# PX4FMUv2_4_6.net
KiCad netlist of a schematic drawn in EAGLE
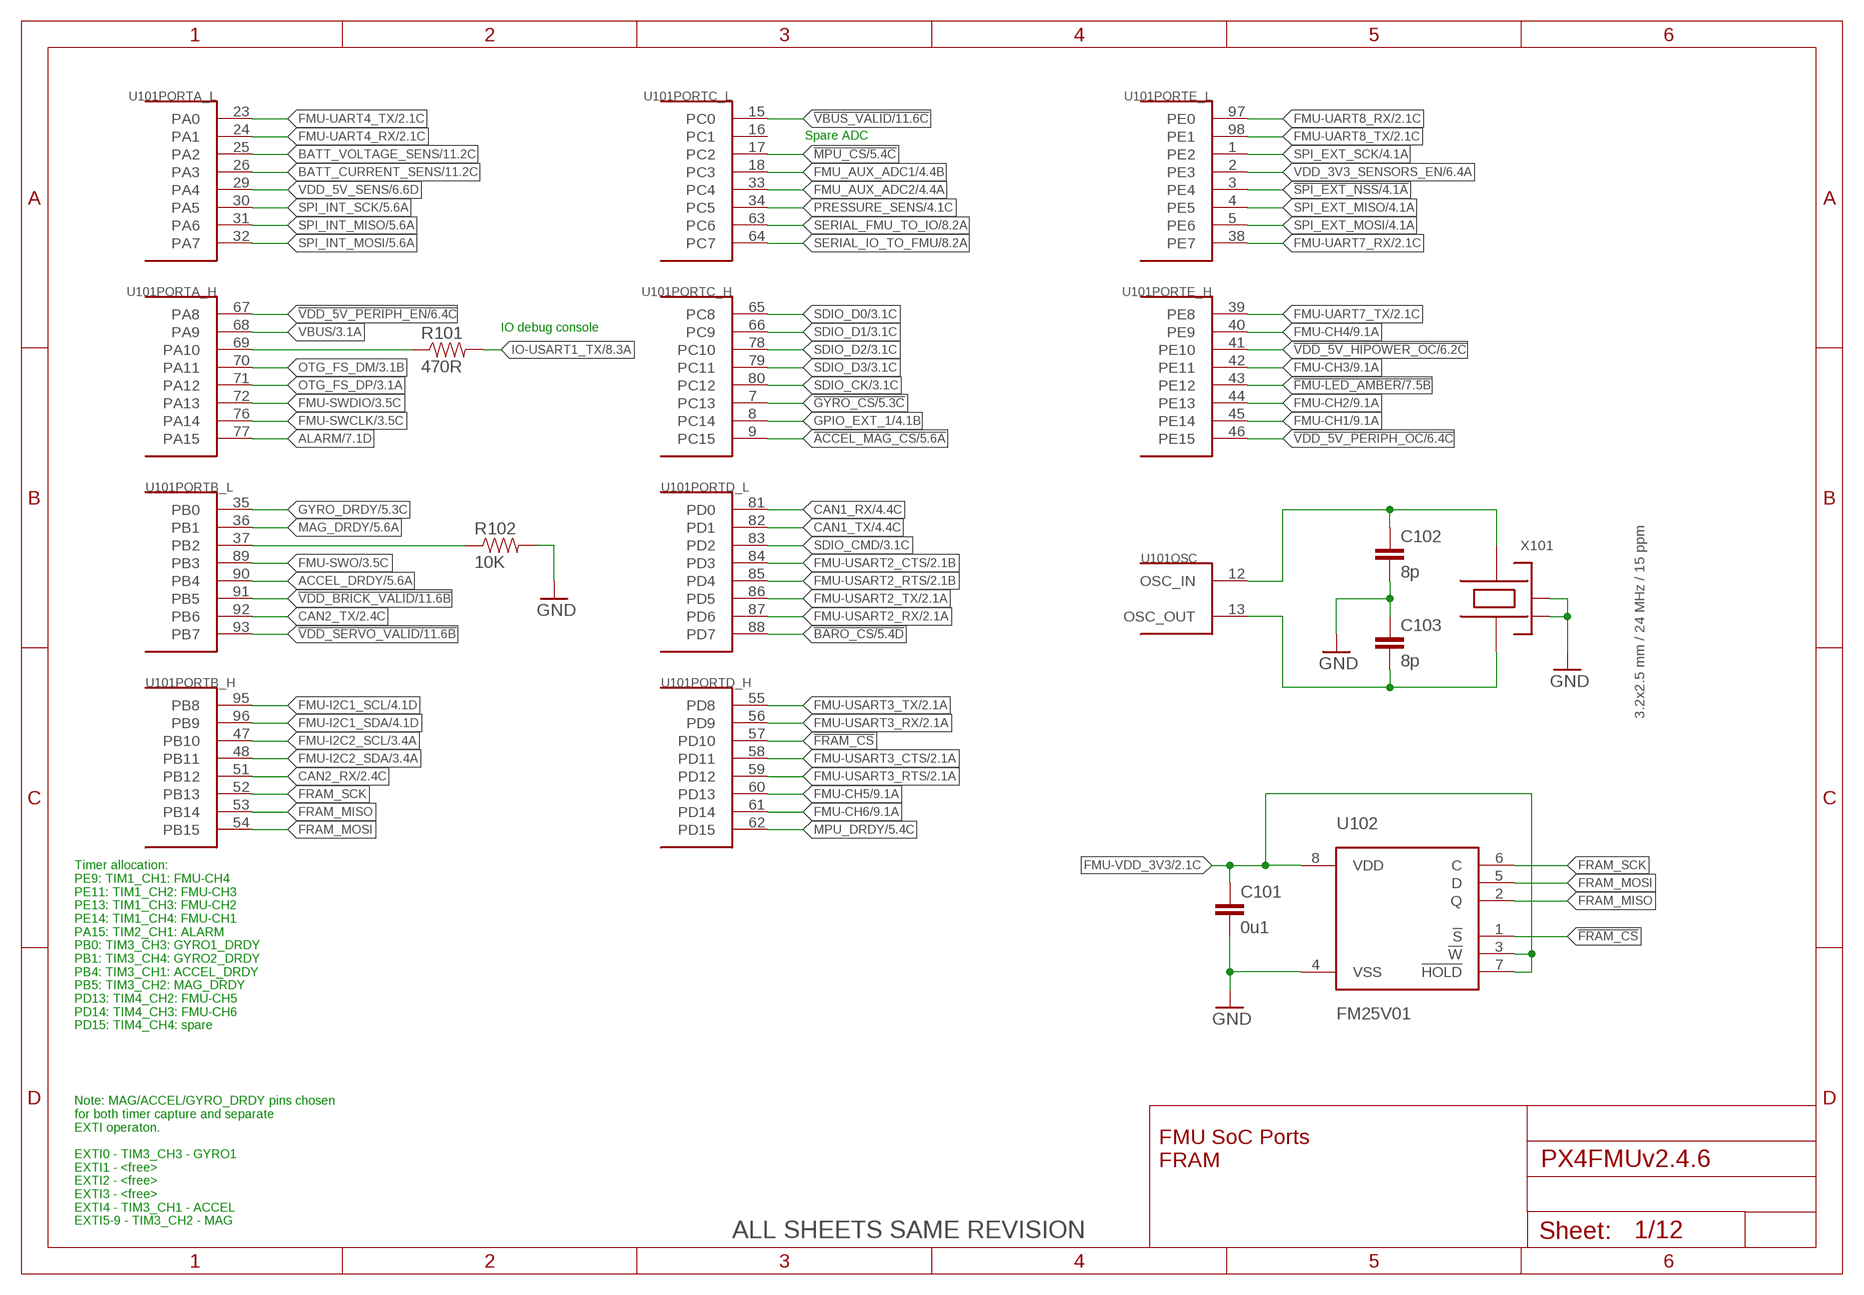
[diagram p0: schematic, sheet 1]
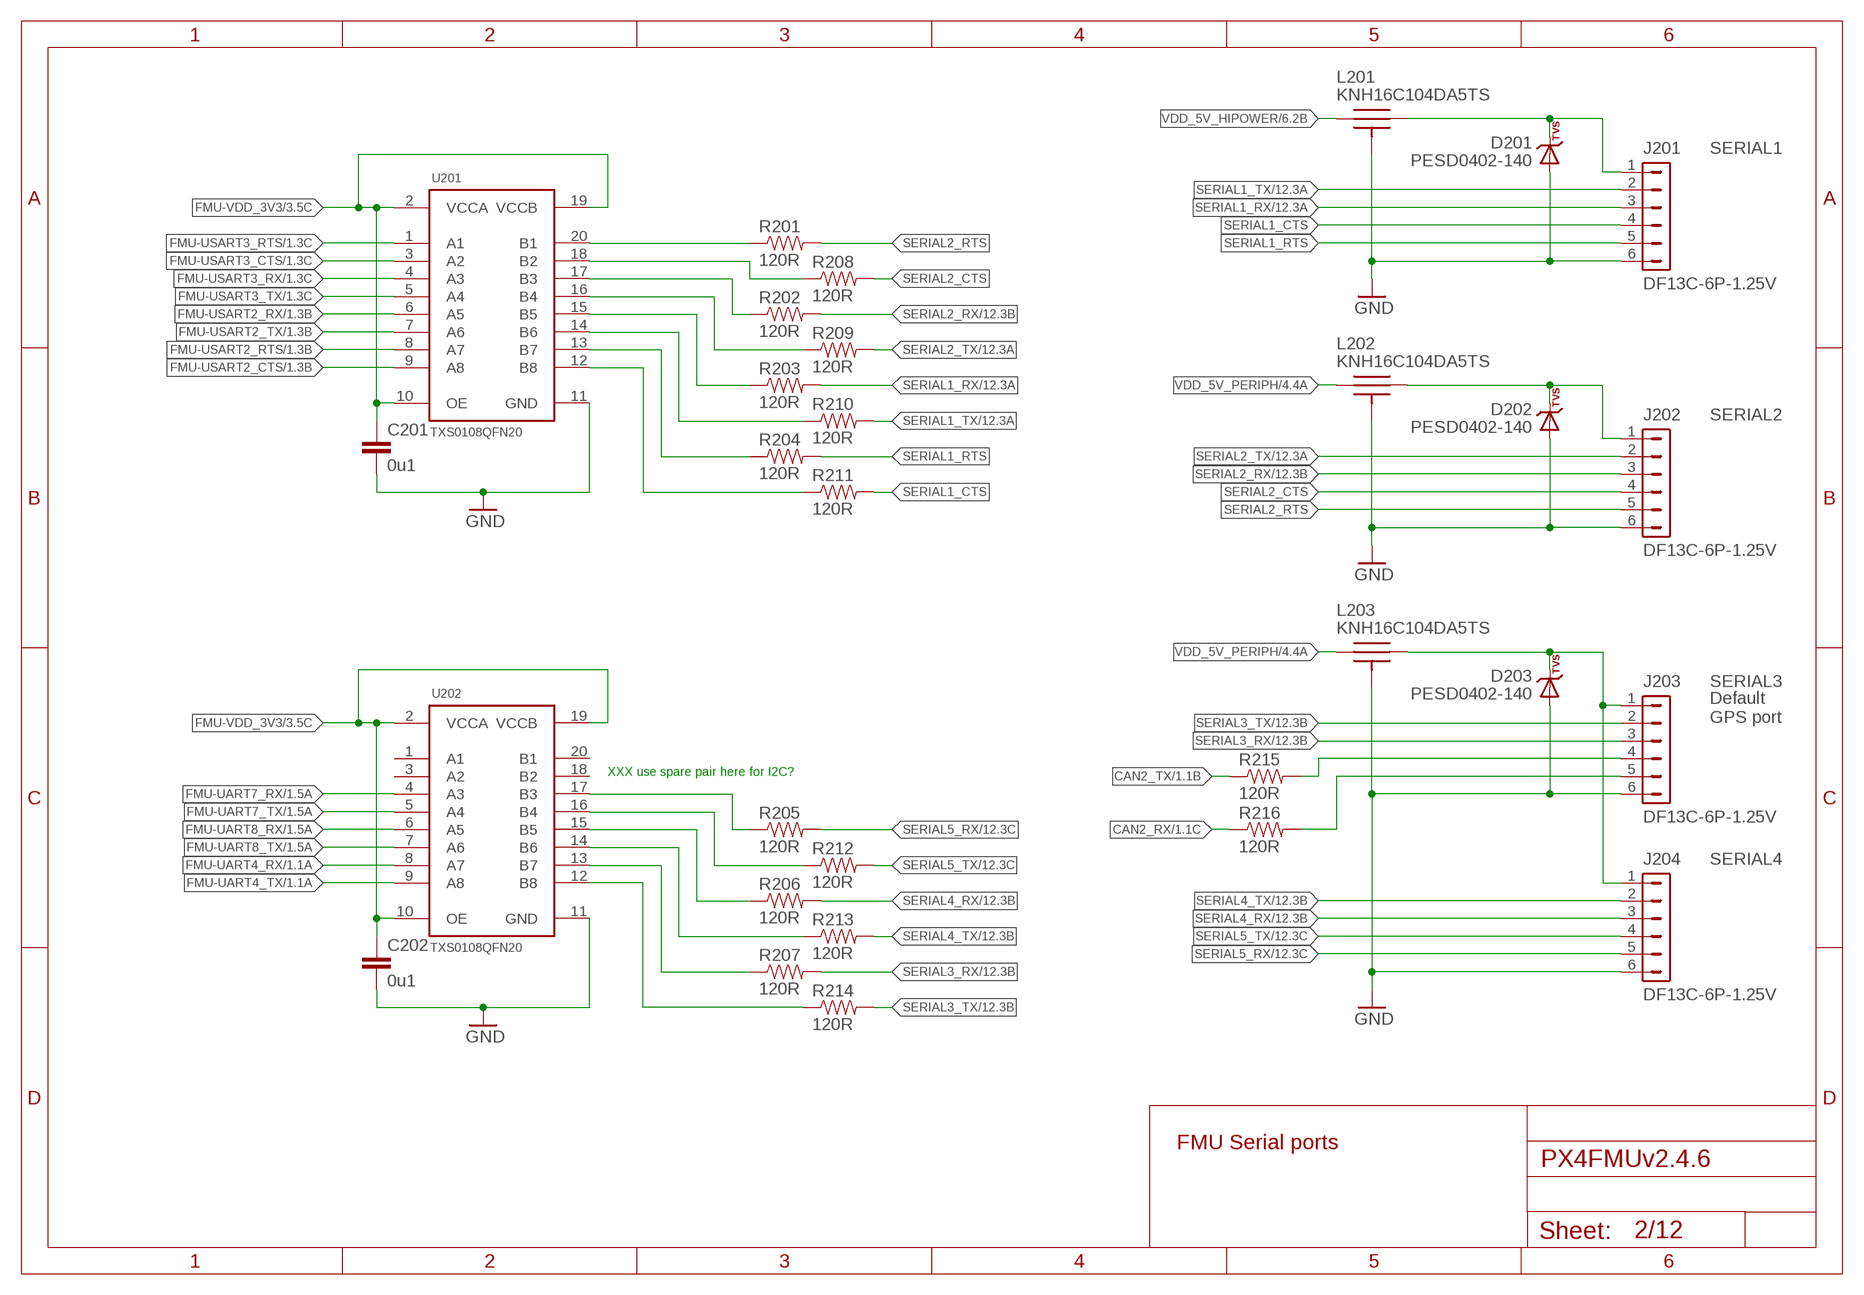
[diagram p1: schematic, sheet 2]
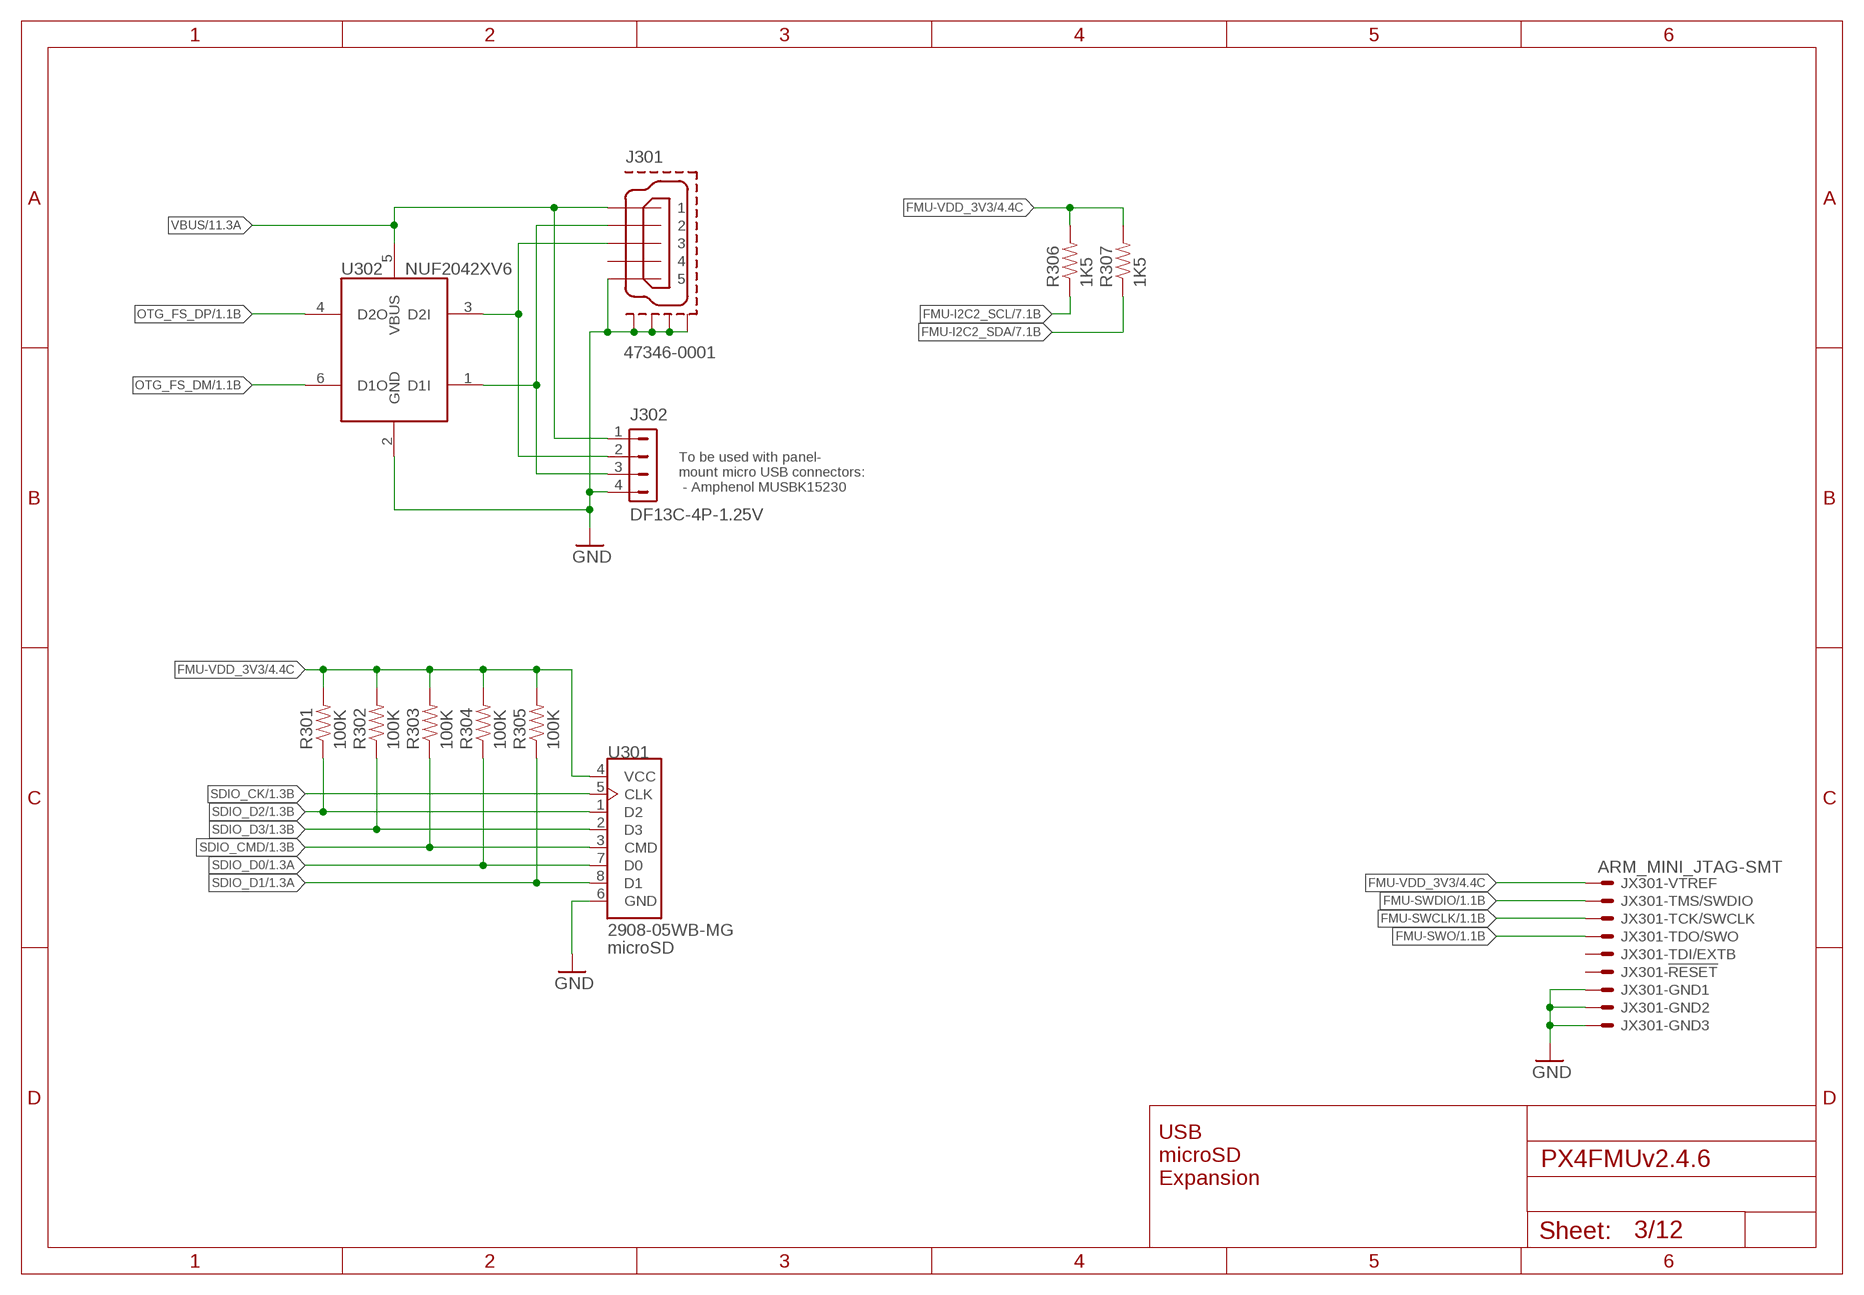
[diagram p2: schematic, sheet 3]
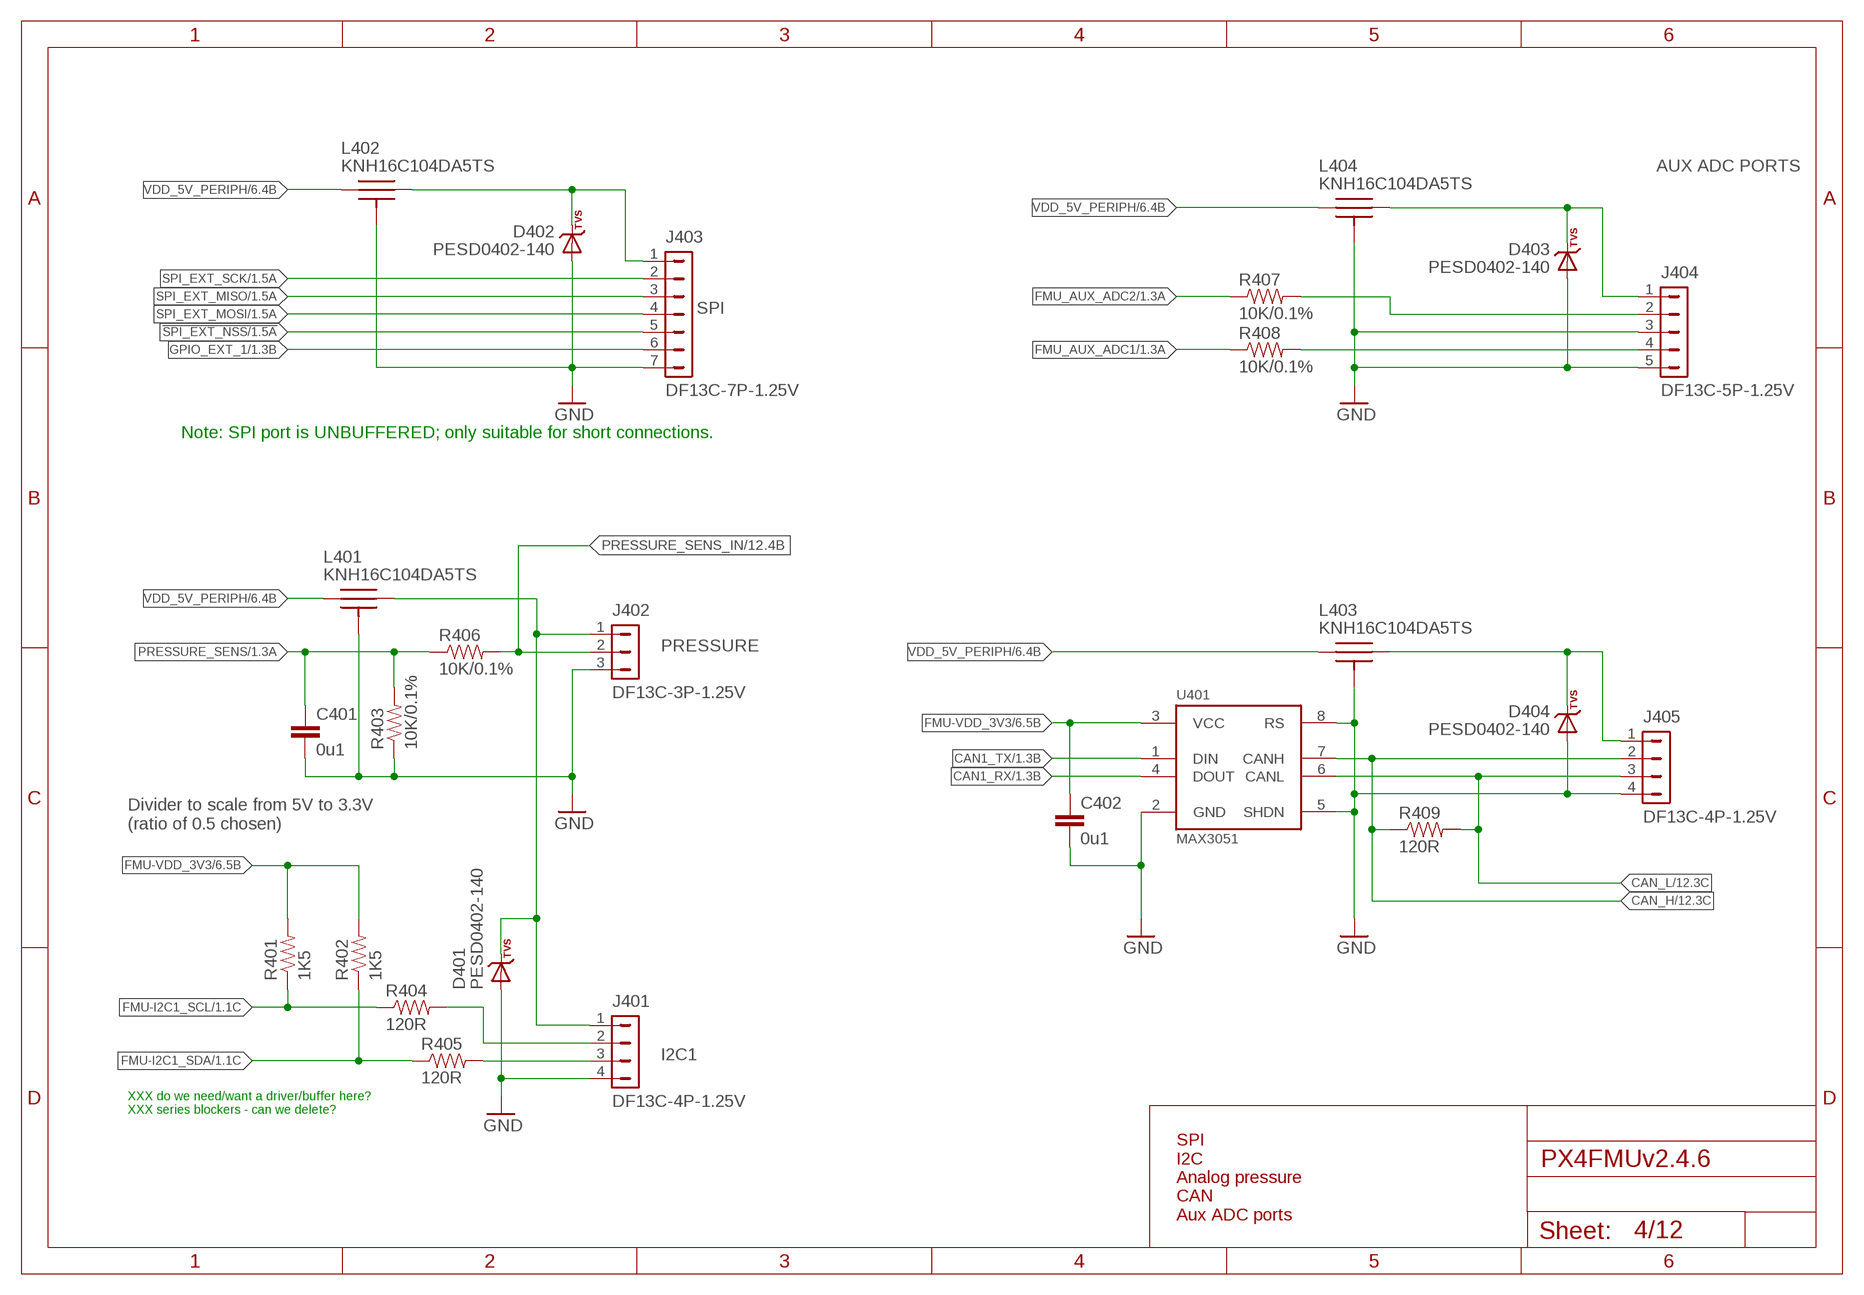
[diagram p3: schematic, sheet 4]
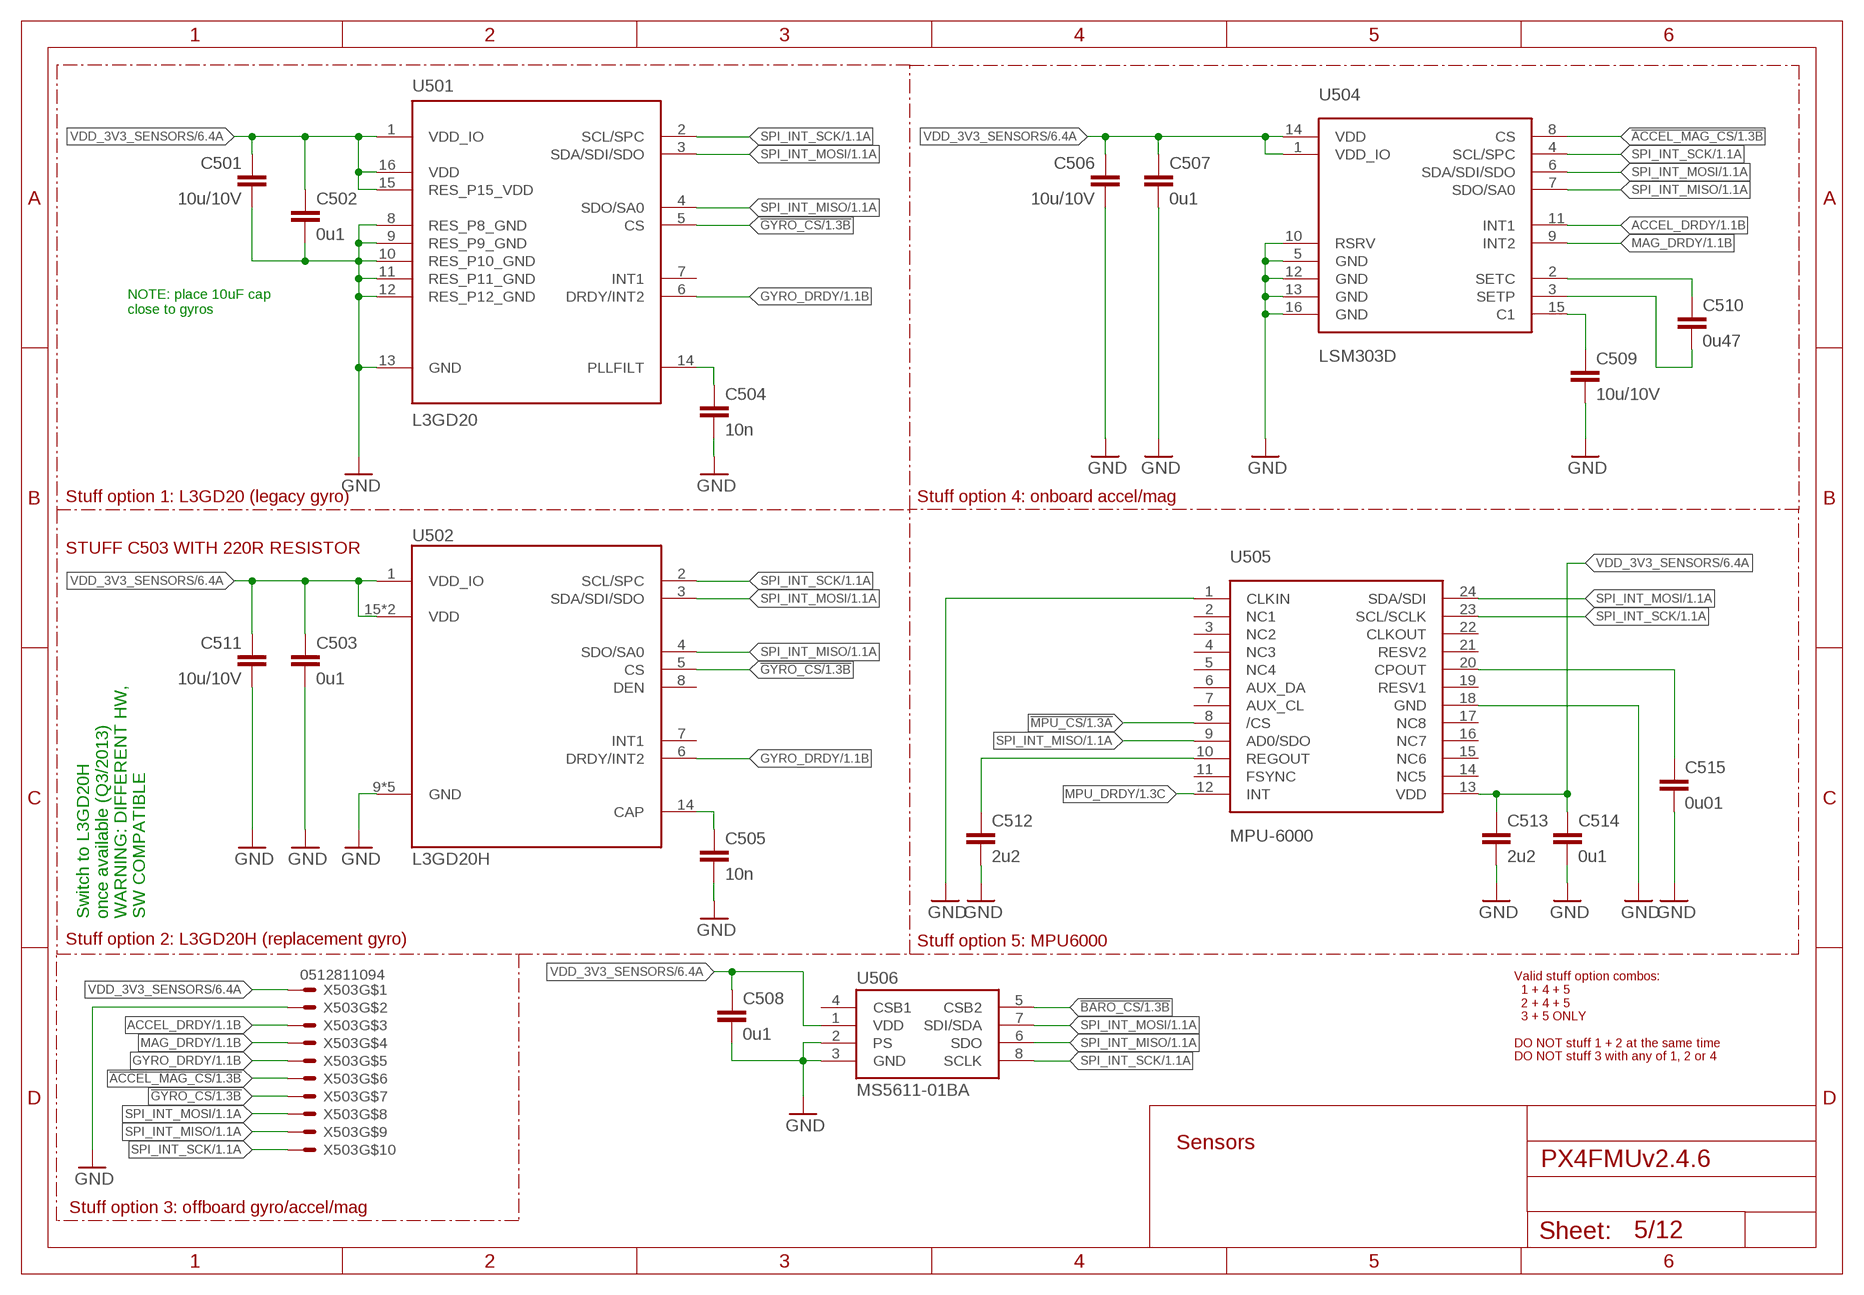
[diagram p4: schematic, sheet 5]
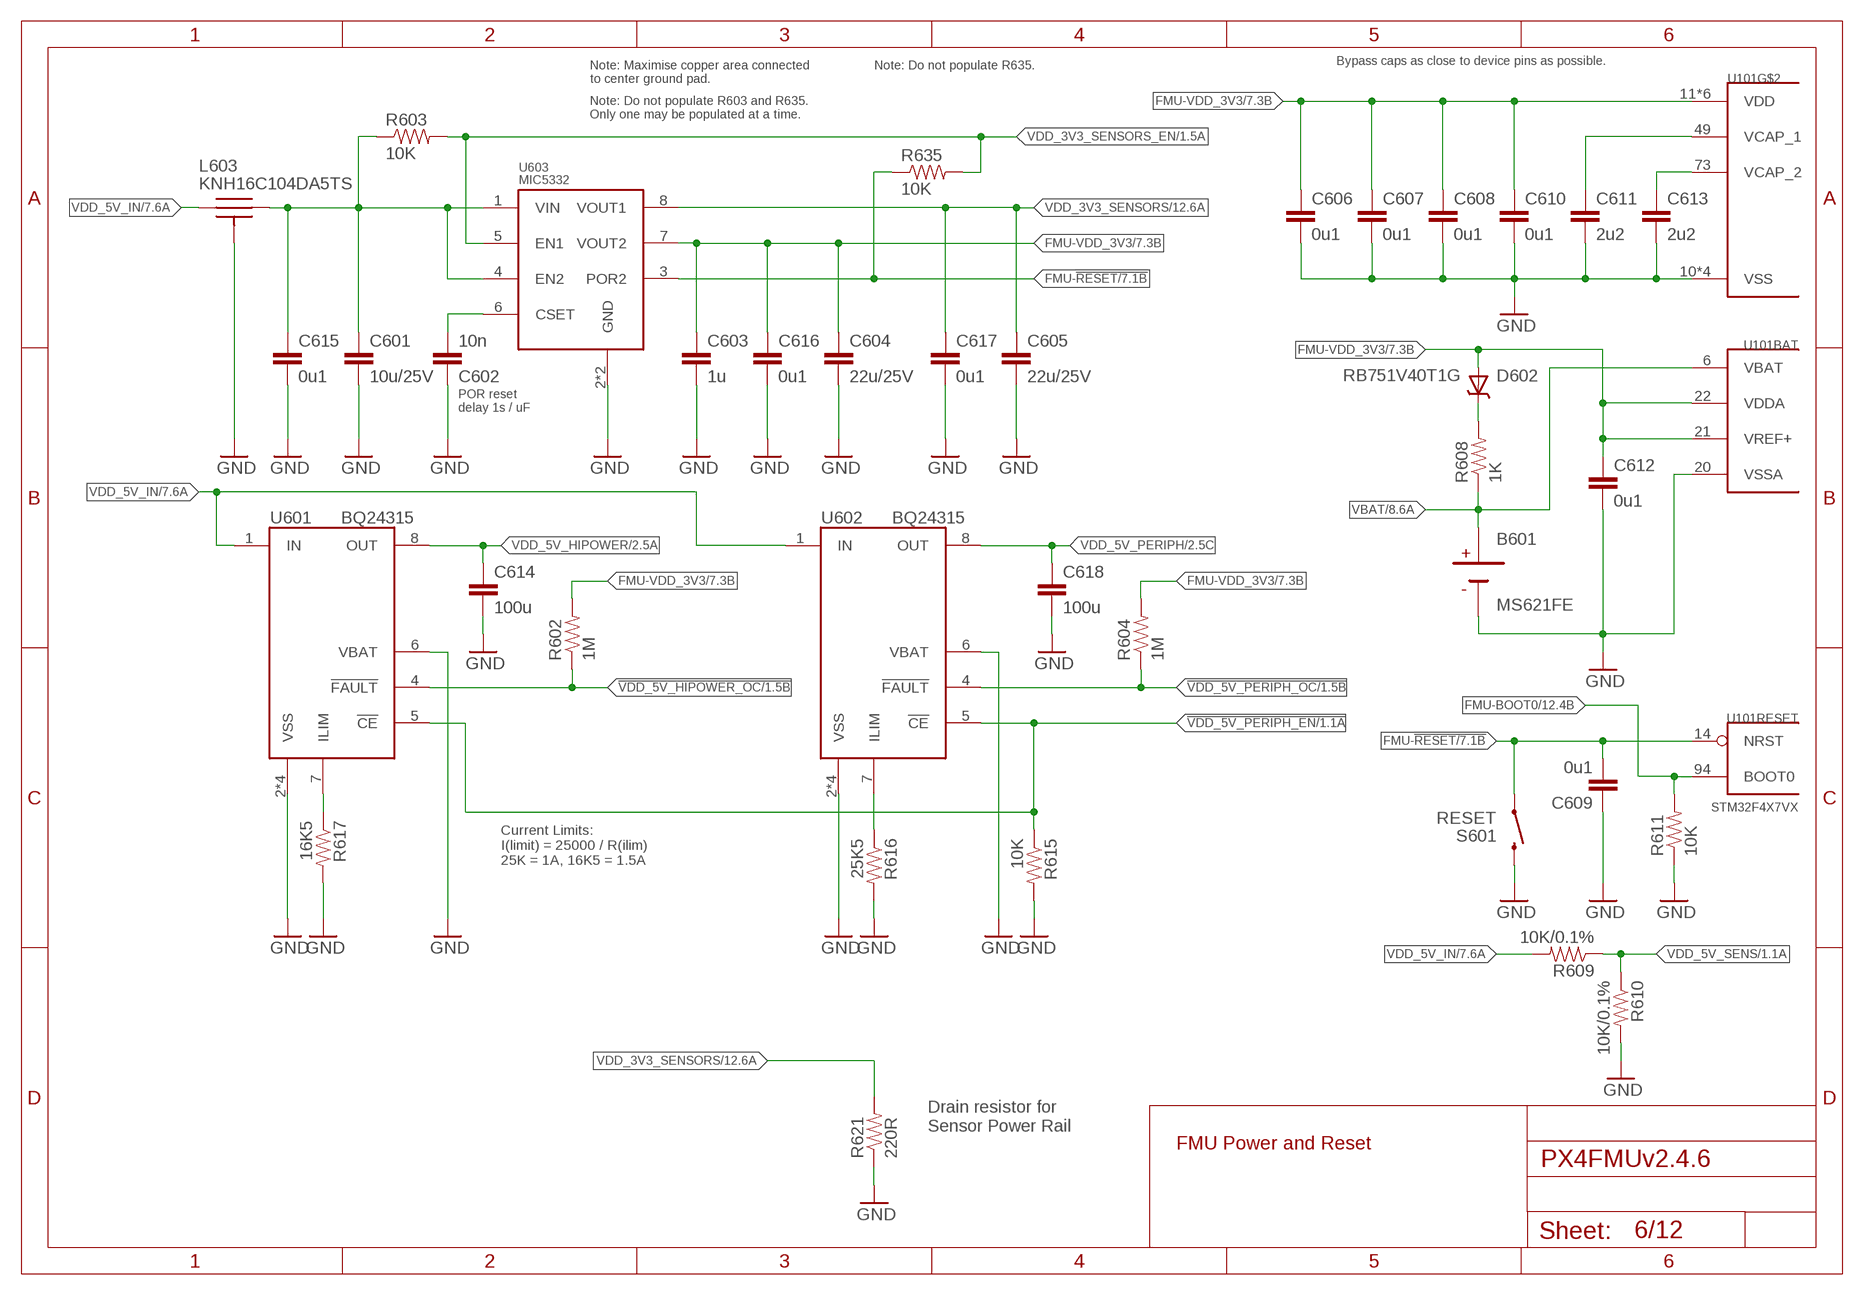
[diagram p5: schematic, sheet 6]
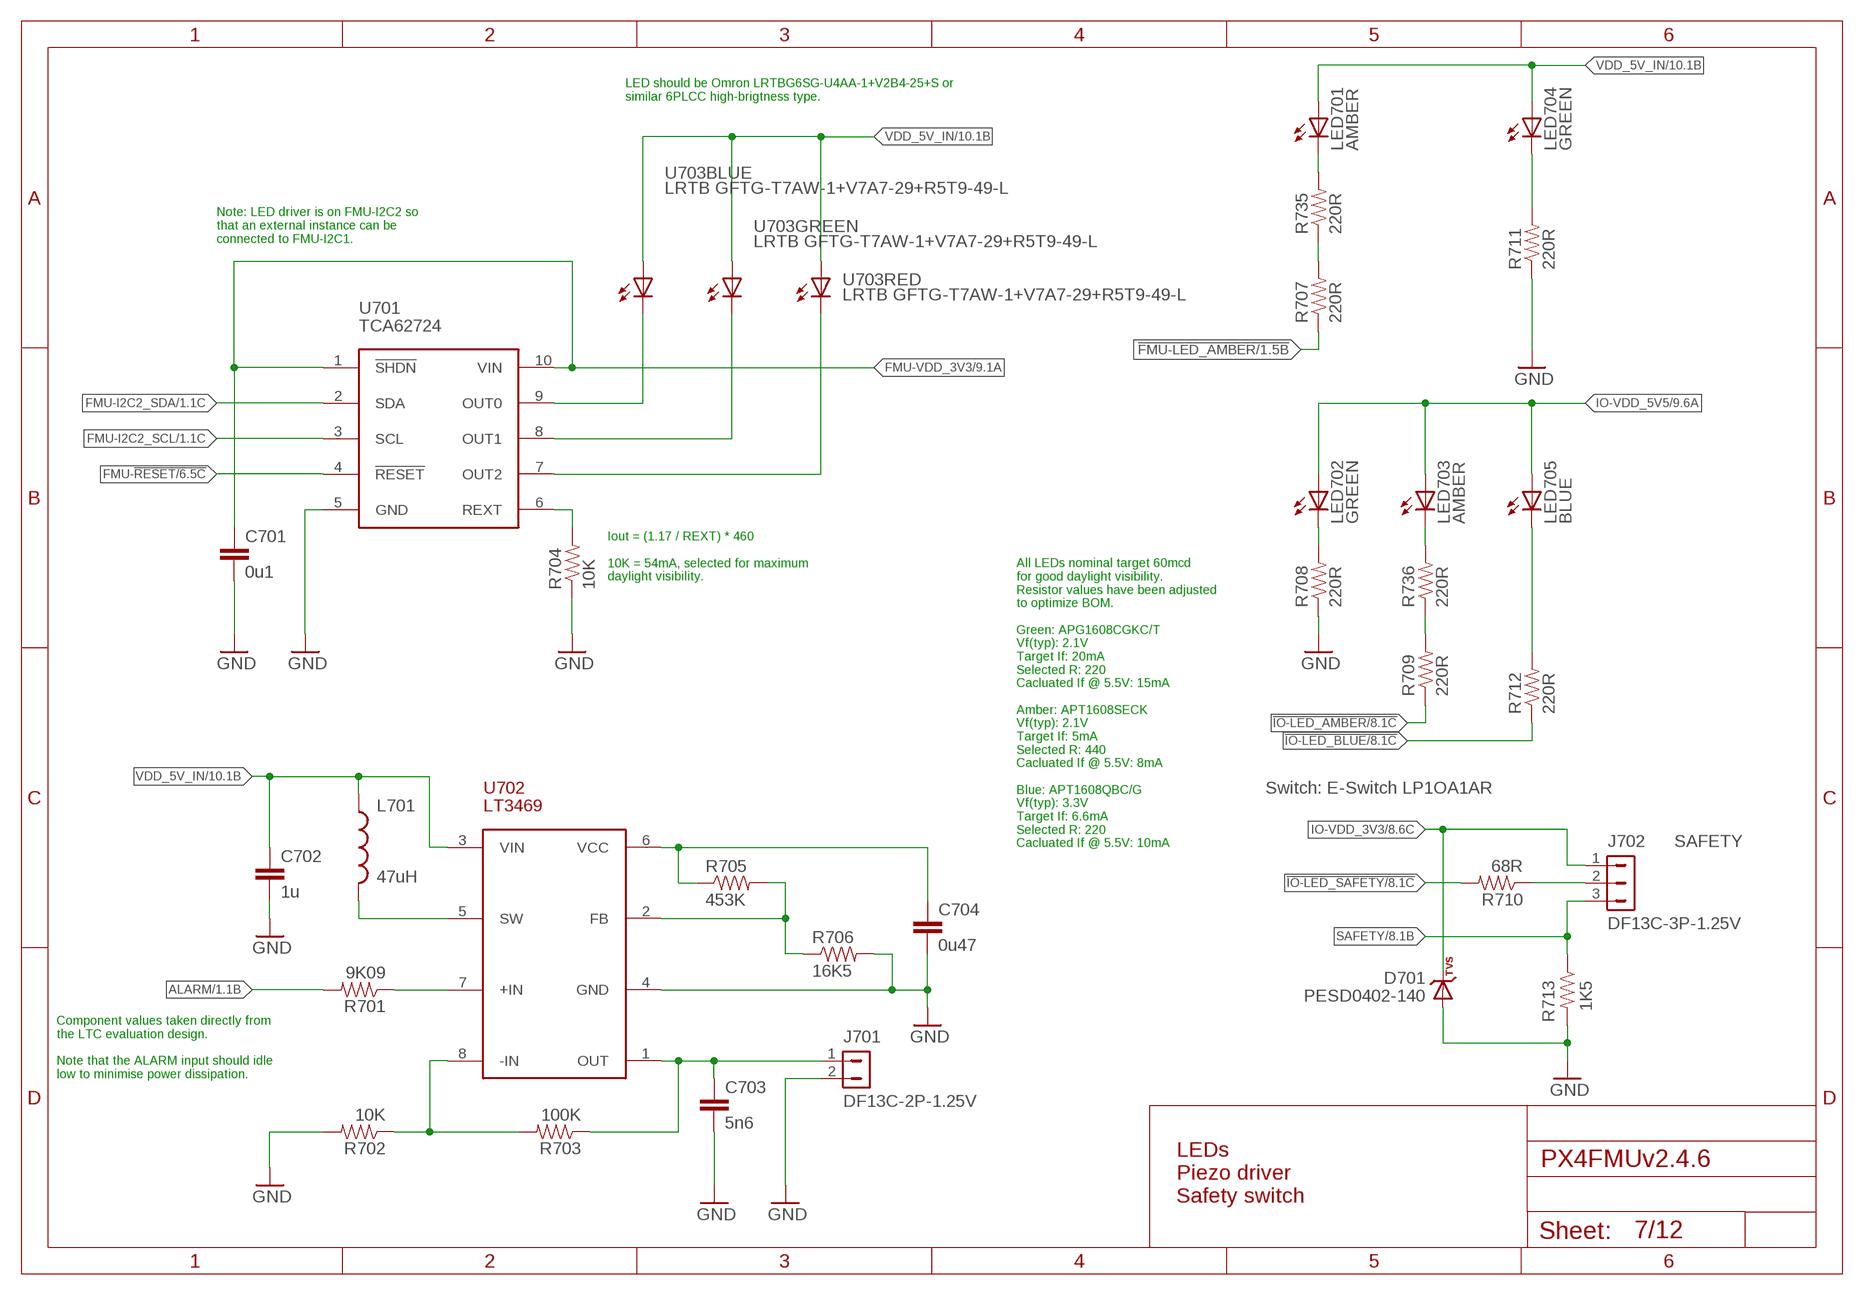
[diagram p6: schematic, sheet 7]
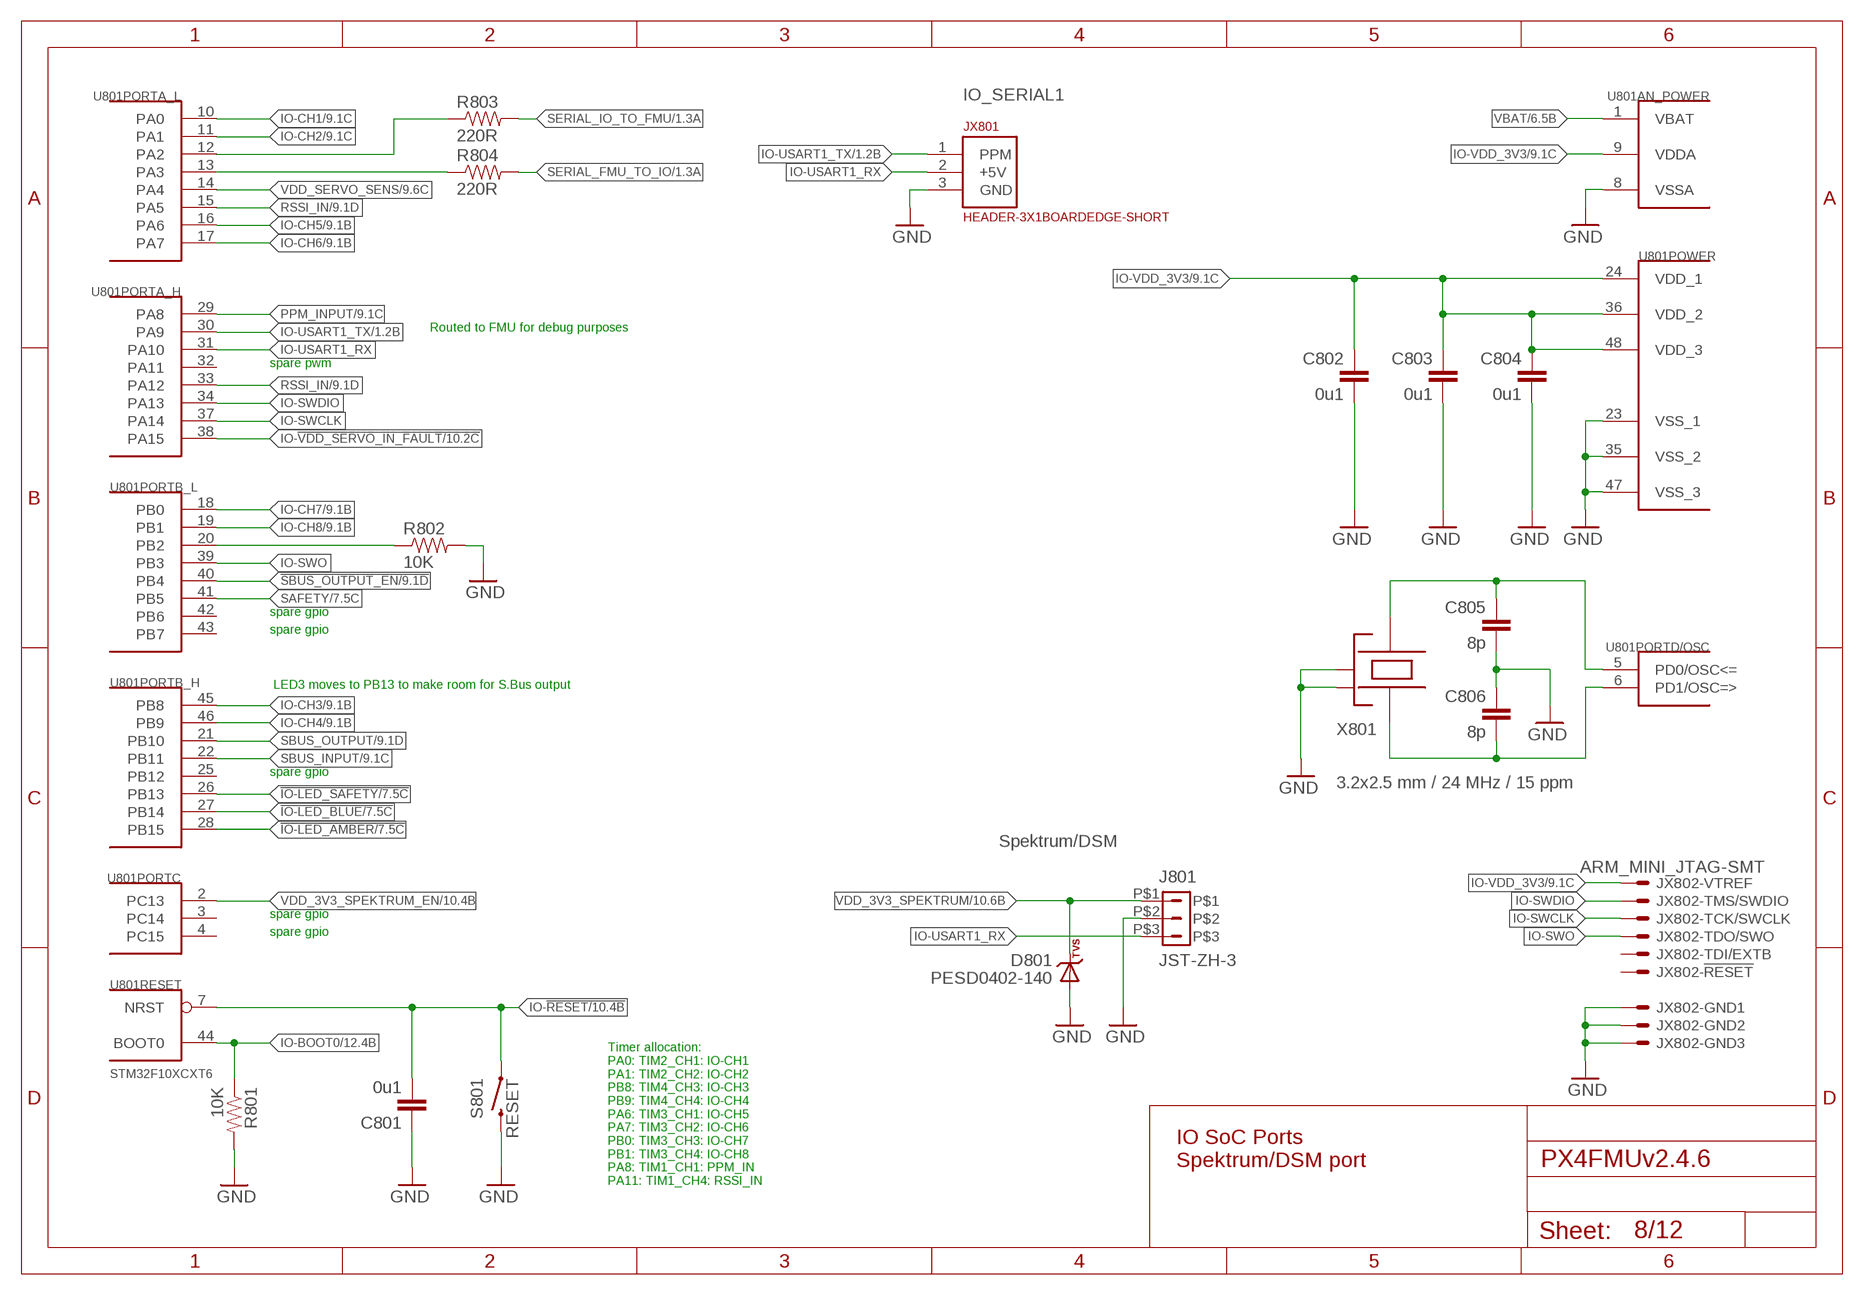
[diagram p7: schematic, sheet 8]
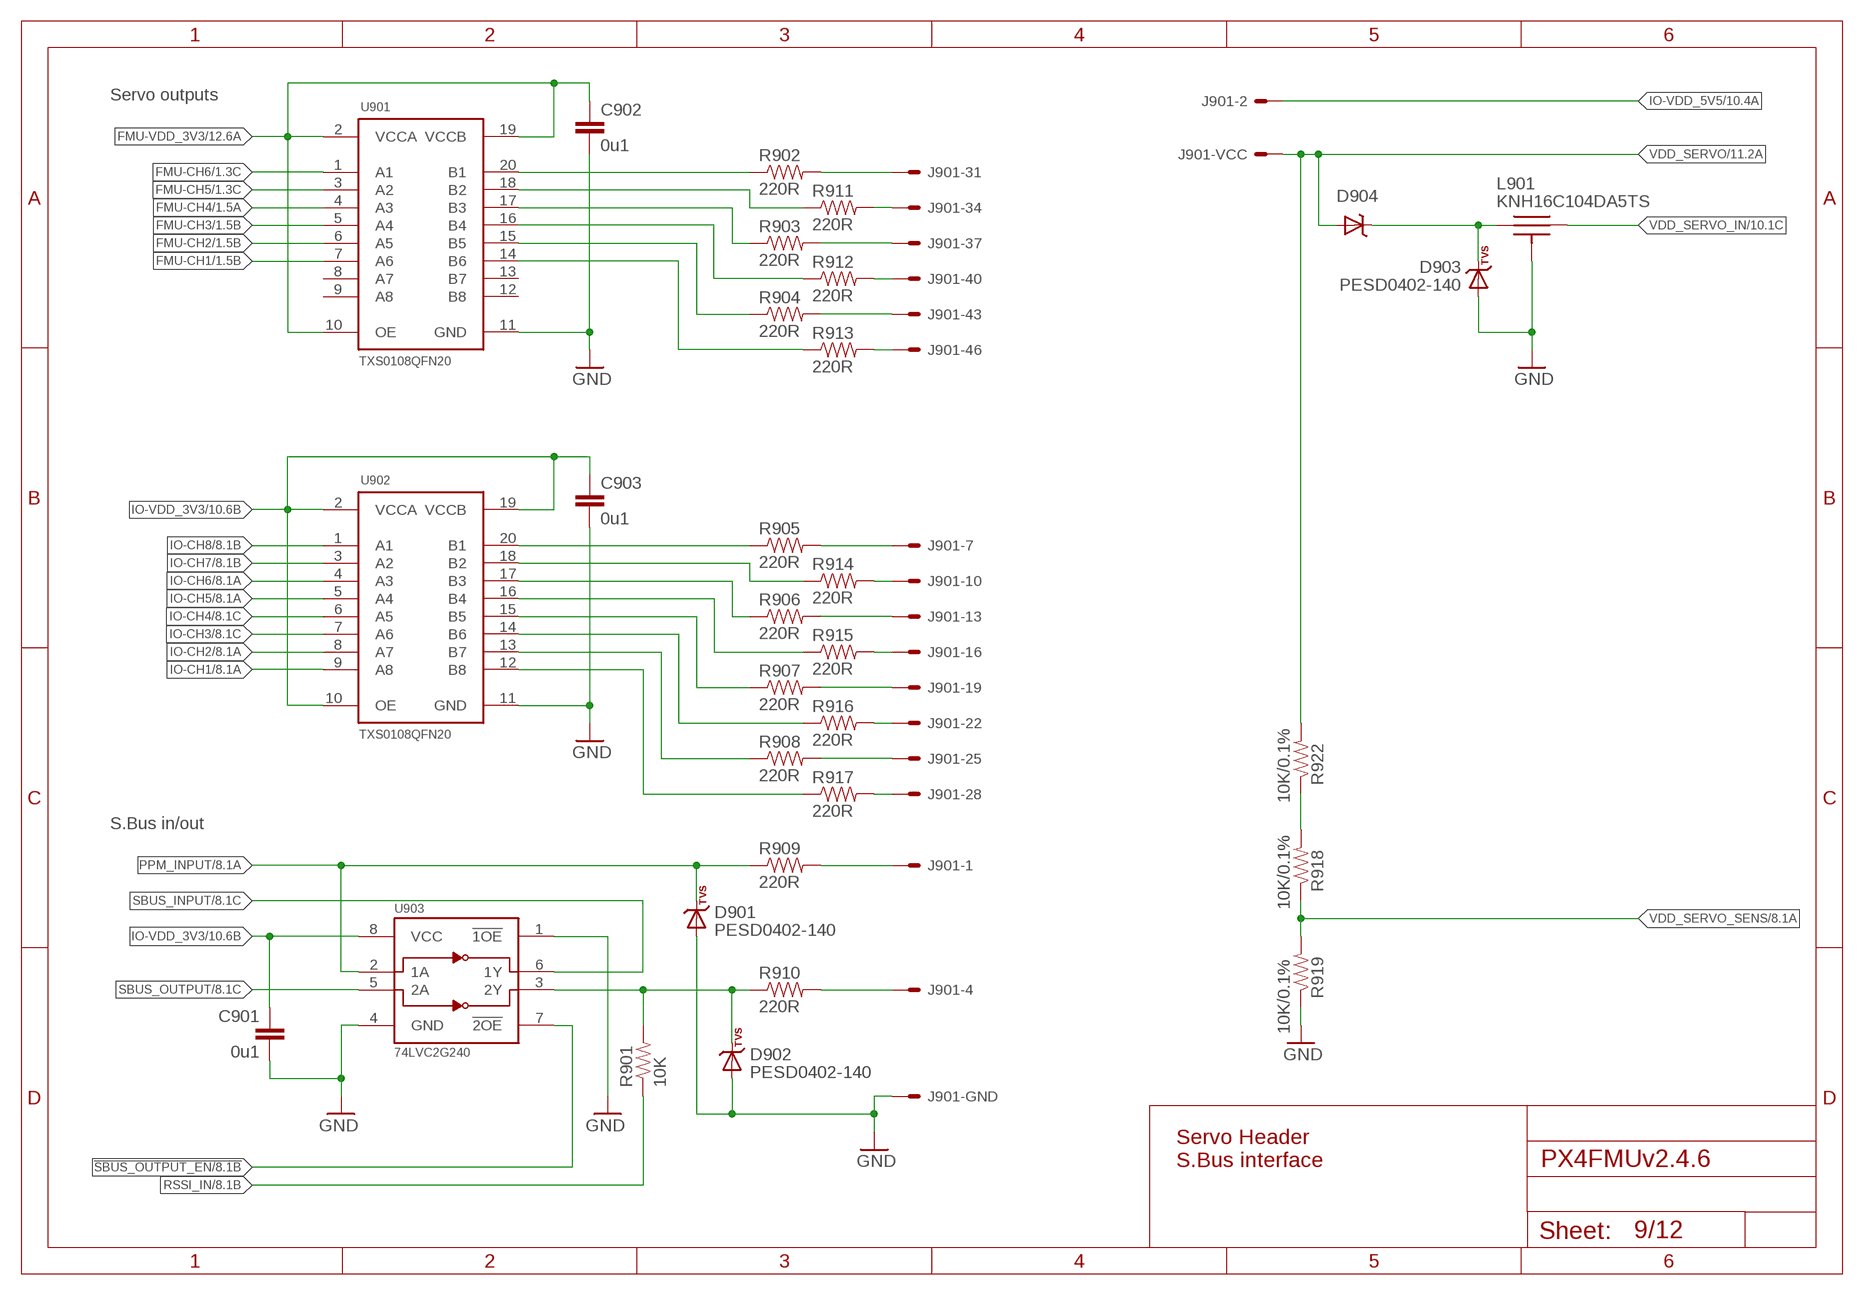
[diagram p8: schematic, sheet 9]
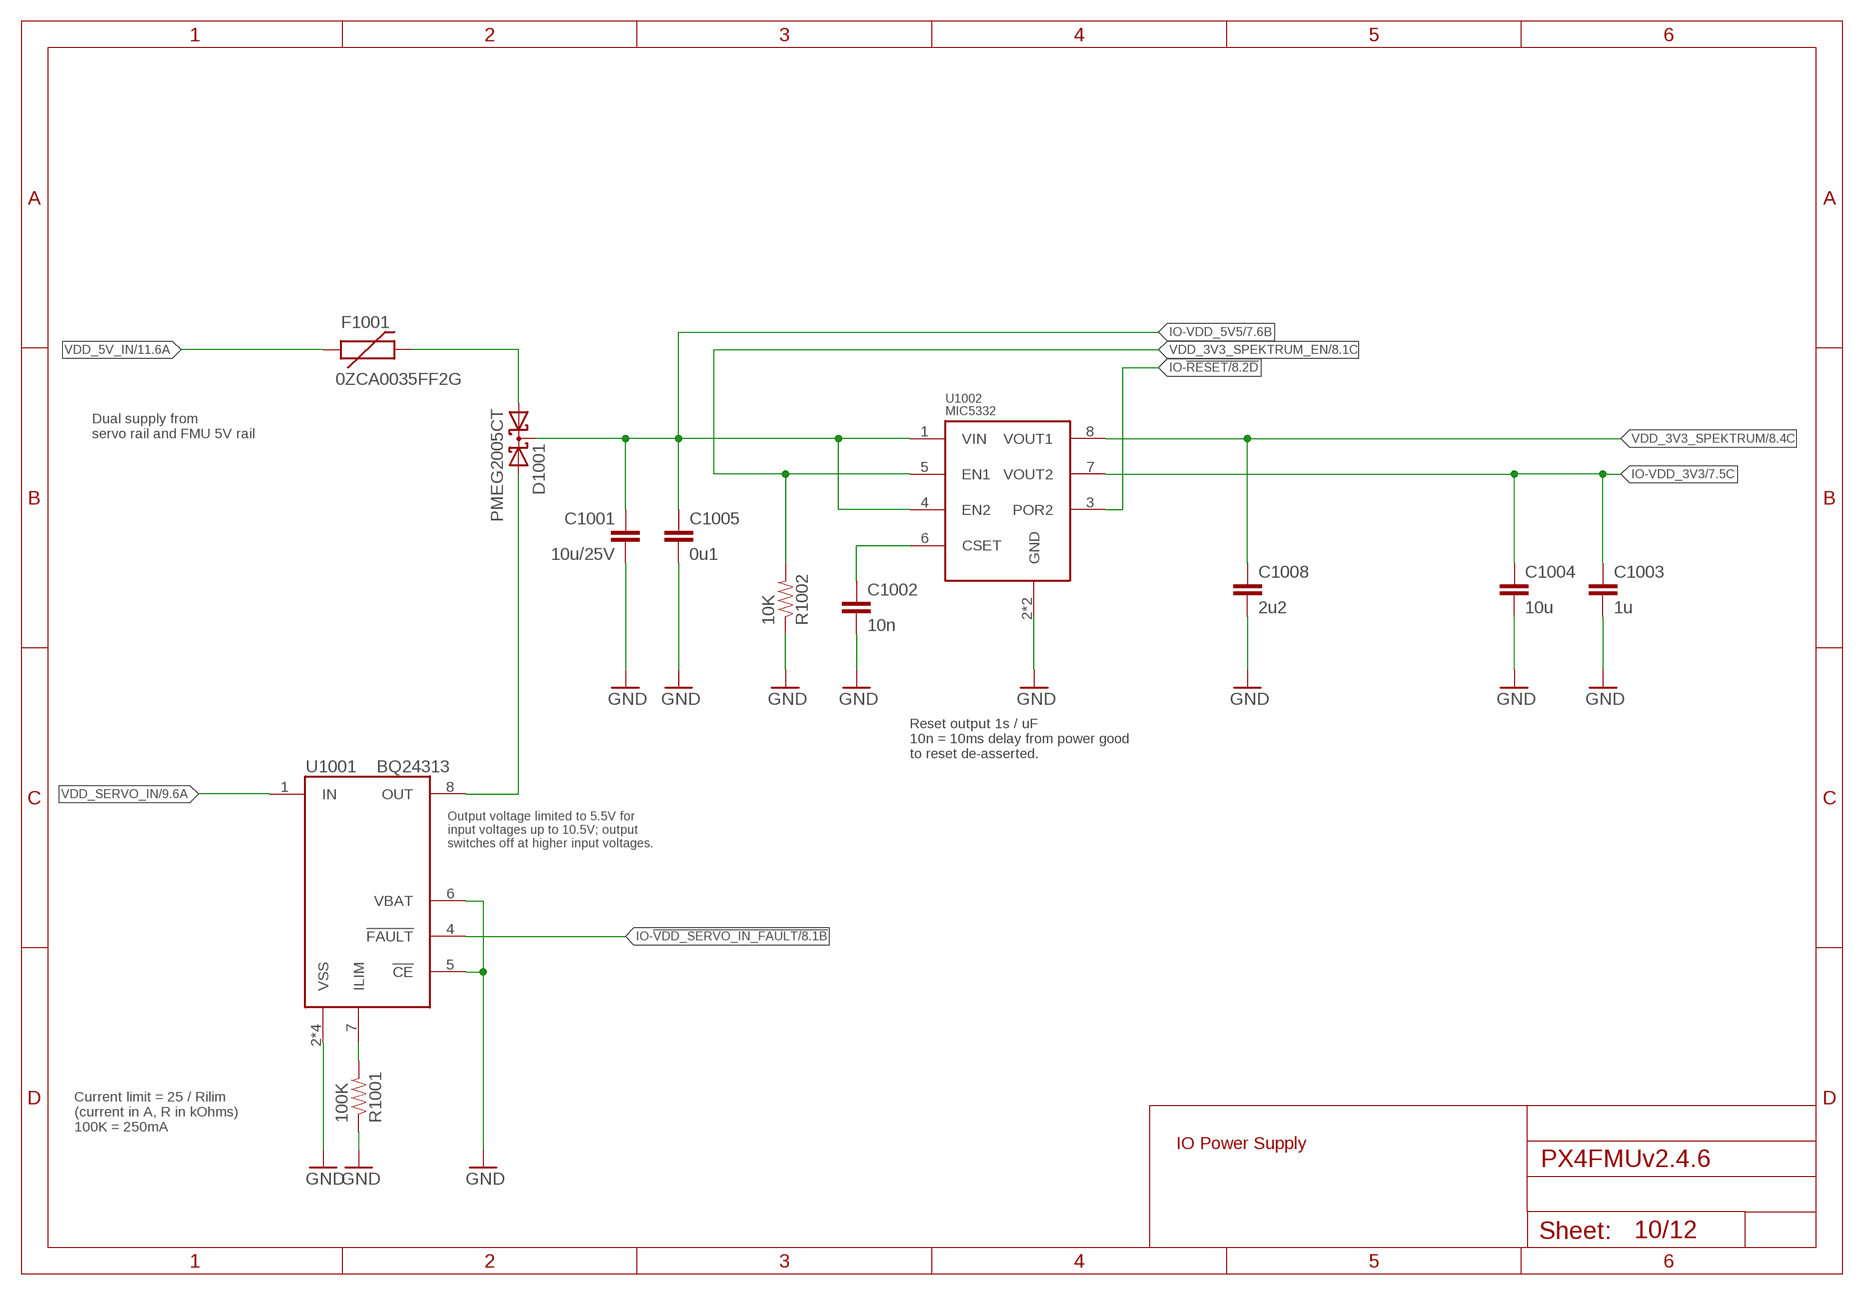
[diagram p9: schematic, sheet 10]
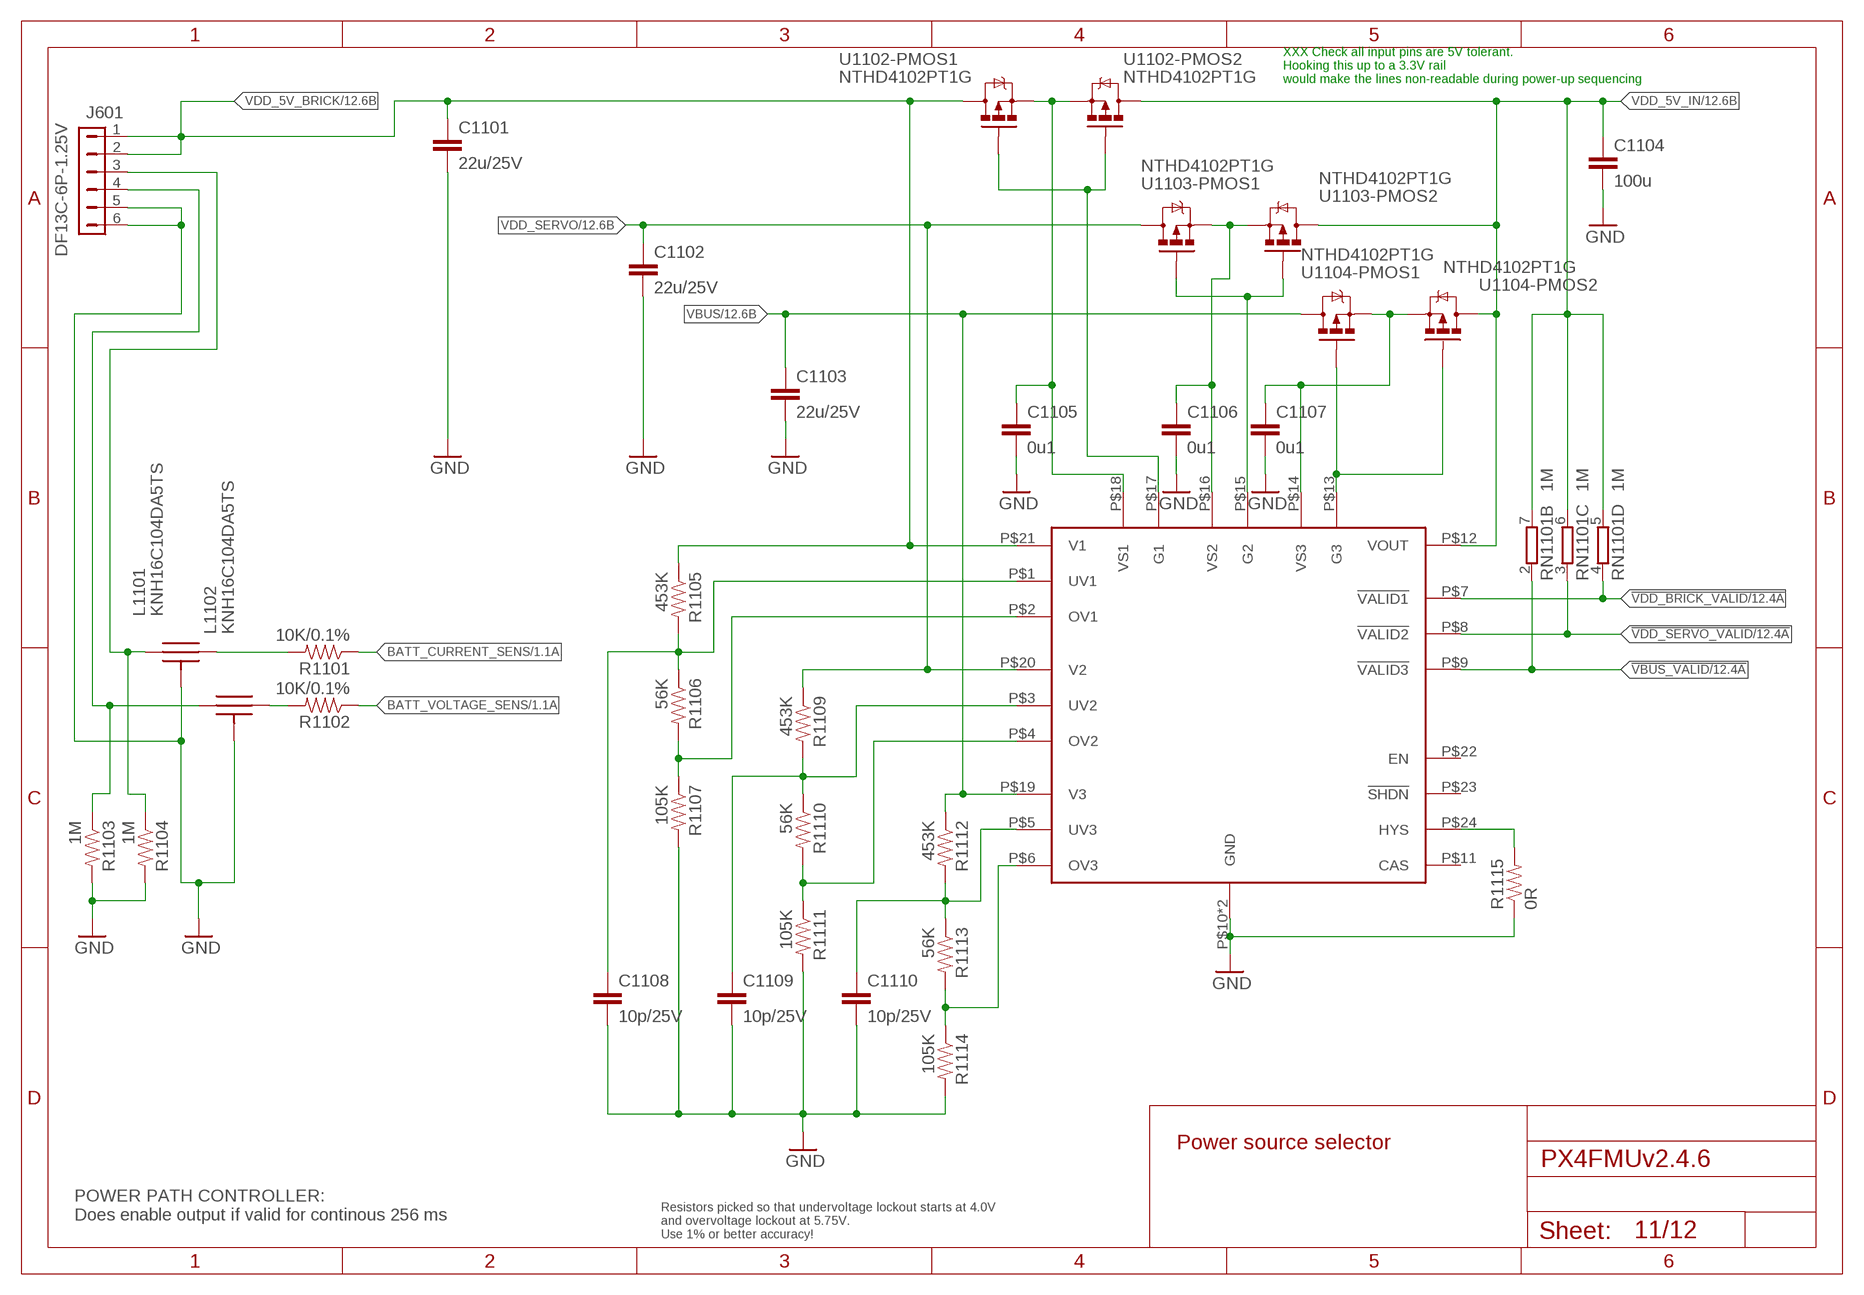
[diagram p10: schematic, sheet 11]
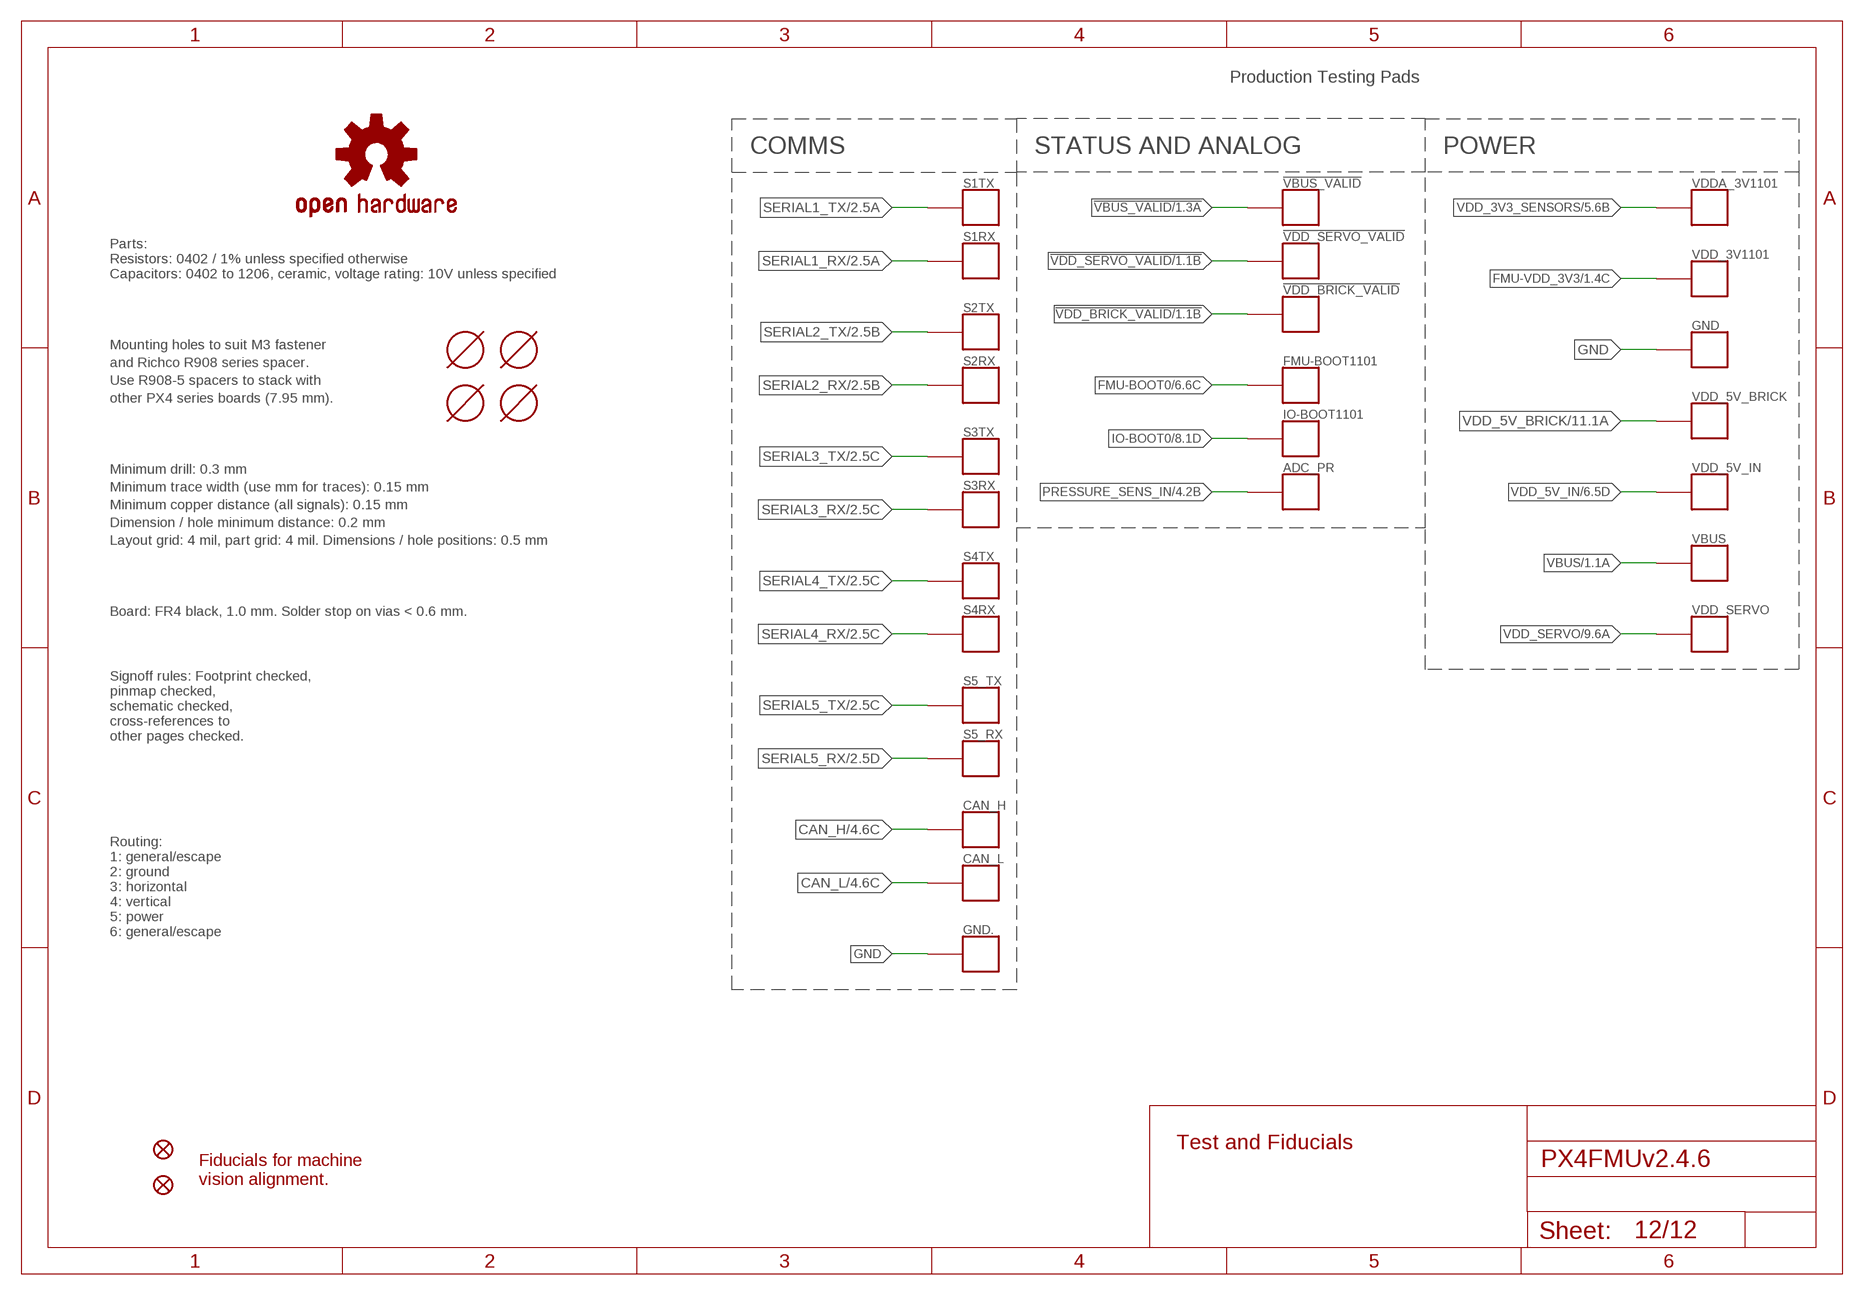
[diagram p11: schematic, sheet 12]

(export (version "E")
  (design (tool "Eeschema 10.0.6"))
  (components
    (comp (ref "C101")
      (value "0u1")
      (footprint "eagle-import:0402-CAP")
      (fields (field (name "PARTNO") "CC0402ZRY5V7BB104"))
      (libsource (lib "eagle-import") (part "CAP0402"))
    )
    (comp (ref "C102")
      (value "8p")
      (footprint "eagle-import:0402-CAP")
      (fields (field (name "PARTNO") "C1005C0G1H080C"))
      (libsource (lib "eagle-import") (part "CAP0402"))
    )
    (comp (ref "C103")
      (value "8p")
      (footprint "eagle-import:0402-CAP")
      (fields (field (name "PARTNO") "C1005C0G1H080C"))
      (libsource (lib "eagle-import") (part "CAP0402"))
    )
    (comp (ref "R101")
      (value "470R")
      (footprint "eagle-import:0402-RES")
      (fields (field (name "PARTNO") "RC0402FR-07470RL"))
      (libsource (lib "eagle-import") (part "RESISTOR0402-RES"))
    )
    (comp (ref "R102")
      (value "10K")
      (footprint "eagle-import:0402-RES")
      (fields (field (name "PARTNO") "RC0402FR-0710KL"))
      (libsource (lib "eagle-import") (part "RESISTOR0402-RES"))
    )
    (comp (ref "U101")
      (value "STM32F4X7VX")
      (footprint "eagle-import:TQFP100")
      (fields (field (name "PARTNO") "STM32F427VI"))
      (libsource (lib "eagle-import") (part "STM32F4X7VX"))
    )
    (comp (ref "U102")
      (value "FM25V01")
      (footprint "eagle-import:SO08")
      (fields (field (name "PARTNO") "FM25V01-G"))
      (libsource (lib "eagle-import") (part "FM25V01"))
    )
    (comp (ref "X101")
      (value "3.2x2.5 mm / 24 MHz / 15 ppm")
      (footprint "eagle-import:OSCILLATOR-3.2X2.5")
      (fields (field (name "PARTNO") "NX3225SA-24.000000MHZ"))
      (libsource (lib "eagle-import") (part "OSCILLATOR-3.2X2.5"))
    )
    (comp (ref "C901")
      (value "0u1")
      (footprint "eagle-import:0402-CAP")
      (fields (field (name "PARTNO") "CC0402ZRY5V7BB104"))
      (libsource (lib "eagle-import") (part "CAP0402"))
    )
    (comp (ref "C902")
      (value "0u1")
      (footprint "eagle-import:0402-CAP")
      (fields (field (name "PARTNO") "CC0402ZRY5V7BB104"))
      (libsource (lib "eagle-import") (part "CAP0402"))
    )
    (comp (ref "C903")
      (value "0u1")
      (footprint "eagle-import:0402-CAP")
      (fields (field (name "PARTNO") "CC0402ZRY5V7BB104"))
      (libsource (lib "eagle-import") (part "CAP0402"))
    )
    (comp (ref "D901")
      (value "PESD0402-140")
      (footprint "eagle-import:0402-TVS")
      (libsource (lib "eagle-import") (part "DIODE-TVS"))
    )
    (comp (ref "D902")
      (value "PESD0402-140")
      (footprint "eagle-import:0402-TVS")
      (libsource (lib "eagle-import") (part "DIODE-TVS"))
    )
    (comp (ref "D903")
      (value "PESD0402-140")
      (footprint "eagle-import:0402-TVS")
      (libsource (lib "eagle-import") (part "DIODE-TVS"))
    )
    (comp (ref "D904")
      (value "MSS1P4-M3")
      (footprint "eagle-import:MICROSMP")
      (fields (field (name "PARTNO") "MSS1P4-M3/89A"))
      (libsource (lib "eagle-import") (part "DIODE-SCHOTTKY_MSMP"))
    )
    (comp (ref "J901")
      (value "HEADER-3X163X16RA")
      (footprint "eagle-import:3X16RA")
      (fields (field (name "BOM") "EXCLUDE"))
      (libsource (lib "eagle-import") (part "HEADER-3X163X16RA"))
    )
    (comp (ref "L901")
      (value "KNH16C104DA5TS")
      (footprint "eagle-import:KYOCERA-KNH16-DA")
      (libsource (lib "eagle-import") (part "KNH16C104DA5TS"))
    )
    (comp (ref "R901")
      (value "10K")
      (footprint "eagle-import:0402-RES")
      (fields (field (name "PARTNO") "RC0402FR-0710KL"))
      (libsource (lib "eagle-import") (part "RESISTOR0402-RES"))
    )
    (comp (ref "R902")
      (value "220R")
      (footprint "eagle-import:0402-RES")
      (fields (field (name "PARTNO") "RC0402FR-07220RL"))
      (libsource (lib "eagle-import") (part "RESISTOR0402-RES"))
    )
    (comp (ref "R903")
      (value "220R")
      (footprint "eagle-import:0402-RES")
      (fields (field (name "PARTNO") "RC0402FR-07220RL"))
      (libsource (lib "eagle-import") (part "RESISTOR0402-RES"))
    )
    (comp (ref "R904")
      (value "220R")
      (footprint "eagle-import:0402-RES")
      (fields (field (name "PARTNO") "RC0402FR-07220RL"))
      (libsource (lib "eagle-import") (part "RESISTOR0402-RES"))
    )
    (comp (ref "R905")
      (value "220R")
      (footprint "eagle-import:0402-RES")
      (fields (field (name "PARTNO") "RC0402FR-07220RL"))
      (libsource (lib "eagle-import") (part "RESISTOR0402-RES"))
    )
    (comp (ref "R906")
      (value "220R")
      (footprint "eagle-import:0402-RES")
      (fields (field (name "PARTNO") "RC0402FR-07220RL"))
      (libsource (lib "eagle-import") (part "RESISTOR0402-RES"))
    )
    (comp (ref "R907")
      (value "220R")
      (footprint "eagle-import:0402-RES")
      (fields (field (name "PARTNO") "RC0402FR-07220RL"))
      (libsource (lib "eagle-import") (part "RESISTOR0402-RES"))
    )
    (comp (ref "R908")
      (value "220R")
      (footprint "eagle-import:0402-RES")
      (fields (field (name "PARTNO") "RC0402FR-07220RL"))
      (libsource (lib "eagle-import") (part "RESISTOR0402-RES"))
    )
    (comp (ref "R909")
      (value "220R")
      (footprint "eagle-import:0402-RES")
      (fields (field (name "PARTNO") "RC0402FR-07220RL"))
      (libsource (lib "eagle-import") (part "RESISTOR0402-RES"))
    )
    (comp (ref "R910")
      (value "220R")
      (footprint "eagle-import:0402-RES")
      (fields (field (name "PARTNO") "RC0402FR-07220RL"))
      (libsource (lib "eagle-import") (part "RESISTOR0402-RES"))
    )
    (comp (ref "R911")
      (value "220R")
      (footprint "eagle-import:0402-RES")
      (fields (field (name "PARTNO") "RC0402FR-07220RL"))
      (libsource (lib "eagle-import") (part "RESISTOR0402-RES"))
    )
    (comp (ref "R912")
      (value "220R")
      (footprint "eagle-import:0402-RES")
      (fields (field (name "PARTNO") "RC0402FR-07220RL"))
      (libsource (lib "eagle-import") (part "RESISTOR0402-RES"))
    )
    (comp (ref "R913")
      (value "220R")
      (footprint "eagle-import:0402-RES")
      (fields (field (name "PARTNO") "RC0402FR-07220RL"))
      (libsource (lib "eagle-import") (part "RESISTOR0402-RES"))
    )
    (comp (ref "R914")
      (value "220R")
      (footprint "eagle-import:0402-RES")
      (fields (field (name "PARTNO") "RC0402FR-07220RL"))
      (libsource (lib "eagle-import") (part "RESISTOR0402-RES"))
    )
    (comp (ref "R915")
      (value "220R")
      (footprint "eagle-import:0402-RES")
      (fields (field (name "PARTNO") "RC0402FR-07220RL"))
      (libsource (lib "eagle-import") (part "RESISTOR0402-RES"))
    )
    (comp (ref "R916")
      (value "220R")
      (footprint "eagle-import:0402-RES")
      (fields (field (name "PARTNO") "RC0402FR-07220RL"))
      (libsource (lib "eagle-import") (part "RESISTOR0402-RES"))
    )
    (comp (ref "R917")
      (value "220R")
      (footprint "eagle-import:0402-RES")
      (fields (field (name "PARTNO") "RC0402FR-07220RL"))
      (libsource (lib "eagle-import") (part "RESISTOR0402-RES"))
    )
    (comp (ref "R918")
      (value "10K/0.1%")
      (footprint "eagle-import:0402-RES")
      (fields (field (name "PARTNO") "ERA-2AEB103X"))
      (libsource (lib "eagle-import") (part "RESISTOR0402-RES"))
    )
    (comp (ref "R919")
      (value "10K/0.1%")
      (footprint "eagle-import:0402-RES")
      (fields (field (name "PARTNO") "ERA-2AEB103X"))
      (libsource (lib "eagle-import") (part "RESISTOR0402-RES"))
    )
    (comp (ref "R922")
      (value "10K/0.1%")
      (footprint "eagle-import:0402-RES")
      (fields (field (name "PARTNO") "ERA-2AEB103X"))
      (libsource (lib "eagle-import") (part "RESISTOR0402-RES"))
    )
    (comp (ref "U901")
      (value "TXS0108QFN20")
      (footprint "eagle-import:QFN20-RGY")
      (fields (field (name "PARTNO") "TXS0108ERGYR"))
      (libsource (lib "eagle-import") (part "TXS0108QFN20"))
    )
    (comp (ref "U902")
      (value "TXS0108QFN20")
      (footprint "eagle-import:QFN20-RGY")
      (fields (field (name "PARTNO") "TXS0108ERGYR"))
      (libsource (lib "eagle-import") (part "TXS0108QFN20"))
    )
    (comp (ref "U903")
      (value "74LVC2G240")
      (footprint "eagle-import:TSSOP8_SOT505-2")
      (fields (field (name "PARTNO") "74LVC2G240DP,125"))
      (libsource (lib "eagle-import") (part "74LVC2G240-TSSOP-8"))
    )
    (comp (ref "C1001")
      (value "10u/25V")
      (footprint "eagle-import:0805-CAP")
      (fields (field (name "PARTNO") "CL21A106KAYNNNE"))
      (libsource (lib "eagle-import") (part "CAP0805"))
    )
    (comp (ref "C1002")
      (value "10n")
      (footprint "eagle-import:0402-CAP")
      (fields (field (name "PARTNO") "CC0402KRX7R7BB103"))
      (libsource (lib "eagle-import") (part "CAP0402"))
    )
    (comp (ref "C1003")
      (value "1u")
      (footprint "eagle-import:0603-CAP")
      (fields (field (name "PARTNO") "CC0603ZRY5V7BB105"))
      (libsource (lib "eagle-import") (part "CAP0603"))
    )
    (comp (ref "C1004")
      (value "10u")
      (footprint "eagle-import:0603-CAP")
      (fields (field (name "PARTNO") "C1608X5R1A106K080AC"))
      (libsource (lib "eagle-import") (part "CAP0603"))
    )
    (comp (ref "C1005")
      (value "0u1")
      (footprint "eagle-import:0402-CAP")
      (fields (field (name "PARTNO") "CC0402ZRY5V7BB104"))
      (libsource (lib "eagle-import") (part "CAP0402"))
    )
    (comp (ref "C1008")
      (value "2u2")
      (footprint "eagle-import:0402-CAP")
      (fields (field (name "PARTNO") "C1005X6S1C225K050BC"))
      (libsource (lib "eagle-import") (part "CAP0402"))
    )
    (comp (ref "D1001")
      (value "PMEG2005CT")
      (footprint "eagle-import:SOT23-3")
      (libsource (lib "eagle-import") (part "PMEG2005CT"))
    )
    (comp (ref "F1001")
      (value "0ZCA0035FF2G")
      (footprint "eagle-import:PTC-1206")
      (libsource (lib "eagle-import") (part "PTCSMD"))
    )
    (comp (ref "R1001")
      (value "100K")
      (footprint "eagle-import:0402-RES")
      (fields (field (name "PARTNO") "RC0402FR-07100KL"))
      (libsource (lib "eagle-import") (part "RESISTOR0402-RES"))
    )
    (comp (ref "R1002")
      (value "10K")
      (footprint "eagle-import:0402-RES")
      (fields (field (name "PARTNO") "RC0402FR-0710KL"))
      (libsource (lib "eagle-import") (part "RESISTOR0402-RES"))
    )
    (comp (ref "U1001")
      (value "BQ24313")
      (footprint "eagle-import:QFN8-DSG")
      (fields (field (name "PARTNO") "BQ24313DSGT"))
      (libsource (lib "eagle-import") (part "BQ24313"))
    )
    (comp (ref "U1002")
      (value "MIC5332")
      (footprint "eagle-import:MLF-8-EPAD")
      (fields (field (name "PARTNO") "MIC5332-SSYMT"))
      (libsource (lib "eagle-import") (part "MIC5332"))
    )
    (comp (ref "C1101")
      (value "22u/25V")
      (footprint "eagle-import:0805-CAP")
      (fields (field (name "PARTNO") "CL21A226MAQNNNE"))
      (libsource (lib "eagle-import") (part "CAP0805"))
    )
    (comp (ref "C1102")
      (value "22u/25V")
      (footprint "eagle-import:0805-CAP")
      (fields (field (name "PARTNO") "CL21A226MAQNNNE"))
      (libsource (lib "eagle-import") (part "CAP0805"))
    )
    (comp (ref "C1103")
      (value "22u/25V")
      (footprint "eagle-import:0805-CAP")
      (fields (field (name "PARTNO") "CL21A226MAQNNNE"))
      (libsource (lib "eagle-import") (part "CAP0805"))
    )
    (comp (ref "C1104")
      (value "100u")
      (footprint "eagle-import:1206-CAP")
      (fields (field (name "PARTNO") "C3216X5R1A107M160AC"))
      (libsource (lib "eagle-import") (part "CAP1206"))
    )
    (comp (ref "C1105")
      (value "0u1")
      (footprint "eagle-import:0402-CAP")
      (fields (field (name "PARTNO") "C1005X7R1E104K050BB"))
      (libsource (lib "eagle-import") (part "CAP0402"))
    )
    (comp (ref "C1106")
      (value "0u1")
      (footprint "eagle-import:0402-CAP")
      (fields (field (name "PARTNO") "C1005X7R1E104K050BB"))
      (libsource (lib "eagle-import") (part "CAP0402"))
    )
    (comp (ref "C1107")
      (value "0u1")
      (footprint "eagle-import:0402-CAP")
      (fields (field (name "PARTNO") "C1005X7R1E104K050BB"))
      (libsource (lib "eagle-import") (part "CAP0402"))
    )
    (comp (ref "C1108")
      (value "10p/25V")
      (footprint "eagle-import:0402-CAP")
      (fields (field (name "PARTNO") "C0402C100J3GACTU"))
      (libsource (lib "eagle-import") (part "CAP0402"))
    )
    (comp (ref "C1109")
      (value "10p/25V")
      (footprint "eagle-import:0402-CAP")
      (fields (field (name "PARTNO") "C0402C100J3GACTU"))
      (libsource (lib "eagle-import") (part "CAP0402"))
    )
    (comp (ref "C1110")
      (value "10p/25V")
      (footprint "eagle-import:0402-CAP")
      (fields (field (name "PARTNO") "C0402C100J3GACTU"))
      (libsource (lib "eagle-import") (part "CAP0402"))
    )
    (comp (ref "J601")
      (value "DF13C-6P-1.25V")
      (footprint "eagle-import:DF13C-6P-1.25V")
      (fields (field (name "PARTNO") "DF13C-6P-1.25V(20)"))
      (libsource (lib "eagle-import") (part "DF13-6P-1.25V"))
    )
    (comp (ref "L1101")
      (value "KNH16C104DA5TS")
      (footprint "eagle-import:KYOCERA-KNH16-DA")
      (libsource (lib "eagle-import") (part "KNH16C104DA5TS"))
    )
    (comp (ref "L1102")
      (value "KNH16C104DA5TS")
      (footprint "eagle-import:KYOCERA-KNH16-DA")
      (libsource (lib "eagle-import") (part "KNH16C104DA5TS"))
    )
    (comp (ref "R1101")
      (value "10K/0.1%")
      (footprint "eagle-import:0402-RES")
      (fields (field (name "PARTNO") "ERA-2AEB103X"))
      (libsource (lib "eagle-import") (part "RESISTOR0402-RES"))
    )
    (comp (ref "R1102")
      (value "10K/0.1%")
      (footprint "eagle-import:0402-RES")
      (fields (field (name "PARTNO") "ERA-2AEB103X"))
      (libsource (lib "eagle-import") (part "RESISTOR0402-RES"))
    )
    (comp (ref "R1103")
      (value "1M")
      (footprint "eagle-import:0402-RES")
      (fields (field (name "PARTNO") "RC0402FR-071ML"))
      (libsource (lib "eagle-import") (part "RESISTOR0402-RES"))
    )
    (comp (ref "R1104")
      (value "1M")
      (footprint "eagle-import:0402-RES")
      (fields (field (name "PARTNO") "RC0402FR-071ML"))
      (libsource (lib "eagle-import") (part "RESISTOR0402-RES"))
    )
    (comp (ref "R1105")
      (value "453K")
      (footprint "eagle-import:0402-RES")
      (fields (field (name "PARTNO") "RMCF0402FT453K"))
      (libsource (lib "eagle-import") (part "RESISTOR0402-RES"))
    )
    (comp (ref "R1106")
      (value "56K")
      (footprint "eagle-import:0402-RES")
      (fields (field (name "PARTNO") "ERA-2AEB563X"))
      (libsource (lib "eagle-import") (part "RESISTOR0402-RES"))
    )
    (comp (ref "R1107")
      (value "105K")
      (footprint "eagle-import:0402-RES")
      (fields (field (name "PARTNO") "ERJ-2RKF1053X"))
      (libsource (lib "eagle-import") (part "RESISTOR0402-RES"))
    )
    (comp (ref "R1109")
      (value "453K")
      (footprint "eagle-import:0402-RES")
      (fields (field (name "PARTNO") "RMCF0402FT453K"))
      (libsource (lib "eagle-import") (part "RESISTOR0402-RES"))
    )
    (comp (ref "R1110")
      (value "56K")
      (footprint "eagle-import:0402-RES")
      (fields (field (name "PARTNO") "ERA-2AEB563X"))
      (libsource (lib "eagle-import") (part "RESISTOR0402-RES"))
    )
    (comp (ref "R1111")
      (value "105K")
      (footprint "eagle-import:0402-RES")
      (fields (field (name "PARTNO") "ERJ-2RKF1053X"))
      (libsource (lib "eagle-import") (part "RESISTOR0402-RES"))
    )
    (comp (ref "R1112")
      (value "453K")
      (footprint "eagle-import:0402-RES")
      (fields (field (name "PARTNO") "RMCF0402FT453K"))
      (libsource (lib "eagle-import") (part "RESISTOR0402-RES"))
    )
    (comp (ref "R1113")
      (value "56K")
      (footprint "eagle-import:0402-RES")
      (fields (field (name "PARTNO") "ERA-2AEB563X"))
      (libsource (lib "eagle-import") (part "RESISTOR0402-RES"))
    )
    (comp (ref "R1114")
      (value "105K")
      (footprint "eagle-import:0402-RES")
      (fields (field (name "PARTNO") "ERJ-2RKF1053X"))
      (libsource (lib "eagle-import") (part "RESISTOR0402-RES"))
    )
    (comp (ref "R1115")
      (value "0R")
      (footprint "eagle-import:0402-RES")
      (fields (field (name "PARTNO") "ERJ-2GE0R00X"))
      (libsource (lib "eagle-import") (part "RESISTOR0402-RES"))
    )
    (comp (ref "RN1101")
      (value "1M")
      (footprint "eagle-import:EXB28V")
      (fields (field (name "PARTNO") "EXB-28V105JX"))
      (libsource (lib "eagle-import") (part "4R-NEXB28V"))
    )
    (comp (ref "U1101")
      (value "LTC4417")
      (footprint "eagle-import:MO-220")
      (fields (field (name "PARTNO") "LTC4417IUF#PBF"))
      (libsource (lib "eagle-import") (part "LTC4117"))
    )
    (comp (ref "U1102")
      (value "NTHD4102PT1G")
      (footprint "eagle-import:1206-8")
      (fields (field (name "PARTNO") "NTHD4102PT1G"))
      (libsource (lib "eagle-import") (part "MOSFET-DUAL-PCHANNEL-CHIPFET"))
    )
    (comp (ref "U1103")
      (value "NTHD4102PT1G")
      (footprint "eagle-import:1206-8")
      (fields (field (name "PARTNO") "NTHD4102PT1G"))
      (libsource (lib "eagle-import") (part "MOSFET-DUAL-PCHANNEL-CHIPFET"))
    )
    (comp (ref "U1104")
      (value "NTHD4102PT1G")
      (footprint "eagle-import:1206-8")
      (fields (field (name "PARTNO") "NTHD4102PT1G"))
      (libsource (lib "eagle-import") (part "MOSFET-DUAL-PCHANNEL-CHIPFET"))
    )
    (comp (ref "J301")
      (value "47346-0001")
      (footprint "eagle-import:MOLEX-47346-0001")
      (libsource (lib "eagle-import") (part "MOLEX-47346-0001"))
    )
    (comp (ref "J302")
      (value "DF13C-4P-1.25V")
      (footprint "eagle-import:DF13C-4P-1.25V")
      (fields (field (name "PARTNO") "DF13C-4P-1.25V(20)"))
      (libsource (lib "eagle-import") (part "DF13-4P-1.25V"))
    )
    (comp (ref "JX301")
      (value "ARM_MINI_JTAG-SMT")
      (footprint "eagle-import:FTSH-105-01-XXX-DV-K")
      (fields (field (name "BOM") "EXCLUDE") (field (name "PARTNO") "M50-3900542"))
      (libsource (lib "eagle-import") (part "ARM_MINI_JTAG-SMT"))
    )
    (comp (ref "R301")
      (value "100K")
      (footprint "eagle-import:0402-RES")
      (fields (field (name "PARTNO") "RC0402FR-07100KL"))
      (libsource (lib "eagle-import") (part "RESISTOR0402-RES"))
    )
    (comp (ref "R302")
      (value "100K")
      (footprint "eagle-import:0402-RES")
      (fields (field (name "PARTNO") "RC0402FR-07100KL"))
      (libsource (lib "eagle-import") (part "RESISTOR0402-RES"))
    )
    (comp (ref "R303")
      (value "100K")
      (footprint "eagle-import:0402-RES")
      (fields (field (name "PARTNO") "RC0402FR-07100KL"))
      (libsource (lib "eagle-import") (part "RESISTOR0402-RES"))
    )
    (comp (ref "R304")
      (value "100K")
      (footprint "eagle-import:0402-RES")
      (fields (field (name "PARTNO") "RC0402FR-07100KL"))
      (libsource (lib "eagle-import") (part "RESISTOR0402-RES"))
    )
    (comp (ref "R305")
      (value "100K")
      (footprint "eagle-import:0402-RES")
      (fields (field (name "PARTNO") "RC0402FR-07100KL"))
      (libsource (lib "eagle-import") (part "RESISTOR0402-RES"))
    )
    (comp (ref "R306")
      (value "1K5")
      (footprint "eagle-import:0402-RES")
      (fields (field (name "PARTNO") "RC0402FR-071K5L"))
      (libsource (lib "eagle-import") (part "RESISTOR0402-RES"))
    )
    (comp (ref "R307")
      (value "1K5")
      (footprint "eagle-import:0402-RES")
      (fields (field (name "PARTNO") "RC0402FR-071K5L"))
      (libsource (lib "eagle-import") (part "RESISTOR0402-RES"))
    )
    (comp (ref "U301")
      (value "2908-05WB-MG")
      (footprint "eagle-import:MICROSD")
      (libsource (lib "eagle-import") (part "MICROSDSDI"))
    )
    (comp (ref "U302")
      (value "NUF2042XV6")
      (footprint "eagle-import:SOT563-6")
      (fields (field (name "PARTNO") "NUF2042XV6T1G"))
      (libsource (lib "eagle-import") (part "NUF2042XV6"))
    )
    (comp (ref "C201")
      (value "0u1")
      (footprint "eagle-import:0402-CAP")
      (fields (field (name "PARTNO") "CC0402ZRY5V7BB104"))
      (libsource (lib "eagle-import") (part "CAP0402"))
    )
    (comp (ref "C202")
      (value "0u1")
      (footprint "eagle-import:0402-CAP")
      (fields (field (name "PARTNO") "CC0402ZRY5V7BB104"))
      (libsource (lib "eagle-import") (part "CAP0402"))
    )
    (comp (ref "D201")
      (value "PESD0402-140")
      (footprint "eagle-import:0402-TVS")
      (libsource (lib "eagle-import") (part "DIODE-TVS"))
    )
    (comp (ref "D202")
      (value "PESD0402-140")
      (footprint "eagle-import:0402-TVS")
      (libsource (lib "eagle-import") (part "DIODE-TVS"))
    )
    (comp (ref "D203")
      (value "PESD0402-140")
      (footprint "eagle-import:0402-TVS")
      (libsource (lib "eagle-import") (part "DIODE-TVS"))
    )
    (comp (ref "J201")
      (value "DF13C-6P-1.25V")
      (footprint "eagle-import:DF13C-6P-1.25V")
      (fields (field (name "PARTNO") "DF13C-6P-1.25V(20)"))
      (libsource (lib "eagle-import") (part "DF13-6P-1.25V"))
    )
    (comp (ref "J202")
      (value "DF13C-6P-1.25V")
      (footprint "eagle-import:DF13C-6P-1.25V")
      (fields (field (name "PARTNO") "DF13C-6P-1.25V(20)"))
      (libsource (lib "eagle-import") (part "DF13-6P-1.25V"))
    )
    (comp (ref "J203")
      (value "DF13C-6P-1.25V")
      (footprint "eagle-import:DF13C-6P-1.25V")
      (fields (field (name "PARTNO") "DF13C-6P-1.25V(20)"))
      (libsource (lib "eagle-import") (part "DF13-6P-1.25V"))
    )
    (comp (ref "J204")
      (value "DF13C-6P-1.25V")
      (footprint "eagle-import:DF13C-6P-1.25V")
      (fields (field (name "PARTNO") "DF13C-6P-1.25V(20)"))
      (libsource (lib "eagle-import") (part "DF13-6P-1.25V"))
    )
    (comp (ref "L201")
      (value "KNH16C104DA5TS")
      (footprint "eagle-import:KYOCERA-KNH16-DA")
      (libsource (lib "eagle-import") (part "KNH16C104DA5TS"))
    )
    (comp (ref "L202")
      (value "KNH16C104DA5TS")
      (footprint "eagle-import:KYOCERA-KNH16-DA")
      (libsource (lib "eagle-import") (part "KNH16C104DA5TS"))
    )
    (comp (ref "L203")
      (value "KNH16C104DA5TS")
      (footprint "eagle-import:KYOCERA-KNH16-DA")
      (libsource (lib "eagle-import") (part "KNH16C104DA5TS"))
    )
    (comp (ref "R201")
      (value "120R")
      (footprint "eagle-import:0402-RES")
      (fields (field (name "PARTNO") "RC0402FR-07120RL"))
      (libsource (lib "eagle-import") (part "RESISTOR0402-RES"))
    )
    (comp (ref "R202")
      (value "120R")
      (footprint "eagle-import:0402-RES")
      (fields (field (name "PARTNO") "RC0402FR-07120RL"))
      (libsource (lib "eagle-import") (part "RESISTOR0402-RES"))
    )
    (comp (ref "R203")
      (value "120R")
      (footprint "eagle-import:0402-RES")
      (fields (field (name "PARTNO") "RC0402FR-07120RL"))
      (libsource (lib "eagle-import") (part "RESISTOR0402-RES"))
    )
    (comp (ref "R204")
      (value "120R")
      (footprint "eagle-import:0402-RES")
      (fields (field (name "PARTNO") "RC0402FR-07120RL"))
      (libsource (lib "eagle-import") (part "RESISTOR0402-RES"))
    )
    (comp (ref "R205")
      (value "120R")
      (footprint "eagle-import:0402-RES")
      (fields (field (name "PARTNO") "RC0402FR-07120RL"))
      (libsource (lib "eagle-import") (part "RESISTOR0402-RES"))
    )
    (comp (ref "R206")
      (value "120R")
      (footprint "eagle-import:0402-RES")
      (fields (field (name "PARTNO") "RC0402FR-07120RL"))
      (libsource (lib "eagle-import") (part "RESISTOR0402-RES"))
    )
    (comp (ref "R207")
      (value "120R")
      (footprint "eagle-import:0402-RES")
      (fields (field (name "PARTNO") "RC0402FR-07120RL"))
      (libsource (lib "eagle-import") (part "RESISTOR0402-RES"))
    )
    (comp (ref "R208")
      (value "120R")
      (footprint "eagle-import:0402-RES")
      (fields (field (name "PARTNO") "RC0402FR-07120RL"))
      (libsource (lib "eagle-import") (part "RESISTOR0402-RES"))
    )
    (comp (ref "R209")
      (value "120R")
      (footprint "eagle-import:0402-RES")
      (fields (field (name "PARTNO") "RC0402FR-07120RL"))
      (libsource (lib "eagle-import") (part "RESISTOR0402-RES"))
    )
    (comp (ref "R210")
      (value "120R")
      (footprint "eagle-import:0402-RES")
      (fields (field (name "PARTNO") "RC0402FR-07120RL"))
      (libsource (lib "eagle-import") (part "RESISTOR0402-RES"))
    )
    (comp (ref "R211")
      (value "120R")
      (footprint "eagle-import:0402-RES")
      (fields (field (name "PARTNO") "RC0402FR-07120RL"))
      (libsource (lib "eagle-import") (part "RESISTOR0402-RES"))
    )
    (comp (ref "R212")
      (value "120R")
      (footprint "eagle-import:0402-RES")
      (fields (field (name "PARTNO") "RC0402FR-07120RL"))
      (libsource (lib "eagle-import") (part "RESISTOR0402-RES"))
    )
    (comp (ref "R213")
      (value "120R")
      (footprint "eagle-import:0402-RES")
      (fields (field (name "PARTNO") "RC0402FR-07120RL"))
      (libsource (lib "eagle-import") (part "RESISTOR0402-RES"))
    )
    (comp (ref "R214")
      (value "120R")
      (footprint "eagle-import:0402-RES")
      (fields (field (name "PARTNO") "RC0402FR-07120RL"))
      (libsource (lib "eagle-import") (part "RESISTOR0402-RES"))
    )
    (comp (ref "R215")
      (value "120R")
      (footprint "eagle-import:0402-RES")
      (fields (field (name "PARTNO") "RC0402FR-07120RL"))
      (libsource (lib "eagle-import") (part "RESISTOR0402-RES"))
    )
    (comp (ref "R216")
      (value "120R")
      (footprint "eagle-import:0402-RES")
      (fields (field (name "PARTNO") "RC0402FR-07120RL"))
      (libsource (lib "eagle-import") (part "RESISTOR0402-RES"))
    )
    (comp (ref "U201")
      (value "TXS0108QFN20")
      (footprint "eagle-import:QFN20-RGY")
      (fields (field (name "PARTNO") "TXS0108ERGYR"))
      (libsource (lib "eagle-import") (part "TXS0108QFN20"))
    )
    (comp (ref "U202")
      (value "TXS0108QFN20")
      (footprint "eagle-import:QFN20-RGY")
      (fields (field (name "PARTNO") "TXS0108ERGYR"))
      (libsource (lib "eagle-import") (part "TXS0108QFN20"))
    )
    (comp (ref "C801")
      (value "0u1")
      (footprint "eagle-import:0402-CAP")
      (fields (field (name "PARTNO") "CC0402ZRY5V7BB104"))
      (libsource (lib "eagle-import") (part "CAP0402"))
    )
    (comp (ref "C802")
      (value "0u1")
      (footprint "eagle-import:0402-CAP")
      (fields (field (name "PARTNO") "CC0402ZRY5V7BB104"))
      (libsource (lib "eagle-import") (part "CAP0402"))
    )
    (comp (ref "C803")
      (value "0u1")
      (footprint "eagle-import:0402-CAP")
      (fields (field (name "PARTNO") "CC0402ZRY5V7BB104"))
      (libsource (lib "eagle-import") (part "CAP0402"))
    )
    (comp (ref "C804")
      (value "0u1")
      (footprint "eagle-import:0402-CAP")
      (fields (field (name "PARTNO") "CC0402ZRY5V7BB104"))
      (libsource (lib "eagle-import") (part "CAP0402"))
    )
    (comp (ref "C805")
      (value "8p")
      (footprint "eagle-import:0402-CAP")
      (fields (field (name "PARTNO") "C1005C0G1H080C"))
      (libsource (lib "eagle-import") (part "CAP0402"))
    )
    (comp (ref "C806")
      (value "8p")
      (footprint "eagle-import:0402-CAP")
      (fields (field (name "PARTNO") "C1005C0G1H080C"))
      (libsource (lib "eagle-import") (part "CAP0402"))
    )
    (comp (ref "D801")
      (value "PESD0402-140")
      (footprint "eagle-import:0402-TVS")
      (libsource (lib "eagle-import") (part "DIODE-TVS"))
    )
    (comp (ref "J801")
      (value "JST-ZH-3")
      (footprint "eagle-import:JST-ZH-SMT-VERTICAL")
      (fields (field (name "PARTNO") "B3B-ZR-SM4-TF (LF)(SN)(P)"))
      (libsource (lib "eagle-import") (part "JST-ZH-3"))
    )
    (comp (ref "JX801")
      (value "HEADER-3X1BOARDEDGE-SHORT")
      (footprint "eagle-import:HEADER_3X01_SMD_H_BOARD_EDGE_SHORT")
      (libsource (lib "eagle-import") (part "HEADER-3X1BOARDEDGE-SHORT"))
    )
    (comp (ref "JX802")
      (value "ARM_MINI_JTAG-SMT")
      (footprint "eagle-import:FTSH-105-01-XXX-DV-K")
      (fields (field (name "BOM") "EXCLUDE") (field (name "PARTNO") "M50-3900542"))
      (libsource (lib "eagle-import") (part "ARM_MINI_JTAG-SMT"))
    )
    (comp (ref "R801")
      (value "10K")
      (footprint "eagle-import:0402-RES")
      (fields (field (name "PARTNO") "RC0402FR-0710KL"))
      (libsource (lib "eagle-import") (part "RESISTOR0402-RES"))
    )
    (comp (ref "R802")
      (value "10K")
      (footprint "eagle-import:0402-RES")
      (fields (field (name "PARTNO") "RC0402FR-0710KL"))
      (libsource (lib "eagle-import") (part "RESISTOR0402-RES"))
    )
    (comp (ref "R803")
      (value "220R")
      (footprint "eagle-import:0402-RES")
      (fields (field (name "PARTNO") "RC0402FR-07220RL"))
      (libsource (lib "eagle-import") (part "RESISTOR0402-RES"))
    )
    (comp (ref "R804")
      (value "220R")
      (footprint "eagle-import:0402-RES")
      (fields (field (name "PARTNO") "RC0402FR-07220RL"))
      (libsource (lib "eagle-import") (part "RESISTOR0402-RES"))
    )
    (comp (ref "S801")
      (value "RESET")
      (footprint "eagle-import:EVQP7J01K")
      (fields (field (name "PARTNO") "EVQ-P7J01P"))
      (libsource (lib "eagle-import") (part "SWITCH-MOMENTARY-2"))
    )
    (comp (ref "U801")
      (value "STM32F10XCXT6")
      (footprint "eagle-import:TQFP48")
      (fields (field (name "PARTNO") "STM32F100C8T6B"))
      (libsource (lib "eagle-import") (part "STM32F10XCXT6"))
    )
    (comp (ref "X801")
      (value "3.2x2.5 mm / 24 MHz / 15 ppm")
      (footprint "eagle-import:OSCILLATOR-3.2X2.5")
      (fields (field (name "PARTNO") "NX3225SA-24.000000MHZ"))
      (libsource (lib "eagle-import") (part "OSCILLATOR-3.2X2.5"))
    )
    (comp (ref "C401")
      (value "0u1")
      (footprint "eagle-import:0402-CAP")
      (fields (field (name "PARTNO") "CC0402ZRY5V7BB104"))
      (libsource (lib "eagle-import") (part "CAP0402"))
    )
    (comp (ref "C402")
      (value "0u1")
      (footprint "eagle-import:0402-CAP")
      (fields (field (name "PARTNO") "CC0402ZRY5V7BB104"))
      (libsource (lib "eagle-import") (part "CAP0402"))
    )
    (comp (ref "D401")
      (value "PESD0402-140")
      (footprint "eagle-import:0402-TVS")
      (libsource (lib "eagle-import") (part "DIODE-TVS"))
    )
    (comp (ref "D402")
      (value "PESD0402-140")
      (footprint "eagle-import:0402-TVS")
      (libsource (lib "eagle-import") (part "DIODE-TVS"))
    )
    (comp (ref "D403")
      (value "PESD0402-140")
      (footprint "eagle-import:0402-TVS")
      (libsource (lib "eagle-import") (part "DIODE-TVS"))
    )
    (comp (ref "D404")
      (value "PESD0402-140")
      (footprint "eagle-import:0402-TVS")
      (libsource (lib "eagle-import") (part "DIODE-TVS"))
    )
    (comp (ref "J401")
      (value "DF13C-4P-1.25V")
      (footprint "eagle-import:DF13C-4P-1.25V")
      (fields (field (name "PARTNO") "DF13C-4P-1.25V(20)"))
      (libsource (lib "eagle-import") (part "DF13-4P-1.25V"))
    )
    (comp (ref "J402")
      (value "DF13C-3P-1.25V")
      (footprint "eagle-import:DF13C-3P-1.25V")
      (fields (field (name "PARTNO") "DF13C-3P-1.25V(20)"))
      (libsource (lib "eagle-import") (part "DF13-3P-1.25V"))
    )
    (comp (ref "J403")
      (value "DF13C-7P-1.25V")
      (footprint "eagle-import:DF13C-7P-1.25V")
      (fields (field (name "PARTNO") "DF13C-7P-1.25V(20)"))
      (libsource (lib "eagle-import") (part "DF13-7P-1.25V"))
    )
    (comp (ref "J404")
      (value "DF13C-5P-1.25V")
      (footprint "eagle-import:DF13C-5P-1.25V")
      (fields (field (name "PARTNO") "DF13C-5P-1.25V(20)"))
      (libsource (lib "eagle-import") (part "DF13-5P-1.25V"))
    )
    (comp (ref "J405")
      (value "DF13C-4P-1.25V")
      (footprint "eagle-import:DF13C-4P-1.25V")
      (fields (field (name "PARTNO") "DF13C-4P-1.25V(20)"))
      (libsource (lib "eagle-import") (part "DF13-4P-1.25V"))
    )
    (comp (ref "L401")
      (value "KNH16C104DA5TS")
      (footprint "eagle-import:KYOCERA-KNH16-DA")
      (libsource (lib "eagle-import") (part "KNH16C104DA5TS"))
    )
    (comp (ref "L402")
      (value "KNH16C104DA5TS")
      (footprint "eagle-import:KYOCERA-KNH16-DA")
      (libsource (lib "eagle-import") (part "KNH16C104DA5TS"))
    )
    (comp (ref "L403")
      (value "KNH16C104DA5TS")
      (footprint "eagle-import:KYOCERA-KNH16-DA")
      (libsource (lib "eagle-import") (part "KNH16C104DA5TS"))
    )
    (comp (ref "L404")
      (value "KNH16C104DA5TS")
      (footprint "eagle-import:KYOCERA-KNH16-DA")
      (libsource (lib "eagle-import") (part "KNH16C104DA5TS"))
    )
    (comp (ref "R401")
      (value "1K5")
      (footprint "eagle-import:0402-RES")
      (fields (field (name "PARTNO") "RC0402FR-071K5L"))
      (libsource (lib "eagle-import") (part "RESISTOR0402-RES"))
    )
    (comp (ref "R402")
      (value "1K5")
      (footprint "eagle-import:0402-RES")
      (fields (field (name "PARTNO") "RC0402FR-071K5L"))
      (libsource (lib "eagle-import") (part "RESISTOR0402-RES"))
    )
    (comp (ref "R403")
      (value "10K/0.1%")
      (footprint "eagle-import:0402-RES")
      (fields (field (name "PARTNO") "ERA-2AEB103X"))
      (libsource (lib "eagle-import") (part "RESISTOR0402-RES"))
    )
    (comp (ref "R404")
      (value "120R")
      (footprint "eagle-import:0402-RES")
      (fields (field (name "PARTNO") "RC0402FR-07120RL"))
      (libsource (lib "eagle-import") (part "RESISTOR0402-RES"))
    )
    (comp (ref "R405")
      (value "120R")
      (footprint "eagle-import:0402-RES")
      (fields (field (name "PARTNO") "RC0402FR-07120RL"))
      (libsource (lib "eagle-import") (part "RESISTOR0402-RES"))
    )
    (comp (ref "R406")
      (value "10K/0.1%")
      (footprint "eagle-import:0402-RES")
      (fields (field (name "PARTNO") "ERA-2AEB103X"))
      (libsource (lib "eagle-import") (part "RESISTOR0402-RES"))
    )
    (comp (ref "R407")
      (value "10K/0.1%")
      (footprint "eagle-import:0402-RES")
      (fields (field (name "PARTNO") "ERA-2AEB103X"))
      (libsource (lib "eagle-import") (part "RESISTOR0402-RES"))
    )
    (comp (ref "R408")
      (value "10K/0.1%")
      (footprint "eagle-import:0402-RES")
      (fields (field (name "PARTNO") "ERA-2AEB103X"))
      (libsource (lib "eagle-import") (part "RESISTOR0402-RES"))
    )
    (comp (ref "R409")
      (value "120R")
      (footprint "eagle-import:0402-RES")
      (fields (field (name "PARTNO") "RC0402FR-07120RL"))
      (libsource (lib "eagle-import") (part "RESISTOR0402-RES"))
    )
    (comp (ref "U401")
      (value "MAX3051")
      (footprint "eagle-import:SOT23-8")
      (fields (field (name "PARTNO") "MAX3051EKA"))
      (libsource (lib "eagle-import") (part "MAX3051MAX3051EKA"))
    )
    (comp (ref "!VBUS_VALID")
      (value "PAD.04")
      (footprint "eagle-import:PAD.04X.04")
      (libsource (lib "eagle-import") (part "PAD.04"))
    )
    (comp (ref "!VDD_BRICK_VALID")
      (value "PAD.04")
      (footprint "eagle-import:PAD.04X.04")
      (libsource (lib "eagle-import") (part "PAD.04"))
    )
    (comp (ref "!VDD_SERVO_VALID")
      (value "PAD.04")
      (footprint "eagle-import:PAD.04X.04")
      (libsource (lib "eagle-import") (part "PAD.04"))
    )
    (comp (ref "ADC_PR")
      (value "PAD.04")
      (footprint "eagle-import:PAD.04X.04")
      (libsource (lib "eagle-import") (part "PAD.04"))
    )
    (comp (ref "CAN_H")
      (value "PAD.04")
      (footprint "eagle-import:PAD.04X.04")
      (libsource (lib "eagle-import") (part "PAD.04"))
    )
    (comp (ref "CAN_L")
      (value "PAD.04")
      (footprint "eagle-import:PAD.04X.04")
      (libsource (lib "eagle-import") (part "PAD.04"))
    )
    (comp (ref "FMU-BOOT1101")
      (value "PAD.04")
      (footprint "eagle-import:PAD.04X.04")
      (libsource (lib "eagle-import") (part "PAD.04"))
    )
    (comp (ref "GND")
      (value "PAD.04")
      (footprint "eagle-import:PAD.04X.04")
      (libsource (lib "eagle-import") (part "PAD.04"))
    )
    (comp (ref "GND.")
      (value "PAD.04")
      (footprint "eagle-import:PAD.04X.04")
      (libsource (lib "eagle-import") (part "PAD.04"))
    )
    (comp (ref "IO-BOOT1101")
      (value "PAD.04")
      (footprint "eagle-import:PAD.04X.04")
      (libsource (lib "eagle-import") (part "PAD.04"))
    )
    (comp (ref "JP1")
      (value "FIDUCIAL1.5X3")
      (footprint "eagle-import:FIDUCIAL-1.5X3")
      (libsource (lib "eagle-import") (part "FIDUCIAL1.5X3"))
    )
    (comp (ref "JP2")
      (value "FIDUCIAL1.5X3")
      (footprint "eagle-import:FIDUCIAL-1.5X3")
      (libsource (lib "eagle-import") (part "FIDUCIAL1.5X3"))
    )
    (comp (ref "M3_MOUNT1101")
      (value "MOUNT-HOLE3.1MM")
      (footprint "eagle-import:MOUNT-HOLE3.1")
      (libsource (lib "eagle-import") (part "MOUNT-HOLE3.1MM"))
    )
    (comp (ref "M3_MOUNT1102")
      (value "MOUNT-HOLE3.1MM")
      (footprint "eagle-import:MOUNT-HOLE3.1")
      (libsource (lib "eagle-import") (part "MOUNT-HOLE3.1MM"))
    )
    (comp (ref "M3_MOUNT1103")
      (value "MOUNT-HOLE3.1MM")
      (footprint "eagle-import:MOUNT-HOLE3.1")
      (libsource (lib "eagle-import") (part "MOUNT-HOLE3.1MM"))
    )
    (comp (ref "M3_MOUNT1104")
      (value "MOUNT-HOLE3.1MM")
      (footprint "eagle-import:MOUNT-HOLE3.1")
      (libsource (lib "eagle-import") (part "MOUNT-HOLE3.1MM"))
    )
    (comp (ref "OSHW_LOGO")
      (value "OSHW-LOGOS")
      (footprint "eagle-import:OSHW-LOGO-S")
      (libsource (lib "eagle-import") (part "OSHW-LOGOS"))
    )
    (comp (ref "S1RX")
      (value "PAD.04")
      (footprint "eagle-import:PAD.04X.04")
      (libsource (lib "eagle-import") (part "PAD.04"))
    )
    (comp (ref "S1TX")
      (value "PAD.04")
      (footprint "eagle-import:PAD.04X.04")
      (libsource (lib "eagle-import") (part "PAD.04"))
    )
    (comp (ref "S2RX")
      (value "PAD.04")
      (footprint "eagle-import:PAD.04X.04")
      (libsource (lib "eagle-import") (part "PAD.04"))
    )
    (comp (ref "S2TX")
      (value "PAD.04")
      (footprint "eagle-import:PAD.04X.04")
      (libsource (lib "eagle-import") (part "PAD.04"))
    )
    (comp (ref "S3RX")
      (value "PAD.04")
      (footprint "eagle-import:PAD.04X.04")
      (libsource (lib "eagle-import") (part "PAD.04"))
    )
    (comp (ref "S3TX")
      (value "PAD.04")
      (footprint "eagle-import:PAD.04X.04")
      (libsource (lib "eagle-import") (part "PAD.04"))
    )
    (comp (ref "S4RX")
      (value "PAD.04")
      (footprint "eagle-import:PAD.04X.04")
      (libsource (lib "eagle-import") (part "PAD.04"))
    )
    (comp (ref "S4TX")
      (value "PAD.04")
      (footprint "eagle-import:PAD.04X.04")
      (libsource (lib "eagle-import") (part "PAD.04"))
    )
    (comp (ref "S5_RX")
      (value "PAD.04")
      (footprint "eagle-import:PAD.04X.04")
      (libsource (lib "eagle-import") (part "PAD.04"))
    )
    (comp (ref "S5_TX")
      (value "PAD.04")
      (footprint "eagle-import:PAD.04X.04")
      (libsource (lib "eagle-import") (part "PAD.04"))
    )
    (comp (ref "VBUS")
      (value "PAD.04")
      (footprint "eagle-import:PAD.04X.04")
      (libsource (lib "eagle-import") (part "PAD.04"))
    )
    (comp (ref "VDDA_3V1101")
      (value "PAD.04")
      (footprint "eagle-import:PAD.04X.04")
      (libsource (lib "eagle-import") (part "PAD.04"))
    )
    (comp (ref "VDD_3V1101")
      (value "PAD.04")
      (footprint "eagle-import:PAD.04X.04")
      (libsource (lib "eagle-import") (part "PAD.04"))
    )
    (comp (ref "VDD_5V_BRICK")
      (value "PAD.04")
      (footprint "eagle-import:PAD.04X.04")
      (libsource (lib "eagle-import") (part "PAD.04"))
    )
    (comp (ref "VDD_5V_IN")
      (value "PAD.04")
      (footprint "eagle-import:PAD.04X.04")
      (libsource (lib "eagle-import") (part "PAD.04"))
    )
    (comp (ref "VDD_SERVO")
      (value "PAD.04")
      (footprint "eagle-import:PAD.04X.04")
      (libsource (lib "eagle-import") (part "PAD.04"))
    )
    (comp (ref "B601")
      (value "MS621FE")
      (footprint "eagle-import:MS621FE")
      (fields (field (name "PARTNO") "MS621FE-FL11E"))
      (libsource (lib "eagle-import") (part "MS621FE"))
    )
    (comp (ref "C601")
      (value "10u/25V")
      (footprint "eagle-import:0805-CAP")
      (fields (field (name "PARTNO") "CL21A106KAYNNNE"))
      (libsource (lib "eagle-import") (part "CAP0805"))
    )
    (comp (ref "C602")
      (value "10n")
      (footprint "eagle-import:0402-CAP")
      (fields (field (name "PARTNO") "CC0402KRX7R7BB103"))
      (libsource (lib "eagle-import") (part "CAP0402"))
    )
    (comp (ref "C603")
      (value "1u")
      (footprint "eagle-import:0603-CAP")
      (fields (field (name "PARTNO") "CC0603ZRY5V7BB105"))
      (libsource (lib "eagle-import") (part "CAP0603"))
    )
    (comp (ref "C604")
      (value "22u/25V")
      (footprint "eagle-import:0805-CAP")
      (fields (field (name "PARTNO") "CL21A226MAQNNNE"))
      (libsource (lib "eagle-import") (part "CAP0805"))
    )
    (comp (ref "C605")
      (value "22u/25V")
      (footprint "eagle-import:0805-CAP")
      (fields (field (name "PARTNO") "CL21A226MAQNNNE"))
      (libsource (lib "eagle-import") (part "CAP0805"))
    )
    (comp (ref "C606")
      (value "0u1")
      (footprint "eagle-import:0402-CAP")
      (fields (field (name "PARTNO") "CC0402ZRY5V7BB104"))
      (libsource (lib "eagle-import") (part "CAP0402"))
    )
    (comp (ref "C607")
      (value "0u1")
      (footprint "eagle-import:0402-CAP")
      (fields (field (name "PARTNO") "CC0402ZRY5V7BB104"))
      (libsource (lib "eagle-import") (part "CAP0402"))
    )
    (comp (ref "C608")
      (value "0u1")
      (footprint "eagle-import:0402-CAP")
      (fields (field (name "PARTNO") "CC0402ZRY5V7BB104"))
      (libsource (lib "eagle-import") (part "CAP0402"))
    )
    (comp (ref "C609")
      (value "0u1")
      (footprint "eagle-import:0402-CAP")
      (fields (field (name "PARTNO") "CC0402ZRY5V7BB104"))
      (libsource (lib "eagle-import") (part "CAP0402"))
    )
    (comp (ref "C610")
      (value "0u1")
      (footprint "eagle-import:0402-CAP")
      (fields (field (name "PARTNO") "CC0402ZRY5V7BB104"))
      (libsource (lib "eagle-import") (part "CAP0402"))
    )
    (comp (ref "C611")
      (value "2u2")
      (footprint "eagle-import:0603-CAP")
      (fields (field (name "PARTNO") "C1608X6S1C225K080AC"))
      (libsource (lib "eagle-import") (part "CAP0603"))
    )
    (comp (ref "C612")
      (value "0u1")
      (footprint "eagle-import:0402-CAP")
      (fields (field (name "PARTNO") "CC0402ZRY5V7BB104"))
      (libsource (lib "eagle-import") (part "CAP0402"))
    )
    (comp (ref "C613")
      (value "2u2")
      (footprint "eagle-import:0603-CAP")
      (fields (field (name "PARTNO") "C1608X6S1C225K080AC"))
      (libsource (lib "eagle-import") (part "CAP0603"))
    )
    (comp (ref "C614")
      (value "100u")
      (footprint "eagle-import:1206-CAP")
      (fields (field (name "PARTNO") "C3216X5R1A107M160AC"))
      (libsource (lib "eagle-import") (part "CAP1206"))
    )
    (comp (ref "C615")
      (value "0u1")
      (footprint "eagle-import:0402-CAP")
      (fields (field (name "PARTNO") "CC0402ZRY5V7BB104"))
      (libsource (lib "eagle-import") (part "CAP0402"))
    )
    (comp (ref "C616")
      (value "0u1")
      (footprint "eagle-import:0402-CAP")
      (fields (field (name "PARTNO") "CC0402ZRY5V7BB104"))
      (libsource (lib "eagle-import") (part "CAP0402"))
    )
    (comp (ref "C617")
      (value "0u1")
      (footprint "eagle-import:0402-CAP")
      (fields (field (name "PARTNO") "CC0402ZRY5V7BB104"))
      (libsource (lib "eagle-import") (part "CAP0402"))
    )
    (comp (ref "C618")
      (value "100u")
      (footprint "eagle-import:1206-CAP")
      (fields (field (name "PARTNO") "C3216X5R1A107M160AC"))
      (libsource (lib "eagle-import") (part "CAP1206"))
    )
    (comp (ref "D602")
      (value "RB751V40T1G")
      (footprint "eagle-import:SOD323")
      (libsource (lib "eagle-import") (part "DIODE-SCHOTTKY_SOD323"))
    )
    (comp (ref "L603")
      (value "KNH16C104DA5TS")
      (footprint "eagle-import:KYOCERA-KNH16-DA")
      (libsource (lib "eagle-import") (part "KNH16C104DA5TS"))
    )
    (comp (ref "R602")
      (value "1M")
      (footprint "eagle-import:0402-RES")
      (fields (field (name "PARTNO") "RC0402FR-071ML"))
      (libsource (lib "eagle-import") (part "RESISTOR0402-RES"))
    )
    (comp (ref "R603")
      (value "10K")
      (footprint "eagle-import:0402-RES")
      (fields (field (name "PARTNO") "RC0402FR-0710KL"))
      (libsource (lib "eagle-import") (part "RESISTOR0402-RES"))
    )
    (comp (ref "R604")
      (value "1M")
      (footprint "eagle-import:0402-RES")
      (fields (field (name "PARTNO") "RC0402FR-071ML"))
      (libsource (lib "eagle-import") (part "RESISTOR0402-RES"))
    )
    (comp (ref "R608")
      (value "1K")
      (footprint "eagle-import:0402-RES")
      (fields (field (name "PARTNO") "RC0402FR-071KL"))
      (libsource (lib "eagle-import") (part "RESISTOR0402-RES"))
    )
    (comp (ref "R609")
      (value "10K/0.1%")
      (footprint "eagle-import:0402-RES")
      (fields (field (name "PARTNO") "ERA-2AEB103X"))
      (libsource (lib "eagle-import") (part "RESISTOR0402-RES"))
    )
    (comp (ref "R610")
      (value "10K/0.1%")
      (footprint "eagle-import:0402-RES")
      (fields (field (name "PARTNO") "ERA-2AEB103X"))
      (libsource (lib "eagle-import") (part "RESISTOR0402-RES"))
    )
    (comp (ref "R611")
      (value "10K")
      (footprint "eagle-import:0402-RES")
      (fields (field (name "PARTNO") "RC0402FR-0710KL"))
      (libsource (lib "eagle-import") (part "RESISTOR0402-RES"))
    )
    (comp (ref "R615")
      (value "10K")
      (footprint "eagle-import:0402-RES")
      (fields (field (name "PARTNO") "RC0402FR-0710KL"))
      (libsource (lib "eagle-import") (part "RESISTOR0402-RES"))
    )
    (comp (ref "R616")
      (value "25K5")
      (footprint "eagle-import:0402-RES")
      (fields (field (name "PARTNO") "RMCF0402FT25K5"))
      (libsource (lib "eagle-import") (part "RESISTOR0402-RES"))
    )
    (comp (ref "R617")
      (value "16K5")
      (footprint "eagle-import:0402-RES")
      (fields (field (name "PARTNO") "RMCF0402FT16K5"))
      (libsource (lib "eagle-import") (part "RESISTOR0402-RES"))
    )
    (comp (ref "R621")
      (value "220R")
      (footprint "eagle-import:0603-RES")
      (fields (field (name "PARTNO") "RC1608J100CS"))
      (libsource (lib "eagle-import") (part "RESISTOR0603-RES"))
    )
    (comp (ref "R635")
      (value "10K")
      (footprint "eagle-import:0402-RES")
      (fields (field (name "PARTNO") "RC0402FR-0710KL"))
      (libsource (lib "eagle-import") (part "RESISTOR0402-RES"))
    )
    (comp (ref "S601")
      (value "RESET")
      (footprint "eagle-import:EVQP7J01K")
      (fields (field (name "PARTNO") "EVQ-P7J01P"))
      (libsource (lib "eagle-import") (part "SWITCH-MOMENTARY-2"))
    )
    (comp (ref "U601")
      (value "BQ24315")
      (footprint "eagle-import:QFN8-DSG")
      (fields (field (name "PARTNO") "BQ24315DSGR"))
      (libsource (lib "eagle-import") (part "BQ24315"))
    )
    (comp (ref "U602")
      (value "BQ24315")
      (footprint "eagle-import:QFN8-DSG")
      (fields (field (name "PARTNO") "BQ24315DSGR"))
      (libsource (lib "eagle-import") (part "BQ24315"))
    )
    (comp (ref "U603")
      (value "MIC5332")
      (footprint "eagle-import:MLF-8-EPAD")
      (fields (field (name "PARTNO") "MIC5332-SSYMT"))
      (libsource (lib "eagle-import") (part "MIC5332"))
    )
    (comp (ref "C501")
      (value "10u/10V")
      (footprint "eagle-import:0805-CAP")
      (fields (field (name "PARTNO") "CC0805ZKY5V6BB106"))
      (libsource (lib "eagle-import") (part "CAP0805"))
    )
    (comp (ref "C502")
      (value "0u1")
      (footprint "eagle-import:0402-CAP")
      (fields (field (name "PARTNO") "CC0402ZRY5V7BB104"))
      (libsource (lib "eagle-import") (part "CAP0402"))
    )
    (comp (ref "C503")
      (value "0u1")
      (footprint "eagle-import:0402-CAP")
      (fields (field (name "PARTNO") "CC0402ZRY5V7BB104"))
      (libsource (lib "eagle-import") (part "CAP0402"))
    )
    (comp (ref "C504")
      (value "10n")
      (footprint "eagle-import:0402-CAP")
      (fields (field (name "PARTNO") "CC0402KRX7R7BB103"))
      (libsource (lib "eagle-import") (part "CAP0402"))
    )
    (comp (ref "C505")
      (value "10n")
      (footprint "eagle-import:0402-CAP")
      (fields (field (name "PARTNO") "CC0402KRX7R7BB103"))
      (libsource (lib "eagle-import") (part "CAP0402"))
    )
    (comp (ref "C506")
      (value "10u/10V")
      (footprint "eagle-import:0805-CAP")
      (fields (field (name "PARTNO") "CC0805ZKY5V6BB106"))
      (libsource (lib "eagle-import") (part "CAP0805"))
    )
    (comp (ref "C507")
      (value "0u1")
      (footprint "eagle-import:0402-CAP")
      (fields (field (name "PARTNO") "CC0402ZRY5V7BB104"))
      (libsource (lib "eagle-import") (part "CAP0402"))
    )
    (comp (ref "C508")
      (value "0u1")
      (footprint "eagle-import:0402-CAP")
      (fields (field (name "PARTNO") "CC0402ZRY5V7BB104"))
      (libsource (lib "eagle-import") (part "CAP0402"))
    )
    (comp (ref "C509")
      (value "10u/10V")
      (footprint "eagle-import:0805-CAP")
      (fields (field (name "PARTNO") "CC0805ZKY5V6BB106"))
      (libsource (lib "eagle-import") (part "CAP0805"))
    )
    (comp (ref "C510")
      (value "0u47")
      (footprint "eagle-import:0402-CAP")
      (fields (field (name "PARTNO") "C1005X5R1C474K050BC"))
      (libsource (lib "eagle-import") (part "CAP0402"))
    )
    (comp (ref "C511")
      (value "10u/10V")
      (footprint "eagle-import:0805-CAP")
      (fields (field (name "PARTNO") "CC0805ZKY5V6BB106"))
      (libsource (lib "eagle-import") (part "CAP0805"))
    )
    (comp (ref "C512")
      (value "2u2")
      (footprint "eagle-import:0603-CAP")
      (fields (field (name "PARTNO") "C1608X6S1C225K080AC"))
      (libsource (lib "eagle-import") (part "CAP0603"))
    )
    (comp (ref "C513")
      (value "2u2")
      (footprint "eagle-import:0603-CAP")
      (fields (field (name "PARTNO") "C1608X6S1C225K080AC"))
      (libsource (lib "eagle-import") (part "CAP0603"))
    )
    (comp (ref "C514")
      (value "0u1")
      (footprint "eagle-import:0402-CAP")
      (fields (field (name "PARTNO") "CC0402ZRY5V7BB104"))
      (libsource (lib "eagle-import") (part "CAP0402"))
    )
    (comp (ref "C515")
      (value "0u01")
      (footprint "eagle-import:0603-CAP")
      (fields (field (name "PARTNO") "06033C103JAT2A"))
      (libsource (lib "eagle-import") (part "CAP0603"))
    )
    (comp (ref "U501")
      (value "L3GD20")
      (footprint "eagle-import:L3G4200DH-MAN")
      (libsource (lib "eagle-import") (part "L3G4200DH-LL"))
    )
    (comp (ref "U502")
      (value "L3GD20H")
      (footprint "eagle-import:LGA-16L")
      (libsource (lib "eagle-import") (part "L3GD20H"))
    )
    (comp (ref "U504")
      (value "LSM303D")
      (footprint "eagle-import:LGA-16L")
      (libsource (lib "eagle-import") (part "LSM303D"))
    )
    (comp (ref "U505")
      (value "MPU-6000")
      (footprint "eagle-import:QFN-24")
      (libsource (lib "eagle-import") (part "MPU-6000"))
    )
    (comp (ref "U506")
      (value "MS5611-01BA")
      (footprint "eagle-import:MS5611-01BA")
      (libsource (lib "eagle-import") (part "MS5611-01BA"))
    )
    (comp (ref "X503")
      (value "0512811094")
      (footprint "eagle-import:51281-1094")
      (fields (field (name "BOM") "EXCLUDE") (field (name "PARTNO") "0781191109"))
      (libsource (lib "eagle-import") (part "CONN_FPC_10RA"))
    )
    (comp (ref "C701")
      (value "0u1")
      (footprint "eagle-import:0402-CAP")
      (fields (field (name "PARTNO") "CC0402ZRY5V7BB104"))
      (libsource (lib "eagle-import") (part "CAP0402"))
    )
    (comp (ref "C702")
      (value "1u")
      (footprint "eagle-import:0603-CAP")
      (fields (field (name "PARTNO") "CC0603ZRY5V7BB105"))
      (libsource (lib "eagle-import") (part "CAP0603"))
    )
    (comp (ref "C703")
      (value "5n6")
      (footprint "eagle-import:0402-CAP")
      (fields (field (name "PARTNO") "C0402C562K5RACTU"))
      (libsource (lib "eagle-import") (part "CAP0402"))
    )
    (comp (ref "C704")
      (value "0u47")
      (footprint "eagle-import:0402-CAP")
      (fields (field (name "PARTNO") "C1005X5R1C474K050BC"))
      (libsource (lib "eagle-import") (part "CAP0402"))
    )
    (comp (ref "D701")
      (value "PESD0402-140")
      (footprint "eagle-import:0402-TVS")
      (libsource (lib "eagle-import") (part "DIODE-TVS"))
    )
    (comp (ref "J701")
      (value "DF13C-2P-1.25V")
      (footprint "eagle-import:DF13C-2P-1.25V")
      (fields (field (name "PARTNO") "DF13C-2P-1.25V(20)"))
      (libsource (lib "eagle-import") (part "DF13-2P-1.25V"))
    )
    (comp (ref "J702")
      (value "DF13C-3P-1.25V")
      (footprint "eagle-import:DF13C-3P-1.25V")
      (fields (field (name "PARTNO") "DF13C-3P-1.25V(20)"))
      (libsource (lib "eagle-import") (part "DF13-3P-1.25V"))
    )
    (comp (ref "L701")
      (value "47uH")
      (footprint "eagle-import:0805-IND")
      (fields (field (name "PARTNO") "MLZ2012M470W"))
      (libsource (lib "eagle-import") (part "INDUCTOR0805"))
    )
    (comp (ref "LED701")
      (value "AMBER")
      (footprint "eagle-import:0603-LED")
      (fields (field (name "PARTNO") "APTD1608SECK"))
      (libsource (lib "eagle-import") (part "LED0603"))
    )
    (comp (ref "LED702")
      (value "GREEN")
      (footprint "eagle-import:0603-LED")
      (fields (field (name "PARTNO") "APTD1608CGCK"))
      (libsource (lib "eagle-import") (part "LED0603"))
    )
    (comp (ref "LED703")
      (value "AMBER")
      (footprint "eagle-import:0603-LED")
      (fields (field (name "PARTNO") "APTD1608SECK"))
      (libsource (lib "eagle-import") (part "LED0603"))
    )
    (comp (ref "LED704")
      (value "GREEN")
      (footprint "eagle-import:0603-LED")
      (fields (field (name "PARTNO") "APTD1608CGCK"))
      (libsource (lib "eagle-import") (part "LED0603"))
    )
    (comp (ref "LED705")
      (value "BLUE")
      (footprint "eagle-import:0603-LED")
      (fields (field (name "PARTNO") "APTD1608QBC/D"))
      (libsource (lib "eagle-import") (part "LED0603"))
    )
    (comp (ref "R701")
      (value "9K09")
      (footprint "eagle-import:0402-RES")
      (fields (field (name "PARTNO") "RMCF0402FT9K09"))
      (libsource (lib "eagle-import") (part "RESISTOR0402-RES"))
    )
    (comp (ref "R702")
      (value "10K")
      (footprint "eagle-import:0402-RES")
      (fields (field (name "PARTNO") "RC0402FR-0710KL"))
      (libsource (lib "eagle-import") (part "RESISTOR0402-RES"))
    )
    (comp (ref "R703")
      (value "100K")
      (footprint "eagle-import:0402-RES")
      (fields (field (name "PARTNO") "RC0402FR-07100KL"))
      (libsource (lib "eagle-import") (part "RESISTOR0402-RES"))
    )
    (comp (ref "R704")
      (value "10K")
      (footprint "eagle-import:0402-RES")
      (fields (field (name "PARTNO") "RC0402FR-0710KL"))
      (libsource (lib "eagle-import") (part "RESISTOR0402-RES"))
    )
    (comp (ref "R705")
      (value "453K")
      (footprint "eagle-import:0402-RES")
      (fields (field (name "PARTNO") "RMCF0402FT453K"))
      (libsource (lib "eagle-import") (part "RESISTOR0402-RES"))
    )
    (comp (ref "R706")
      (value "16K5")
      (footprint "eagle-import:0402-RES")
      (fields (field (name "PARTNO") "RMCF0402FT16K5"))
      (libsource (lib "eagle-import") (part "RESISTOR0402-RES"))
    )
    (comp (ref "R707")
      (value "220R")
      (footprint "eagle-import:0402-RES")
      (fields (field (name "PARTNO") "RC0402FR-07220RL"))
      (libsource (lib "eagle-import") (part "RESISTOR0402-RES"))
    )
    (comp (ref "R708")
      (value "220R")
      (footprint "eagle-import:0402-RES")
      (fields (field (name "PARTNO") "RC0402FR-07220RL"))
      (libsource (lib "eagle-import") (part "RESISTOR0402-RES"))
    )
    (comp (ref "R709")
      (value "220R")
      (footprint "eagle-import:0402-RES")
      (fields (field (name "PARTNO") "RC0402FR-07220RL"))
      (libsource (lib "eagle-import") (part "RESISTOR0402-RES"))
    )
    (comp (ref "R710")
      (value "68R")
      (footprint "eagle-import:0402-RES")
      (fields (field (name "PARTNO") "ERJ-2GEJ680X"))
      (libsource (lib "eagle-import") (part "RESISTOR0402-RES"))
    )
    (comp (ref "R711")
      (value "220R")
      (footprint "eagle-import:0402-RES")
      (fields (field (name "PARTNO") "RC0402FR-07220RL"))
      (libsource (lib "eagle-import") (part "RESISTOR0402-RES"))
    )
    (comp (ref "R712")
      (value "220R")
      (footprint "eagle-import:0402-RES")
      (fields (field (name "PARTNO") "RC0402FR-07220RL"))
      (libsource (lib "eagle-import") (part "RESISTOR0402-RES"))
    )
    (comp (ref "R713")
      (value "1K5")
      (footprint "eagle-import:0402-RES")
      (fields (field (name "PARTNO") "RC0402FR-071K5L"))
      (libsource (lib "eagle-import") (part "RESISTOR0402-RES"))
    )
    (comp (ref "R735")
      (value "220R")
      (footprint "eagle-import:0402-RES")
      (fields (field (name "PARTNO") "RC0402FR-07220RL"))
      (libsource (lib "eagle-import") (part "RESISTOR0402-RES"))
    )
    (comp (ref "R736")
      (value "220R")
      (footprint "eagle-import:0402-RES")
      (fields (field (name "PARTNO") "RC0402FR-07220RL"))
      (libsource (lib "eagle-import") (part "RESISTOR0402-RES"))
    )
    (comp (ref "U701")
      (value "TCA62724FMG")
      (footprint "eagle-import:SON10")
      (libsource (lib "eagle-import") (part "TCA62724FMG"))
    )
    (comp (ref "U702")
      (value "LT3469")
      (footprint "eagle-import:SOT23-8")
      (fields (field (name "PARTNO") "LT3469ETS8"))
      (libsource (lib "eagle-import") (part "LT3469"))
    )
    (comp (ref "U703")
      (value "LRTB GFTG-T7AW-1+V7A7-29+R5T9-49-L")
      (footprint "eagle-import:6-PLCC")
      (fields (field (name "PARTNO") "LRTB GFTG-T7AW-1+V7A7-29+R5T9-49-L"))
      (libsource (lib "eagle-import") (part "RGB-LED6-PLCC"))
    )
  )
  (nets
    (net (code "1") (name "ACCEL_DRDY") (class "Default")
      (node (ref "U101") (pin "90") (pinfunction "PB4_90") (pintype "bidirectional"))
      (node (ref "U504") (pin "11") (pinfunction "INT1_11") (pintype "bidirectional"))
      (node (ref "X503") (pin "3") (pinfunction "S_3") (pintype "passive"))
    )
    (net (code "2") (name "ALARM") (class "Default")
      (node (ref "R701") (pin "P$2") (pinfunction "2_P$2") (pintype "passive"))
      (node (ref "U101") (pin "77") (pinfunction "PA15_77") (pintype "bidirectional"))
    )
    (net (code "3") (name "BATT_CURRENT_SENS") (class "Default")
      (node (ref "R1101") (pin "P$1") (pinfunction "1_P$1") (pintype "passive"))
      (node (ref "U101") (pin "26") (pinfunction "PA3_26") (pintype "bidirectional"))
    )
    (net (code "4") (name "BATT_VOLTAGE_SENS") (class "Default")
      (node (ref "R1102") (pin "P$1") (pinfunction "1_P$1") (pintype "passive"))
      (node (ref "U101") (pin "25") (pinfunction "PA2_25") (pintype "bidirectional"))
    )
    (net (code "5") (name "CAN1_RX") (class "Default")
      (node (ref "U101") (pin "81") (pinfunction "PD0_81") (pintype "bidirectional"))
      (node (ref "U401") (pin "4") (pinfunction "DOUT_4") (pintype "output"))
    )
    (net (code "6") (name "CAN1_TX") (class "Default")
      (node (ref "U101") (pin "82") (pinfunction "PD1_82") (pintype "bidirectional"))
      (node (ref "U401") (pin "1") (pinfunction "DIN_1") (pintype "input"))
    )
    (net (code "7") (name "CAN2_RX") (class "Default")
      (node (ref "R216") (pin "P$1") (pinfunction "1_P$1") (pintype "passive"))
      (node (ref "U101") (pin "51") (pinfunction "PB12_51") (pintype "bidirectional"))
    )
    (net (code "8") (name "CAN2_TX") (class "Default")
      (node (ref "R215") (pin "P$1") (pinfunction "1_P$1") (pintype "passive"))
      (node (ref "U101") (pin "92") (pinfunction "PB6_92") (pintype "bidirectional"))
    )
    (net (code "9") (name "CAN_H") (class "Default")
      (node (ref "CAN_H") (pin "P$1") (pinfunction "P$1_P$1") (pintype "passive"))
      (node (ref "J405") (pin "2") (pinfunction "2_2") (pintype "passive"))
      (node (ref "R409") (pin "P$1") (pinfunction "1_P$1") (pintype "passive"))
      (node (ref "U401") (pin "7") (pinfunction "CANH_7") (pintype "bidirectional"))
    )
    (net (code "10") (name "CAN_L") (class "Default")
      (node (ref "CAN_L") (pin "P$1") (pinfunction "P$1_P$1") (pintype "passive"))
      (node (ref "J405") (pin "3") (pinfunction "3_3") (pintype "passive"))
      (node (ref "R409") (pin "P$2") (pinfunction "2_P$2") (pintype "passive"))
      (node (ref "U401") (pin "6") (pinfunction "CANL_6") (pintype "bidirectional"))
    )
    (net (code "11") (name "FMU-BOOT0") (class "Default")
      (node (ref "FMU-BOOT1101") (pin "P$1") (pinfunction "P$1_P$1") (pintype "passive"))
      (node (ref "R611") (pin "P$2") (pinfunction "2_P$2") (pintype "passive"))
      (node (ref "U101") (pin "94") (pinfunction "BOOT0_94") (pintype "input"))
    )
    (net (code "12") (name "FMU-CH1") (class "Default")
      (node (ref "U101") (pin "45") (pinfunction "PE14_45") (pintype "bidirectional"))
      (node (ref "U901") (pin "7") (pinfunction "A6_7") (pintype "bidirectional"))
    )
    (net (code "13") (name "FMU-CH2") (class "Default")
      (node (ref "U101") (pin "44") (pinfunction "PE13_44") (pintype "bidirectional"))
      (node (ref "U901") (pin "6") (pinfunction "A5_6") (pintype "bidirectional"))
    )
    (net (code "14") (name "FMU-CH3") (class "Default")
      (node (ref "U101") (pin "42") (pinfunction "PE11_42") (pintype "bidirectional"))
      (node (ref "U901") (pin "5") (pinfunction "A4_5") (pintype "bidirectional"))
    )
    (net (code "15") (name "FMU-CH4") (class "Default")
      (node (ref "U101") (pin "40") (pinfunction "PE9_40") (pintype "bidirectional"))
      (node (ref "U901") (pin "4") (pinfunction "A3_4") (pintype "bidirectional"))
    )
    (net (code "16") (name "FMU-CH5") (class "Default")
      (node (ref "U101") (pin "60") (pinfunction "PD13_60") (pintype "bidirectional"))
      (node (ref "U901") (pin "3") (pinfunction "A2_3") (pintype "bidirectional"))
    )
    (net (code "17") (name "FMU-CH6") (class "Default")
      (node (ref "U101") (pin "61") (pinfunction "PD14_61") (pintype "bidirectional"))
      (node (ref "U901") (pin "1") (pinfunction "A1_1") (pintype "bidirectional"))
    )
    (net (code "18") (name "FMU-I2C1_SCL") (class "Default")
      (node (ref "R401") (pin "P$1") (pinfunction "1_P$1") (pintype "passive"))
      (node (ref "R404") (pin "P$1") (pinfunction "1_P$1") (pintype "passive"))
      (node (ref "U101") (pin "95") (pinfunction "PB8_95") (pintype "bidirectional"))
    )
    (net (code "19") (name "FMU-I2C1_SDA") (class "Default")
      (node (ref "R402") (pin "P$1") (pinfunction "1_P$1") (pintype "passive"))
      (node (ref "R405") (pin "P$1") (pinfunction "1_P$1") (pintype "passive"))
      (node (ref "U101") (pin "96") (pinfunction "PB9_96") (pintype "bidirectional"))
    )
    (net (code "20") (name "FMU-I2C2_SCL") (class "Default")
      (node (ref "R306") (pin "P$1") (pinfunction "1_P$1") (pintype "passive"))
      (node (ref "U101") (pin "47") (pinfunction "PB10_47") (pintype "bidirectional"))
      (node (ref "U701") (pin "3") (pinfunction "SCL_3") (pintype "bidirectional"))
    )
    (net (code "21") (name "FMU-I2C2_SDA") (class "Default")
      (node (ref "R307") (pin "P$1") (pinfunction "1_P$1") (pintype "passive"))
      (node (ref "U101") (pin "48") (pinfunction "PB11_48") (pintype "bidirectional"))
      (node (ref "U701") (pin "2") (pinfunction "SDA_2") (pintype "bidirectional"))
    )
    (net (code "22") (name "FMU-SWCLK") (class "Default")
      (node (ref "JX301") (pin "4") (pinfunction "S_4") (pintype "passive"))
      (node (ref "U101") (pin "76") (pinfunction "PA14_76") (pintype "bidirectional"))
    )
    (net (code "23") (name "FMU-SWDIO") (class "Default")
      (node (ref "JX301") (pin "2") (pinfunction "S_2") (pintype "passive"))
      (node (ref "U101") (pin "72") (pinfunction "PA13_72") (pintype "bidirectional"))
    )
    (net (code "24") (name "FMU-SWO") (class "Default")
      (node (ref "JX301") (pin "6") (pinfunction "S_6") (pintype "passive"))
      (node (ref "U101") (pin "89") (pinfunction "PB3_89") (pintype "bidirectional"))
    )
    (net (code "25") (name "FMU-UART4_RX") (class "Default")
      (node (ref "U101") (pin "24") (pinfunction "PA1_24") (pintype "bidirectional"))
      (node (ref "U202") (pin "8") (pinfunction "A7_8") (pintype "bidirectional"))
    )
    (net (code "26") (name "FMU-UART4_TX") (class "Default")
      (node (ref "U101") (pin "23") (pinfunction "PA0_23") (pintype "bidirectional"))
      (node (ref "U202") (pin "9") (pinfunction "A8_9") (pintype "bidirectional"))
    )
    (net (code "27") (name "FMU-UART7_RX") (class "Default")
      (node (ref "U101") (pin "38") (pinfunction "PE7_38") (pintype "bidirectional"))
      (node (ref "U202") (pin "4") (pinfunction "A3_4") (pintype "bidirectional"))
    )
    (net (code "28") (name "FMU-UART7_TX") (class "Default")
      (node (ref "U101") (pin "39") (pinfunction "PE8_39") (pintype "bidirectional"))
      (node (ref "U202") (pin "5") (pinfunction "A4_5") (pintype "bidirectional"))
    )
    (net (code "29") (name "FMU-UART8_RX") (class "Default")
      (node (ref "U101") (pin "97") (pinfunction "PE0_97") (pintype "bidirectional"))
      (node (ref "U202") (pin "6") (pinfunction "A5_6") (pintype "bidirectional"))
    )
    (net (code "30") (name "FMU-UART8_TX") (class "Default")
      (node (ref "U101") (pin "98") (pinfunction "PE1_98") (pintype "bidirectional"))
      (node (ref "U202") (pin "7") (pinfunction "A6_7") (pintype "bidirectional"))
    )
    (net (code "31") (name "FMU-USART2_CTS") (class "Default")
      (node (ref "U101") (pin "84") (pinfunction "PD3_84") (pintype "bidirectional"))
      (node (ref "U201") (pin "9") (pinfunction "A8_9") (pintype "bidirectional"))
    )
    (net (code "32") (name "FMU-USART2_RTS") (class "Default")
      (node (ref "U101") (pin "85") (pinfunction "PD4_85") (pintype "bidirectional"))
      (node (ref "U201") (pin "8") (pinfunction "A7_8") (pintype "bidirectional"))
    )
    (net (code "33") (name "FMU-USART2_RX") (class "Default")
      (node (ref "U101") (pin "87") (pinfunction "PD6_87") (pintype "bidirectional"))
      (node (ref "U201") (pin "6") (pinfunction "A5_6") (pintype "bidirectional"))
    )
    (net (code "34") (name "FMU-USART2_TX") (class "Default")
      (node (ref "U101") (pin "86") (pinfunction "PD5_86") (pintype "bidirectional"))
      (node (ref "U201") (pin "7") (pinfunction "A6_7") (pintype "bidirectional"))
    )
    (net (code "35") (name "FMU-USART3_CTS") (class "Default")
      (node (ref "U101") (pin "58") (pinfunction "PD11_58") (pintype "bidirectional"))
      (node (ref "U201") (pin "3") (pinfunction "A2_3") (pintype "bidirectional"))
    )
    (net (code "36") (name "FMU-USART3_RTS") (class "Default")
      (node (ref "U101") (pin "59") (pinfunction "PD12_59") (pintype "bidirectional"))
      (node (ref "U201") (pin "1") (pinfunction "A1_1") (pintype "bidirectional"))
    )
    (net (code "37") (name "FMU-USART3_RX") (class "Default")
      (node (ref "U101") (pin "56") (pinfunction "PD9_56") (pintype "bidirectional"))
      (node (ref "U201") (pin "4") (pinfunction "A3_4") (pintype "bidirectional"))
    )
    (net (code "38") (name "FMU-USART3_TX") (class "Default")
      (node (ref "U101") (pin "55") (pinfunction "PD8_55") (pintype "bidirectional"))
      (node (ref "U201") (pin "5") (pinfunction "A4_5") (pintype "bidirectional"))
    )
    (net (code "39") (name "FMU-VDD_3V3") (class "Default")
      (node (ref "C101") (pin "P$1") (pinfunction "1_P$1") (pintype "passive"))
      (node (ref "C201") (pin "P$1") (pinfunction "1_P$1") (pintype "passive"))
      (node (ref "C202") (pin "P$1") (pinfunction "1_P$1") (pintype "passive"))
      (node (ref "C402") (pin "P$1") (pinfunction "1_P$1") (pintype "passive"))
      (node (ref "C603") (pin "P$1") (pinfunction "1_P$1") (pintype "passive"))
      (node (ref "C604") (pin "P$1") (pinfunction "1_P$1") (pintype "passive"))
      (node (ref "C606") (pin "P$1") (pinfunction "1_P$1") (pintype "passive"))
      (node (ref "C607") (pin "P$1") (pinfunction "1_P$1") (pintype "passive"))
      (node (ref "C608") (pin "P$1") (pinfunction "1_P$1") (pintype "passive"))
      (node (ref "C610") (pin "P$1") (pinfunction "1_P$1") (pintype "passive"))
      (node (ref "C612") (pin "P$1") (pinfunction "1_P$1") (pintype "passive"))
      (node (ref "C616") (pin "P$1") (pinfunction "1_P$1") (pintype "passive"))
      (node (ref "C701") (pin "P$1") (pinfunction "1_P$1") (pintype "passive"))
      (node (ref "C902") (pin "P$1") (pinfunction "1_P$1") (pintype "passive"))
      (node (ref "D602") (pin "A") (pinfunction "A_A") (pintype "passive"))
      (node (ref "JX301") (pin "1") (pinfunction "S_1") (pintype "passive"))
      (node (ref "R301") (pin "P$2") (pinfunction "2_P$2") (pintype "passive"))
      (node (ref "R302") (pin "P$2") (pinfunction "2_P$2") (pintype "passive"))
      (node (ref "R303") (pin "P$2") (pinfunction "2_P$2") (pintype "passive"))
      (node (ref "R304") (pin "P$2") (pinfunction "2_P$2") (pintype "passive"))
      (node (ref "R305") (pin "P$2") (pinfunction "2_P$2") (pintype "passive"))
      (node (ref "R306") (pin "P$2") (pinfunction "2_P$2") (pintype "passive"))
      (node (ref "R307") (pin "P$2") (pinfunction "2_P$2") (pintype "passive"))
      (node (ref "R401") (pin "P$2") (pinfunction "2_P$2") (pintype "passive"))
      (node (ref "R402") (pin "P$2") (pinfunction "2_P$2") (pintype "passive"))
      (node (ref "R602") (pin "P$2") (pinfunction "2_P$2") (pintype "passive"))
      (node (ref "R604") (pin "P$2") (pinfunction "2_P$2") (pintype "passive"))
      (node (ref "U101") (pin "100") (pinfunction "VDD_100") (pintype "power_in"))
      (node (ref "U101") (pin "11") (pinfunction "VDD_11") (pintype "power_in"))
      (node (ref "U101") (pin "19") (pinfunction "VDD_19") (pintype "power_in"))
      (node (ref "U101") (pin "21") (pinfunction "VREF+_21") (pintype "input"))
      (node (ref "U101") (pin "22") (pinfunction "VDDA_22") (pintype "power_in"))
      (node (ref "U101") (pin "28") (pinfunction "VDD_28") (pintype "power_in"))
      (node (ref "U101") (pin "50") (pinfunction "VDD_50") (pintype "power_in"))
      (node (ref "U101") (pin "75") (pinfunction "VDD_75") (pintype "power_in"))
      (node (ref "U102") (pin "3") (pinfunction "~{W}_3") (pintype "bidirectional"))
      (node (ref "U102") (pin "7") (pinfunction "~{HOLD}_7") (pintype "bidirectional"))
      (node (ref "U102") (pin "8") (pinfunction "VDD_8") (pintype "bidirectional"))
      (node (ref "U201") (pin "10") (pinfunction "OE_10") (pintype "input"))
      (node (ref "U201") (pin "19") (pinfunction "VCCB_19") (pintype "input"))
      (node (ref "U201") (pin "2") (pinfunction "VCCA_2") (pintype "input"))
      (node (ref "U202") (pin "10") (pinfunction "OE_10") (pintype "input"))
      (node (ref "U202") (pin "19") (pinfunction "VCCB_19") (pintype "input"))
      (node (ref "U202") (pin "2") (pinfunction "VCCA_2") (pintype "input"))
      (node (ref "U301") (pin "4") (pinfunction "VCC_4") (pintype "passive"))
      (node (ref "U401") (pin "3") (pinfunction "VCC_3") (pintype "input"))
      (node (ref "U603") (pin "7") (pinfunction "VOUT2_7") (pintype "bidirectional"))
      (node (ref "U701") (pin "1") (pinfunction "~{SHDN}_1") (pintype "input"))
      (node (ref "U701") (pin "10") (pinfunction "VIN_10") (pintype "power_in"))
      (node (ref "U901") (pin "10") (pinfunction "OE_10") (pintype "input"))
      (node (ref "U901") (pin "19") (pinfunction "VCCB_19") (pintype "input"))
      (node (ref "U901") (pin "2") (pinfunction "VCCA_2") (pintype "input"))
      (node (ref "VDD_3V1101") (pin "P$1") (pinfunction "P$1_P$1") (pintype "passive"))
    )
    (net (code "40") (name "FMU-~{RESET}") (class "Default")
      (node (ref "C609") (pin "P$2") (pinfunction "2_P$2") (pintype "passive"))
      (node (ref "R635") (pin "P$1") (pinfunction "1_P$1") (pintype "passive"))
      (node (ref "S601") (pin "A1") (pinfunction "1_A1") (pintype "passive"))
      (node (ref "U101") (pin "14") (pinfunction "NRST_14") (pintype "input"))
      (node (ref "U603") (pin "3") (pinfunction "POR2_3") (pintype "bidirectional"))
      (node (ref "U701") (pin "4") (pinfunction "~{RESET}_4") (pintype "input"))
    )
    (net (code "41") (name "FMU_AUX_ADC1") (class "Default")
      (node (ref "R408") (pin "P$1") (pinfunction "1_P$1") (pintype "passive"))
      (node (ref "U101") (pin "18") (pinfunction "PC3_18") (pintype "bidirectional"))
    )
    (net (code "42") (name "FMU_AUX_ADC2") (class "Default")
      (node (ref "R407") (pin "P$1") (pinfunction "1_P$1") (pintype "passive"))
      (node (ref "U101") (pin "33") (pinfunction "PC4_33") (pintype "bidirectional"))
    )
    (net (code "43") (name "FRAM_MISO") (class "Default")
      (node (ref "U101") (pin "53") (pinfunction "PB14_53") (pintype "bidirectional"))
      (node (ref "U102") (pin "2") (pinfunction "Q_2") (pintype "bidirectional"))
    )
    (net (code "44") (name "FRAM_MOSI") (class "Default")
      (node (ref "U101") (pin "54") (pinfunction "PB15_54") (pintype "bidirectional"))
      (node (ref "U102") (pin "5") (pinfunction "D_5") (pintype "bidirectional"))
    )
    (net (code "45") (name "FRAM_SCK") (class "Default")
      (node (ref "U101") (pin "52") (pinfunction "PB13_52") (pintype "bidirectional"))
      (node (ref "U102") (pin "6") (pinfunction "C_6") (pintype "bidirectional"))
    )
    (net (code "46") (name "GND") (class "Default")
      (node (ref "B601") (pin "2") (pinfunction "NEG_2") (pintype "bidirectional"))
      (node (ref "C1001") (pin "P$2") (pinfunction "2_P$2") (pintype "passive"))
      (node (ref "C1002") (pin "P$2") (pinfunction "2_P$2") (pintype "passive"))
      (node (ref "C1003") (pin "P$2") (pinfunction "2_P$2") (pintype "passive"))
      (node (ref "C1004") (pin "P$2") (pinfunction "2_P$2") (pintype "passive"))
      (node (ref "C1005") (pin "P$2") (pinfunction "2_P$2") (pintype "passive"))
      (node (ref "C1008") (pin "P$2") (pinfunction "2_P$2") (pintype "passive"))
      (node (ref "C101") (pin "P$2") (pinfunction "2_P$2") (pintype "passive"))
      (node (ref "C102") (pin "P$2") (pinfunction "2_P$2") (pintype "passive"))
      (node (ref "C103") (pin "P$1") (pinfunction "1_P$1") (pintype "passive"))
      (node (ref "C1101") (pin "P$2") (pinfunction "2_P$2") (pintype "passive"))
      (node (ref "C1102") (pin "P$2") (pinfunction "2_P$2") (pintype "passive"))
      (node (ref "C1103") (pin "P$2") (pinfunction "2_P$2") (pintype "passive"))
      (node (ref "C1104") (pin "P$2") (pinfunction "2_P$2") (pintype "passive"))
      (node (ref "C1105") (pin "P$2") (pinfunction "2_P$2") (pintype "passive"))
      (node (ref "C1106") (pin "P$2") (pinfunction "2_P$2") (pintype "passive"))
      (node (ref "C1107") (pin "P$2") (pinfunction "2_P$2") (pintype "passive"))
      (node (ref "C1108") (pin "P$2") (pinfunction "2_P$2") (pintype "passive"))
      (node (ref "C1109") (pin "P$2") (pinfunction "2_P$2") (pintype "passive"))
      (node (ref "C1110") (pin "P$2") (pinfunction "2_P$2") (pintype "passive"))
      (node (ref "C201") (pin "P$2") (pinfunction "2_P$2") (pintype "passive"))
      (node (ref "C202") (pin "P$2") (pinfunction "2_P$2") (pintype "passive"))
      (node (ref "C401") (pin "P$2") (pinfunction "2_P$2") (pintype "passive"))
      (node (ref "C402") (pin "P$2") (pinfunction "2_P$2") (pintype "passive"))
      (node (ref "C501") (pin "P$2") (pinfunction "2_P$2") (pintype "passive"))
      (node (ref "C502") (pin "P$2") (pinfunction "2_P$2") (pintype "passive"))
      (node (ref "C503") (pin "P$2") (pinfunction "2_P$2") (pintype "passive"))
      (node (ref "C504") (pin "P$2") (pinfunction "2_P$2") (pintype "passive"))
      (node (ref "C505") (pin "P$2") (pinfunction "2_P$2") (pintype "passive"))
      (node (ref "C506") (pin "P$2") (pinfunction "2_P$2") (pintype "passive"))
      (node (ref "C507") (pin "P$2") (pinfunction "2_P$2") (pintype "passive"))
      (node (ref "C508") (pin "P$2") (pinfunction "2_P$2") (pintype "passive"))
      (node (ref "C509") (pin "P$2") (pinfunction "2_P$2") (pintype "passive"))
      (node (ref "C511") (pin "P$2") (pinfunction "2_P$2") (pintype "passive"))
      (node (ref "C512") (pin "P$2") (pinfunction "2_P$2") (pintype "passive"))
      (node (ref "C513") (pin "P$2") (pinfunction "2_P$2") (pintype "passive"))
      (node (ref "C514") (pin "P$2") (pinfunction "2_P$2") (pintype "passive"))
      (node (ref "C515") (pin "P$2") (pinfunction "2_P$2") (pintype "passive"))
      (node (ref "C601") (pin "P$2") (pinfunction "2_P$2") (pintype "passive"))
      (node (ref "C602") (pin "P$1") (pinfunction "1_P$1") (pintype "passive"))
      (node (ref "C603") (pin "P$2") (pinfunction "2_P$2") (pintype "passive"))
      (node (ref "C604") (pin "P$2") (pinfunction "2_P$2") (pintype "passive"))
      (node (ref "C605") (pin "P$2") (pinfunction "2_P$2") (pintype "passive"))
      (node (ref "C606") (pin "P$2") (pinfunction "2_P$2") (pintype "passive"))
      (node (ref "C607") (pin "P$2") (pinfunction "2_P$2") (pintype "passive"))
      (node (ref "C608") (pin "P$2") (pinfunction "2_P$2") (pintype "passive"))
      (node (ref "C609") (pin "P$1") (pinfunction "1_P$1") (pintype "passive"))
      (node (ref "C610") (pin "P$2") (pinfunction "2_P$2") (pintype "passive"))
      (node (ref "C611") (pin "P$2") (pinfunction "2_P$2") (pintype "passive"))
      (node (ref "C612") (pin "P$2") (pinfunction "2_P$2") (pintype "passive"))
      (node (ref "C613") (pin "P$2") (pinfunction "2_P$2") (pintype "passive"))
      (node (ref "C614") (pin "P$2") (pinfunction "2_P$2") (pintype "passive"))
      (node (ref "C615") (pin "P$2") (pinfunction "2_P$2") (pintype "passive"))
      (node (ref "C616") (pin "P$2") (pinfunction "2_P$2") (pintype "passive"))
      (node (ref "C617") (pin "P$2") (pinfunction "2_P$2") (pintype "passive"))
      (node (ref "C618") (pin "P$2") (pinfunction "2_P$2") (pintype "passive"))
      (node (ref "C701") (pin "P$2") (pinfunction "2_P$2") (pintype "passive"))
      (node (ref "C702") (pin "P$2") (pinfunction "2_P$2") (pintype "passive"))
      (node (ref "C703") (pin "P$2") (pinfunction "2_P$2") (pintype "passive"))
      (node (ref "C704") (pin "P$2") (pinfunction "2_P$2") (pintype "passive"))
      (node (ref "C801") (pin "P$1") (pinfunction "1_P$1") (pintype "passive"))
      (node (ref "C802") (pin "P$2") (pinfunction "2_P$2") (pintype "passive"))
      (node (ref "C803") (pin "P$2") (pinfunction "2_P$2") (pintype "passive"))
      (node (ref "C804") (pin "P$2") (pinfunction "2_P$2") (pintype "passive"))
      (node (ref "C805") (pin "P$2") (pinfunction "2_P$2") (pintype "passive"))
      (node (ref "C806") (pin "P$1") (pinfunction "1_P$1") (pintype "passive"))
      (node (ref "C901") (pin "P$2") (pinfunction "2_P$2") (pintype "passive"))
      (node (ref "C902") (pin "P$2") (pinfunction "2_P$2") (pintype "passive"))
      (node (ref "C903") (pin "P$2") (pinfunction "2_P$2") (pintype "passive"))
      (node (ref "D201") (pin "A") (pinfunction "A_A") (pintype "passive"))
      (node (ref "D202") (pin "A") (pinfunction "A_A") (pintype "passive"))
      (node (ref "D203") (pin "A") (pinfunction "A_A") (pintype "passive"))
      (node (ref "D401") (pin "A") (pinfunction "A_A") (pintype "passive"))
      (node (ref "D402") (pin "A") (pinfunction "A_A") (pintype "passive"))
      (node (ref "D403") (pin "A") (pinfunction "A_A") (pintype "passive"))
      (node (ref "D404") (pin "A") (pinfunction "A_A") (pintype "passive"))
      (node (ref "D701") (pin "A") (pinfunction "A_A") (pintype "passive"))
      (node (ref "D801") (pin "A") (pinfunction "A_A") (pintype "passive"))
      (node (ref "D901") (pin "A") (pinfunction "A_A") (pintype "passive"))
      (node (ref "D902") (pin "A") (pinfunction "A_A") (pintype "passive"))
      (node (ref "D903") (pin "A") (pinfunction "A_A") (pintype "passive"))
      (node (ref "GND") (pin "P$1") (pinfunction "P$1_P$1") (pintype "passive"))
      (node (ref "GND.") (pin "P$1") (pinfunction "P$1_P$1") (pintype "passive"))
      (node (ref "J201") (pin "6") (pinfunction "6_6") (pintype "passive"))
      (node (ref "J202") (pin "6") (pinfunction "6_6") (pintype "passive"))
      (node (ref "J203") (pin "6") (pinfunction "6_6") (pintype "passive"))
      (node (ref "J204") (pin "6") (pinfunction "6_6") (pintype "passive"))
      (node (ref "J301") (pin "GND") (pinfunction "5_GND") (pintype "power_in"))
      (node (ref "J301") (pin "GND1") (pinfunction "GND1_GND1") (pintype "bidirectional"))
      (node (ref "J301") (pin "GND2") (pinfunction "GND2_GND2") (pintype "bidirectional"))
      (node (ref "J301") (pin "GND3") (pinfunction "GND3_GND3") (pintype "bidirectional"))
      (node (ref "J301") (pin "GND4") (pinfunction "GND4_GND4") (pintype "bidirectional"))
      (node (ref "J302") (pin "4") (pinfunction "4_4") (pintype "passive"))
      (node (ref "J401") (pin "4") (pinfunction "4_4") (pintype "passive"))
      (node (ref "J402") (pin "3") (pinfunction "3_3") (pintype "passive"))
      (node (ref "J403") (pin "7") (pinfunction "7_7") (pintype "passive"))
      (node (ref "J404") (pin "3") (pinfunction "3_3") (pintype "passive"))
      (node (ref "J404") (pin "5") (pinfunction "5_5") (pintype "passive"))
      (node (ref "J405") (pin "4") (pinfunction "4_4") (pintype "passive"))
      (node (ref "J601") (pin "5") (pinfunction "5_5") (pintype "passive"))
      (node (ref "J601") (pin "6") (pinfunction "6_6") (pintype "passive"))
      (node (ref "J701") (pin "2") (pinfunction "2_2") (pintype "passive"))
      (node (ref "J801") (pin "P$2") (pinfunction "P$2_P$2") (pintype "bidirectional"))
      (node (ref "J901") (pin "12") (pinfunction "S_12") (pintype "passive"))
      (node (ref "J901") (pin "15") (pinfunction "S_15") (pintype "passive"))
      (node (ref "J901") (pin "18") (pinfunction "S_18") (pintype "passive"))
      (node (ref "J901") (pin "21") (pinfunction "S_21") (pintype "passive"))
      (node (ref "J901") (pin "24") (pinfunction "S_24") (pintype "passive"))
      (node (ref "J901") (pin "27") (pinfunction "S_27") (pintype "passive"))
      (node (ref "J901") (pin "3") (pinfunction "S_3") (pintype "passive"))
      (node (ref "J901") (pin "30") (pinfunction "S_30") (pintype "passive"))
      (node (ref "J901") (pin "33") (pinfunction "S_33") (pintype "passive"))
      (node (ref "J901") (pin "36") (pinfunction "S_36") (pintype "passive"))
      (node (ref "J901") (pin "39") (pinfunction "S_39") (pintype "passive"))
      (node (ref "J901") (pin "42") (pinfunction "S_42") (pintype "passive"))
      (node (ref "J901") (pin "45") (pinfunction "S_45") (pintype "passive"))
      (node (ref "J901") (pin "48") (pinfunction "S_48") (pintype "passive"))
      (node (ref "J901") (pin "6") (pinfunction "S_6") (pintype "passive"))
      (node (ref "J901") (pin "9") (pinfunction "S_9") (pintype "passive"))
      (node (ref "JX301") (pin "3") (pinfunction "S_3") (pintype "passive"))
      (node (ref "JX301") (pin "5") (pinfunction "S_5") (pintype "passive"))
      (node (ref "JX301") (pin "9") (pinfunction "S_9") (pintype "passive"))
      (node (ref "JX801") (pin "3") (pinfunction "GND_3") (pintype "bidirectional"))
      (node (ref "JX802") (pin "3") (pinfunction "S_3") (pintype "passive"))
      (node (ref "JX802") (pin "5") (pinfunction "S_5") (pintype "passive"))
      (node (ref "JX802") (pin "9") (pinfunction "S_9") (pintype "passive"))
      (node (ref "L1101") (pin "P$3") (pinfunction "P$3_P$3") (pintype "bidirectional"))
      (node (ref "L1101") (pin "P$4") (pinfunction "P$3_P$4") (pintype "bidirectional"))
      (node (ref "L1101") (pin "P$5") (pinfunction "P$3_P$5") (pintype "bidirectional"))
      (node (ref "L1102") (pin "P$3") (pinfunction "P$3_P$3") (pintype "bidirectional"))
      (node (ref "L1102") (pin "P$4") (pinfunction "P$3_P$4") (pintype "bidirectional"))
      (node (ref "L1102") (pin "P$5") (pinfunction "P$3_P$5") (pintype "bidirectional"))
      (node (ref "L201") (pin "P$3") (pinfunction "P$3_P$3") (pintype "bidirectional"))
      (node (ref "L201") (pin "P$4") (pinfunction "P$3_P$4") (pintype "bidirectional"))
      (node (ref "L201") (pin "P$5") (pinfunction "P$3_P$5") (pintype "bidirectional"))
      (node (ref "L202") (pin "P$3") (pinfunction "P$3_P$3") (pintype "bidirectional"))
      (node (ref "L202") (pin "P$4") (pinfunction "P$3_P$4") (pintype "bidirectional"))
      (node (ref "L202") (pin "P$5") (pinfunction "P$3_P$5") (pintype "bidirectional"))
      (node (ref "L203") (pin "P$3") (pinfunction "P$3_P$3") (pintype "bidirectional"))
      (node (ref "L203") (pin "P$4") (pinfunction "P$3_P$4") (pintype "bidirectional"))
      (node (ref "L203") (pin "P$5") (pinfunction "P$3_P$5") (pintype "bidirectional"))
      (node (ref "L401") (pin "P$3") (pinfunction "P$3_P$3") (pintype "bidirectional"))
      (node (ref "L401") (pin "P$4") (pinfunction "P$3_P$4") (pintype "bidirectional"))
      (node (ref "L401") (pin "P$5") (pinfunction "P$3_P$5") (pintype "bidirectional"))
      (node (ref "L402") (pin "P$3") (pinfunction "P$3_P$3") (pintype "bidirectional"))
      (node (ref "L402") (pin "P$4") (pinfunction "P$3_P$4") (pintype "bidirectional"))
      (node (ref "L402") (pin "P$5") (pinfunction "P$3_P$5") (pintype "bidirectional"))
      (node (ref "L403") (pin "P$3") (pinfunction "P$3_P$3") (pintype "bidirectional"))
      (node (ref "L403") (pin "P$4") (pinfunction "P$3_P$4") (pintype "bidirectional"))
      (node (ref "L403") (pin "P$5") (pinfunction "P$3_P$5") (pintype "bidirectional"))
      (node (ref "L404") (pin "P$3") (pinfunction "P$3_P$3") (pintype "bidirectional"))
      (node (ref "L404") (pin "P$4") (pinfunction "P$3_P$4") (pintype "bidirectional"))
      (node (ref "L404") (pin "P$5") (pinfunction "P$3_P$5") (pintype "bidirectional"))
      (node (ref "L603") (pin "P$3") (pinfunction "P$3_P$3") (pintype "bidirectional"))
      (node (ref "L603") (pin "P$4") (pinfunction "P$3_P$4") (pintype "bidirectional"))
      (node (ref "L603") (pin "P$5") (pinfunction "P$3_P$5") (pintype "bidirectional"))
      (node (ref "L901") (pin "P$3") (pinfunction "P$3_P$3") (pintype "bidirectional"))
      (node (ref "L901") (pin "P$4") (pinfunction "P$3_P$4") (pintype "bidirectional"))
      (node (ref "L901") (pin "P$5") (pinfunction "P$3_P$5") (pintype "bidirectional"))
      (node (ref "R1001") (pin "P$1") (pinfunction "1_P$1") (pintype "passive"))
      (node (ref "R1002") (pin "P$1") (pinfunction "1_P$1") (pintype "passive"))
      (node (ref "R102") (pin "P$2") (pinfunction "2_P$2") (pintype "passive"))
      (node (ref "R1103") (pin "P$2") (pinfunction "2_P$2") (pintype "passive"))
      (node (ref "R1104") (pin "P$2") (pinfunction "2_P$2") (pintype "passive"))
      (node (ref "R1107") (pin "P$2") (pinfunction "2_P$2") (pintype "passive"))
      (node (ref "R1111") (pin "P$2") (pinfunction "2_P$2") (pintype "passive"))
      (node (ref "R1114") (pin "P$2") (pinfunction "2_P$2") (pintype "passive"))
      (node (ref "R1115") (pin "P$1") (pinfunction "1_P$1") (pintype "passive"))
      (node (ref "R403") (pin "P$1") (pinfunction "1_P$1") (pintype "passive"))
      (node (ref "R610") (pin "P$2") (pinfunction "2_P$2") (pintype "passive"))
      (node (ref "R611") (pin "P$1") (pinfunction "1_P$1") (pintype "passive"))
      (node (ref "R615") (pin "P$2") (pinfunction "2_P$2") (pintype "passive"))
      (node (ref "R616") (pin "P$2") (pinfunction "2_P$2") (pintype "passive"))
      (node (ref "R617") (pin "P$2") (pinfunction "2_P$2") (pintype "passive"))
      (node (ref "R621") (pin "1") (pinfunction "1_1") (pintype "passive"))
      (node (ref "R702") (pin "P$2") (pinfunction "2_P$2") (pintype "passive"))
      (node (ref "R704") (pin "P$1") (pinfunction "1_P$1") (pintype "passive"))
      (node (ref "R706") (pin "P$2") (pinfunction "2_P$2") (pintype "passive"))
      (node (ref "R708") (pin "P$1") (pinfunction "1_P$1") (pintype "passive"))
      (node (ref "R711") (pin "P$1") (pinfunction "1_P$1") (pintype "passive"))
      (node (ref "R713") (pin "P$2") (pinfunction "2_P$2") (pintype "passive"))
      (node (ref "R801") (pin "P$2") (pinfunction "2_P$2") (pintype "passive"))
      (node (ref "R802") (pin "P$2") (pinfunction "2_P$2") (pintype "passive"))
      (node (ref "R919") (pin "P$1") (pinfunction "1_P$1") (pintype "passive"))
      (node (ref "S601") (pin "B3") (pinfunction "2_B3") (pintype "passive"))
      (node (ref "S801") (pin "B3") (pinfunction "2_B3") (pintype "passive"))
      (node (ref "U1001") (pin "2") (pinfunction "VSS_2") (pintype "bidirectional"))
      (node (ref "U1001") (pin "5") (pinfunction "~{CE}_5") (pintype "bidirectional"))
      (node (ref "U1001") (pin "6") (pinfunction "VBAT_6") (pintype "bidirectional"))
      (node (ref "U1001") (pin "GND") (pinfunction "VSS_GND") (pintype "bidirectional"))
      (node (ref "U1001") (pin "P$2") (pinfunction "VSS_P$2") (pintype "bidirectional"))
      (node (ref "U1001") (pin "P$3") (pinfunction "VSS_P$3") (pintype "bidirectional"))
      (node (ref "U1002") (pin "2") (pinfunction "GND_2") (pintype "bidirectional"))
      (node (ref "U1002") (pin "GND") (pinfunction "GND_GND") (pintype "bidirectional"))
      (node (ref "U101") (pin "10") (pinfunction "VSS_10") (pintype "power_in"))
      (node (ref "U101") (pin "20") (pinfunction "VSSA_20") (pintype "power_in"))
      (node (ref "U101") (pin "27") (pinfunction "VSS_27") (pintype "power_in"))
      (node (ref "U101") (pin "74") (pinfunction "VSS_74") (pintype "power_in"))
      (node (ref "U101") (pin "99") (pinfunction "VSS_99") (pintype "power_in"))
      (node (ref "U102") (pin "4") (pinfunction "VSS_4") (pintype "bidirectional"))
      (node (ref "U1101") (pin "P$10") (pinfunction "GND_P$10") (pintype "bidirectional"))
      (node (ref "U1101") (pin "P$25") (pinfunction "GND_P$25") (pintype "bidirectional"))
      (node (ref "U201") (pin "11") (pinfunction "GND_11") (pintype "power_in"))
      (node (ref "U202") (pin "11") (pinfunction "GND_11") (pintype "power_in"))
      (node (ref "U301") (pin "6") (pinfunction "GND_6") (pintype "power_in"))
      (node (ref "U302") (pin "2") (pinfunction "GND_2") (pintype "bidirectional"))
      (node (ref "U401") (pin "2") (pinfunction "GND_2") (pintype "power_in"))
      (node (ref "U401") (pin "5") (pinfunction "SHDN_5") (pintype "input"))
      (node (ref "U401") (pin "8") (pinfunction "RS_8") (pintype "input"))
      (node (ref "U501") (pin "10") (pinfunction "RES_P10_GND_10") (pintype "bidirectional"))
      (node (ref "U501") (pin "11") (pinfunction "RES_P11_GND_11") (pintype "bidirectional"))
      (node (ref "U501") (pin "12") (pinfunction "RES_P12_GND_12") (pintype "bidirectional"))
      (node (ref "U501") (pin "13") (pinfunction "GND_13") (pintype "bidirectional"))
      (node (ref "U501") (pin "8") (pinfunction "RES_P8_GND_8") (pintype "bidirectional"))
      (node (ref "U501") (pin "9") (pinfunction "RES_P9_GND_9") (pintype "bidirectional"))
      (node (ref "U502") (pin "10") (pinfunction "GND_10") (pintype "bidirectional"))
      (node (ref "U502") (pin "11") (pinfunction "GND_11") (pintype "bidirectional"))
      (node (ref "U502") (pin "12") (pinfunction "GND_12") (pintype "bidirectional"))
      (node (ref "U502") (pin "13") (pinfunction "GND_13") (pintype "bidirectional"))
      (node (ref "U502") (pin "9") (pinfunction "GND_9") (pintype "bidirectional"))
      (node (ref "U504") (pin "10") (pinfunction "RSRV_10") (pintype "bidirectional"))
      (node (ref "U504") (pin "12") (pinfunction "GND_12") (pintype "bidirectional"))
      (node (ref "U504") (pin "13") (pinfunction "GND_13") (pintype "bidirectional"))
      (node (ref "U504") (pin "16") (pinfunction "GND_16") (pintype "bidirectional"))
      (node (ref "U504") (pin "5") (pinfunction "GND_5") (pintype "bidirectional"))
      (node (ref "U505") (pin "1") (pinfunction "CLKIN_1") (pintype "bidirectional"))
      (node (ref "U505") (pin "18") (pinfunction "GND_18") (pintype "bidirectional"))
      (node (ref "U506") (pin "2") (pinfunction "PS_2") (pintype "bidirectional"))
      (node (ref "U506") (pin "3") (pinfunction "GND_3") (pintype "bidirectional"))
      (node (ref "U601") (pin "2") (pinfunction "VSS_2") (pintype "bidirectional"))
      (node (ref "U601") (pin "6") (pinfunction "VBAT_6") (pintype "bidirectional"))
      (node (ref "U601") (pin "GND") (pinfunction "VSS_GND") (pintype "bidirectional"))
      (node (ref "U601") (pin "P$2") (pinfunction "VSS_P$2") (pintype "bidirectional"))
      (node (ref "U601") (pin "P$3") (pinfunction "VSS_P$3") (pintype "bidirectional"))
      (node (ref "U602") (pin "2") (pinfunction "VSS_2") (pintype "bidirectional"))
      (node (ref "U602") (pin "6") (pinfunction "VBAT_6") (pintype "bidirectional"))
      (node (ref "U602") (pin "GND") (pinfunction "VSS_GND") (pintype "bidirectional"))
      (node (ref "U602") (pin "P$2") (pinfunction "VSS_P$2") (pintype "bidirectional"))
      (node (ref "U602") (pin "P$3") (pinfunction "VSS_P$3") (pintype "bidirectional"))
      (node (ref "U603") (pin "2") (pinfunction "GND_2") (pintype "bidirectional"))
      (node (ref "U603") (pin "GND") (pinfunction "GND_GND") (pintype "bidirectional"))
      (node (ref "U701") (pin "5") (pinfunction "GND_5") (pintype "power_in"))
      (node (ref "U702") (pin "4") (pinfunction "GND_4") (pintype "power_in"))
      (node (ref "U801") (pin "23") (pinfunction "VSS_1_23") (pintype "power_in"))
      (node (ref "U801") (pin "35") (pinfunction "VSS_2_35") (pintype "power_in"))
      (node (ref "U801") (pin "47") (pinfunction "VSS_3_47") (pintype "power_in"))
      (node (ref "U801") (pin "8") (pinfunction "VSSA_8") (pintype "power_in"))
      (node (ref "U901") (pin "11") (pinfunction "GND_11") (pintype "power_in"))
      (node (ref "U902") (pin "11") (pinfunction "GND_11") (pintype "power_in"))
      (node (ref "U903") (pin "1") (pinfunction "~{1OE}_1") (pintype "input"))
      (node (ref "U903") (pin "4") (pinfunction "GND_4") (pintype "power_in"))
      (node (ref "X101") (pin "2") (pinfunction "NC_2_2") (pintype "power_in"))
      (node (ref "X101") (pin "4") (pinfunction "NC_4_4") (pintype "power_in"))
      (node (ref "X503") (pin "2") (pinfunction "S_2") (pintype "passive"))
      (node (ref "X801") (pin "2") (pinfunction "NC_2_2") (pintype "power_in"))
      (node (ref "X801") (pin "4") (pinfunction "NC_4_4") (pintype "power_in"))
    )
    (net (code "47") (name "GPIO_EXT_1") (class "Default")
      (node (ref "J403") (pin "6") (pinfunction "6_6") (pintype "passive"))
      (node (ref "U101") (pin "8") (pinfunction "PC14_8") (pintype "bidirectional"))
    )
    (net (code "48") (name "GYRO_DRDY") (class "Default")
      (node (ref "U101") (pin "35") (pinfunction "PB0_35") (pintype "bidirectional"))
      (node (ref "U501") (pin "6") (pinfunction "DRDY/INT2_6") (pintype "output"))
      (node (ref "U502") (pin "6") (pinfunction "DRDY/INT2_6") (pintype "bidirectional"))
      (node (ref "X503") (pin "5") (pinfunction "S_5") (pintype "passive"))
    )
    (net (code "49") (name "IO-BOOT0") (class "Default")
      (node (ref "IO-BOOT1101") (pin "P$1") (pinfunction "P$1_P$1") (pintype "passive"))
      (node (ref "R801") (pin "P$1") (pinfunction "1_P$1") (pintype "passive"))
      (node (ref "U801") (pin "44") (pinfunction "BOOT0_44") (pintype "input"))
    )
    (net (code "50") (name "IO-CH1") (class "Default")
      (node (ref "U801") (pin "10") (pinfunction "PA0_10") (pintype "bidirectional"))
      (node (ref "U902") (pin "9") (pinfunction "A8_9") (pintype "bidirectional"))
    )
    (net (code "51") (name "IO-CH2") (class "Default")
      (node (ref "U801") (pin "11") (pinfunction "PA1_11") (pintype "bidirectional"))
      (node (ref "U902") (pin "8") (pinfunction "A7_8") (pintype "bidirectional"))
    )
    (net (code "52") (name "IO-CH3") (class "Default")
      (node (ref "U801") (pin "45") (pinfunction "PB8_45") (pintype "bidirectional"))
      (node (ref "U902") (pin "7") (pinfunction "A6_7") (pintype "bidirectional"))
    )
    (net (code "53") (name "IO-CH4") (class "Default")
      (node (ref "U801") (pin "46") (pinfunction "PB9_46") (pintype "bidirectional"))
      (node (ref "U902") (pin "6") (pinfunction "A5_6") (pintype "bidirectional"))
    )
    (net (code "54") (name "IO-CH5") (class "Default")
      (node (ref "U801") (pin "16") (pinfunction "PA6_16") (pintype "bidirectional"))
      (node (ref "U902") (pin "5") (pinfunction "A4_5") (pintype "bidirectional"))
    )
    (net (code "55") (name "IO-CH6") (class "Default")
      (node (ref "U801") (pin "17") (pinfunction "PA7_17") (pintype "bidirectional"))
      (node (ref "U902") (pin "4") (pinfunction "A3_4") (pintype "bidirectional"))
    )
    (net (code "56") (name "IO-CH7") (class "Default")
      (node (ref "U801") (pin "18") (pinfunction "PB0_18") (pintype "bidirectional"))
      (node (ref "U902") (pin "3") (pinfunction "A2_3") (pintype "bidirectional"))
    )
    (net (code "57") (name "IO-CH8") (class "Default")
      (node (ref "U801") (pin "19") (pinfunction "PB1_19") (pintype "bidirectional"))
      (node (ref "U902") (pin "1") (pinfunction "A1_1") (pintype "bidirectional"))
    )
    (net (code "58") (name "IO-SWCLK") (class "Default")
      (node (ref "JX802") (pin "4") (pinfunction "S_4") (pintype "passive"))
      (node (ref "U801") (pin "37") (pinfunction "PA14_37") (pintype "bidirectional"))
    )
    (net (code "59") (name "IO-SWDIO") (class "Default")
      (node (ref "JX802") (pin "2") (pinfunction "S_2") (pintype "passive"))
      (node (ref "U801") (pin "34") (pinfunction "PA13_34") (pintype "bidirectional"))
    )
    (net (code "60") (name "IO-SWO") (class "Default")
      (node (ref "JX802") (pin "6") (pinfunction "S_6") (pintype "passive"))
      (node (ref "U801") (pin "39") (pinfunction "PB3_39") (pintype "bidirectional"))
    )
    (net (code "61") (name "IO-USART1_RX") (class "Default")
      (node (ref "J801") (pin "P$3") (pinfunction "P$3_P$3") (pintype "bidirectional"))
      (node (ref "JX801") (pin "2") (pinfunction "+5V_2") (pintype "bidirectional"))
      (node (ref "U801") (pin "31") (pinfunction "PA10_31") (pintype "bidirectional"))
    )
    (net (code "62") (name "IO-USART1_TX") (class "Default")
      (node (ref "JX801") (pin "1") (pinfunction "PPM_1") (pintype "bidirectional"))
      (node (ref "R101") (pin "P$2") (pinfunction "2_P$2") (pintype "passive"))
      (node (ref "U801") (pin "30") (pinfunction "PA9_30") (pintype "bidirectional"))
    )
    (net (code "63") (name "IO-VDD_3V3") (class "Default")
      (node (ref "C1003") (pin "P$1") (pinfunction "1_P$1") (pintype "passive"))
      (node (ref "C1004") (pin "P$1") (pinfunction "1_P$1") (pintype "passive"))
      (node (ref "C802") (pin "P$1") (pinfunction "1_P$1") (pintype "passive"))
      (node (ref "C803") (pin "P$1") (pinfunction "1_P$1") (pintype "passive"))
      (node (ref "C804") (pin "P$1") (pinfunction "1_P$1") (pintype "passive"))
      (node (ref "C901") (pin "P$1") (pinfunction "1_P$1") (pintype "passive"))
      (node (ref "C903") (pin "P$1") (pinfunction "1_P$1") (pintype "passive"))
      (node (ref "D701") (pin "C") (pinfunction "C_C") (pintype "passive"))
      (node (ref "J702") (pin "1") (pinfunction "1_1") (pintype "passive"))
      (node (ref "JX802") (pin "1") (pinfunction "S_1") (pintype "passive"))
      (node (ref "U1002") (pin "7") (pinfunction "VOUT2_7") (pintype "bidirectional"))
      (node (ref "U801") (pin "24") (pinfunction "VDD_1_24") (pintype "power_in"))
      (node (ref "U801") (pin "36") (pinfunction "VDD_2_36") (pintype "power_in"))
      (node (ref "U801") (pin "48") (pinfunction "VDD_3_48") (pintype "power_in"))
      (node (ref "U801") (pin "9") (pinfunction "VDDA_9") (pintype "power_in"))
      (node (ref "U902") (pin "10") (pinfunction "OE_10") (pintype "input"))
      (node (ref "U902") (pin "19") (pinfunction "VCCB_19") (pintype "input"))
      (node (ref "U902") (pin "2") (pinfunction "VCCA_2") (pintype "input"))
      (node (ref "U903") (pin "8") (pinfunction "VCC_8") (pintype "power_in"))
    )
    (net (code "64") (name "IO-VDD_5V5") (class "Default")
      (node (ref "C1001") (pin "P$1") (pinfunction "1_P$1") (pintype "passive"))
      (node (ref "C1005") (pin "P$1") (pinfunction "1_P$1") (pintype "passive"))
      (node (ref "D1001") (pin "3") (pinfunction "CC_3") (pintype "passive"))
      (node (ref "J901") (pin "2") (pinfunction "S_2") (pintype "passive"))
      (node (ref "LED702") (pin "A") (pinfunction "A_A") (pintype "passive"))
      (node (ref "LED703") (pin "A") (pinfunction "A_A") (pintype "passive"))
      (node (ref "LED705") (pin "A") (pinfunction "A_A") (pintype "passive"))
      (node (ref "U1002") (pin "1") (pinfunction "VIN_1") (pintype "bidirectional"))
      (node (ref "U1002") (pin "4") (pinfunction "EN2_4") (pintype "bidirectional"))
    )
    (net (code "65") (name "IO-~{RESET}") (class "Default")
      (node (ref "C801") (pin "P$2") (pinfunction "2_P$2") (pintype "passive"))
      (node (ref "S801") (pin "A1") (pinfunction "1_A1") (pintype "passive"))
      (node (ref "U1002") (pin "3") (pinfunction "POR2_3") (pintype "bidirectional"))
      (node (ref "U801") (pin "7") (pinfunction "NRST_7") (pintype "input"))
    )
    (net (code "66") (name "IO-~{VDD_SERVO_IN_FAULT}") (class "Default")
      (node (ref "U1001") (pin "4") (pinfunction "~{FAULT}_4") (pintype "bidirectional"))
      (node (ref "U801") (pin "38") (pinfunction "PA15_38") (pintype "bidirectional"))
    )
    (net (code "67") (name "MAG_DRDY") (class "Default")
      (node (ref "U101") (pin "36") (pinfunction "PB1_36") (pintype "bidirectional"))
      (node (ref "U504") (pin "9") (pinfunction "INT2_9") (pintype "bidirectional"))
      (node (ref "X503") (pin "4") (pinfunction "S_4") (pintype "passive"))
    )
    (net (code "68") (name "MPU_DRDY") (class "Default")
      (node (ref "U101") (pin "62") (pinfunction "PD15_62") (pintype "bidirectional"))
      (node (ref "U505") (pin "12") (pinfunction "INT_12") (pintype "bidirectional"))
    )
    (net (code "69") (name "Net-(C102-1)") (class "Default")
      (node (ref "C102") (pin "P$1") (pinfunction "1_P$1") (pintype "passive"))
      (node (ref "U101") (pin "12") (pinfunction "OSC_IN_12") (pintype "input"))
      (node (ref "X101") (pin "3") (pinfunction "3_3") (pintype "bidirectional"))
    )
    (net (code "70") (name "Net-(C103-2)") (class "Default")
      (node (ref "C103") (pin "P$2") (pinfunction "2_P$2") (pintype "passive"))
      (node (ref "U101") (pin "13") (pinfunction "OSC_OUT_13") (pintype "output"))
      (node (ref "X101") (pin "1") (pinfunction "1_1") (pintype "bidirectional"))
    )
    (net (code "71") (name "Net-(C504-1)") (class "Default")
      (node (ref "C504") (pin "P$1") (pinfunction "1_P$1") (pintype "passive"))
      (node (ref "U501") (pin "14") (pinfunction "PLLFILT_14") (pintype "bidirectional"))
    )
    (net (code "72") (name "Net-(C505-1)") (class "Default")
      (node (ref "C505") (pin "P$1") (pinfunction "1_P$1") (pintype "passive"))
      (node (ref "U502") (pin "14") (pinfunction "CAP_14") (pintype "bidirectional"))
    )
    (net (code "73") (name "Net-(C509-1)") (class "Default")
      (node (ref "C509") (pin "P$1") (pinfunction "1_P$1") (pintype "passive"))
      (node (ref "U504") (pin "15") (pinfunction "C1_15") (pintype "bidirectional"))
    )
    (net (code "74") (name "Net-(C510-1)") (class "Default")
      (node (ref "C510") (pin "P$1") (pinfunction "1_P$1") (pintype "passive"))
      (node (ref "U504") (pin "2") (pinfunction "SETC_2") (pintype "bidirectional"))
    )
    (net (code "75") (name "Net-(C510-2)") (class "Default")
      (node (ref "C510") (pin "P$2") (pinfunction "2_P$2") (pintype "passive"))
      (node (ref "U504") (pin "3") (pinfunction "SETP_3") (pintype "bidirectional"))
    )
    (net (code "76") (name "Net-(C512-1)") (class "Default")
      (node (ref "C512") (pin "P$1") (pinfunction "1_P$1") (pintype "passive"))
      (node (ref "U505") (pin "10") (pinfunction "REGOUT_10") (pintype "bidirectional"))
    )
    (net (code "77") (name "Net-(C515-1)") (class "Default")
      (node (ref "C515") (pin "P$1") (pinfunction "1_P$1") (pintype "passive"))
      (node (ref "U505") (pin "20") (pinfunction "CPOUT_20") (pintype "bidirectional"))
    )
    (net (code "78") (name "Net-(C601-1)") (class "Default")
      (node (ref "C601") (pin "P$1") (pinfunction "1_P$1") (pintype "passive"))
      (node (ref "C615") (pin "P$1") (pinfunction "1_P$1") (pintype "passive"))
      (node (ref "L603") (pin "P$2") (pinfunction "P$2_P$2") (pintype "bidirectional"))
      (node (ref "R603") (pin "P$1") (pinfunction "1_P$1") (pintype "passive"))
      (node (ref "U603") (pin "1") (pinfunction "VIN_1") (pintype "bidirectional"))
      (node (ref "U603") (pin "4") (pinfunction "EN2_4") (pintype "bidirectional"))
    )
    (net (code "79") (name "Net-(C602-2)") (class "Default")
      (node (ref "C602") (pin "P$2") (pinfunction "2_P$2") (pintype "passive"))
      (node (ref "U603") (pin "6") (pinfunction "CSET_6") (pintype "bidirectional"))
    )
    (net (code "80") (name "Net-(C611-1)") (class "Default")
      (node (ref "C611") (pin "P$1") (pinfunction "1_P$1") (pintype "passive"))
      (node (ref "U101") (pin "49") (pinfunction "VCAP_1_49") (pintype "power_in"))
    )
    (net (code "81") (name "Net-(C613-1)") (class "Default")
      (node (ref "C613") (pin "P$1") (pinfunction "1_P$1") (pintype "passive"))
      (node (ref "U101") (pin "73") (pinfunction "VCAP_2_73") (pintype "power_in"))
    )
    (net (code "82") (name "Net-(C703-1)") (class "Default")
      (node (ref "C703") (pin "P$1") (pinfunction "1_P$1") (pintype "passive"))
      (node (ref "J701") (pin "1") (pinfunction "1_1") (pintype "passive"))
      (node (ref "R703") (pin "P$1") (pinfunction "1_P$1") (pintype "passive"))
      (node (ref "U702") (pin "1") (pinfunction "OUT_1") (pintype "output"))
    )
    (net (code "83") (name "Net-(C704-1)") (class "Default")
      (node (ref "C704") (pin "P$1") (pinfunction "1_P$1") (pintype "passive"))
      (node (ref "R705") (pin "P$1") (pinfunction "1_P$1") (pintype "passive"))
      (node (ref "U702") (pin "6") (pinfunction "VCC_6") (pintype "bidirectional"))
    )
    (net (code "84") (name "Net-(C805-1)") (class "Default")
      (node (ref "C805") (pin "P$1") (pinfunction "1_P$1") (pintype "passive"))
      (node (ref "U801") (pin "5") (pinfunction "PD0/OSC<=_5") (pintype "bidirectional"))
      (node (ref "X801") (pin "3") (pinfunction "3_3") (pintype "bidirectional"))
    )
    (net (code "85") (name "Net-(C806-2)") (class "Default")
      (node (ref "C806") (pin "P$2") (pinfunction "2_P$2") (pintype "passive"))
      (node (ref "U801") (pin "6") (pinfunction "PD1/OSC=>_6") (pintype "bidirectional"))
      (node (ref "X801") (pin "1") (pinfunction "1_1") (pintype "bidirectional"))
    )
    (net (code "86") (name "Net-(C1002-1)") (class "Default")
      (node (ref "C1002") (pin "P$1") (pinfunction "1_P$1") (pintype "passive"))
      (node (ref "U1002") (pin "6") (pinfunction "CSET_6") (pintype "bidirectional"))
    )
    (net (code "87") (name "Net-(C1105-1)") (class "Default")
      (node (ref "C1105") (pin "P$1") (pinfunction "1_P$1") (pintype "passive"))
      (node (ref "U1101") (pin "P$18") (pinfunction "VS1_P$18") (pintype "bidirectional"))
      (node (ref "U1102") (pin "P$1") (pinfunction "S_P$1") (pintype "passive"))
      (node (ref "U1102") (pin "P$3") (pinfunction "S_P$3") (pintype "passive"))
    )
    (net (code "88") (name "Net-(C1106-1)") (class "Default")
      (node (ref "C1106") (pin "P$1") (pinfunction "1_P$1") (pintype "passive"))
      (node (ref "U1101") (pin "P$16") (pinfunction "VS2_P$16") (pintype "bidirectional"))
      (node (ref "U1103") (pin "P$1") (pinfunction "S_P$1") (pintype "passive"))
      (node (ref "U1103") (pin "P$3") (pinfunction "S_P$3") (pintype "passive"))
    )
    (net (code "89") (name "Net-(C1107-1)") (class "Default")
      (node (ref "C1107") (pin "P$1") (pinfunction "1_P$1") (pintype "passive"))
      (node (ref "U1101") (pin "P$14") (pinfunction "VS3_P$14") (pintype "bidirectional"))
      (node (ref "U1104") (pin "P$1") (pinfunction "S_P$1") (pintype "passive"))
      (node (ref "U1104") (pin "P$3") (pinfunction "S_P$3") (pintype "passive"))
    )
    (net (code "90") (name "Net-(C1108-1)") (class "Default")
      (node (ref "C1108") (pin "P$1") (pinfunction "1_P$1") (pintype "passive"))
      (node (ref "R1105") (pin "P$2") (pinfunction "2_P$2") (pintype "passive"))
      (node (ref "R1106") (pin "P$1") (pinfunction "1_P$1") (pintype "passive"))
      (node (ref "U1101") (pin "P$1") (pinfunction "UV1_P$1") (pintype "bidirectional"))
    )
    (net (code "91") (name "Net-(C1109-1)") (class "Default")
      (node (ref "C1109") (pin "P$1") (pinfunction "1_P$1") (pintype "passive"))
      (node (ref "R1109") (pin "P$2") (pinfunction "2_P$2") (pintype "passive"))
      (node (ref "R1110") (pin "P$1") (pinfunction "1_P$1") (pintype "passive"))
      (node (ref "U1101") (pin "P$3") (pinfunction "UV2_P$3") (pintype "bidirectional"))
    )
    (net (code "92") (name "Net-(C1110-1)") (class "Default")
      (node (ref "C1110") (pin "P$1") (pinfunction "1_P$1") (pintype "passive"))
      (node (ref "R1112") (pin "P$2") (pinfunction "2_P$2") (pintype "passive"))
      (node (ref "R1113") (pin "P$1") (pinfunction "1_P$1") (pintype "passive"))
      (node (ref "U1101") (pin "P$5") (pinfunction "UV3_P$5") (pintype "bidirectional"))
    )
    (net (code "93") (name "Net-(D201-PadC)") (class "Default")
      (node (ref "D201") (pin "C") (pinfunction "C_C") (pintype "passive"))
      (node (ref "J201") (pin "1") (pinfunction "1_1") (pintype "passive"))
      (node (ref "L201") (pin "P$2") (pinfunction "P$2_P$2") (pintype "bidirectional"))
    )
    (net (code "94") (name "Net-(D202-PadC)") (class "Default")
      (node (ref "D202") (pin "C") (pinfunction "C_C") (pintype "passive"))
      (node (ref "J202") (pin "1") (pinfunction "1_1") (pintype "passive"))
      (node (ref "L202") (pin "P$2") (pinfunction "P$2_P$2") (pintype "bidirectional"))
    )
    (net (code "95") (name "Net-(D203-PadC)") (class "Default")
      (node (ref "D203") (pin "C") (pinfunction "C_C") (pintype "passive"))
      (node (ref "J203") (pin "1") (pinfunction "1_1") (pintype "passive"))
      (node (ref "J204") (pin "1") (pinfunction "1_1") (pintype "passive"))
      (node (ref "L203") (pin "P$2") (pinfunction "P$2_P$2") (pintype "bidirectional"))
    )
    (net (code "96") (name "Net-(D401-PadC)") (class "Default")
      (node (ref "D401") (pin "C") (pinfunction "C_C") (pintype "passive"))
      (node (ref "J401") (pin "1") (pinfunction "1_1") (pintype "passive"))
      (node (ref "J402") (pin "1") (pinfunction "1_1") (pintype "passive"))
      (node (ref "L401") (pin "P$2") (pinfunction "P$2_P$2") (pintype "bidirectional"))
    )
    (net (code "97") (name "Net-(D402-PadC)") (class "Default")
      (node (ref "D402") (pin "C") (pinfunction "C_C") (pintype "passive"))
      (node (ref "J403") (pin "1") (pinfunction "1_1") (pintype "passive"))
      (node (ref "L402") (pin "P$2") (pinfunction "P$2_P$2") (pintype "bidirectional"))
    )
    (net (code "98") (name "Net-(D403-PadC)") (class "Default")
      (node (ref "D403") (pin "C") (pinfunction "C_C") (pintype "passive"))
      (node (ref "J404") (pin "1") (pinfunction "1_1") (pintype "passive"))
      (node (ref "L404") (pin "P$2") (pinfunction "P$2_P$2") (pintype "bidirectional"))
    )
    (net (code "99") (name "Net-(D404-PadC)") (class "Default")
      (node (ref "D404") (pin "C") (pinfunction "C_C") (pintype "passive"))
      (node (ref "J405") (pin "1") (pinfunction "1_1") (pintype "passive"))
      (node (ref "L403") (pin "P$2") (pinfunction "P$2_P$2") (pintype "bidirectional"))
    )
    (net (code "100") (name "Net-(D904-C)") (class "Default")
      (node (ref "D903") (pin "C") (pinfunction "C_C") (pintype "passive"))
      (node (ref "D904") (pin "CATHODE") (pinfunction "C_CATHODE") (pintype "passive"))
      (node (ref "L901") (pin "P$1") (pinfunction "P$1_P$1") (pintype "bidirectional"))
    )
    (net (code "101") (name "Net-(D1001-A1)") (class "Default")
      (node (ref "D1001") (pin "1") (pinfunction "A1_1") (pintype "passive"))
      (node (ref "F1001") (pin "2") (pinfunction "2_2") (pintype "bidirectional"))
    )
    (net (code "102") (name "Net-(D1001-A2)") (class "Default")
      (node (ref "D1001") (pin "2") (pinfunction "A2_2") (pintype "passive"))
      (node (ref "U1001") (pin "8") (pinfunction "OUT_8") (pintype "bidirectional"))
    )
    (net (code "103") (name "Net-(J301-2)") (class "Default")
      (node (ref "J301") (pin "D-") (pinfunction "2_D-") (pintype "bidirectional"))
      (node (ref "J302") (pin "3") (pinfunction "3_3") (pintype "passive"))
      (node (ref "U302") (pin "1") (pinfunction "D1I_1") (pintype "bidirectional"))
    )
    (net (code "104") (name "Net-(J301-3)") (class "Default")
      (node (ref "J301") (pin "D+") (pinfunction "3_D+") (pintype "bidirectional"))
      (node (ref "J302") (pin "2") (pinfunction "2_2") (pintype "passive"))
      (node (ref "U302") (pin "3") (pinfunction "D2I_3") (pintype "bidirectional"))
    )
    (net (code "105") (name "Net-(J901A-S)") (class "Default")
      (node (ref "J901") (pin "1") (pinfunction "S_1") (pintype "passive"))
      (node (ref "R909") (pin "P$2") (pinfunction "2_P$2") (pintype "passive"))
    )
    (net (code "106") (name "Net-(J901B-S)") (class "Default")
      (node (ref "J901") (pin "10") (pinfunction "S_10") (pintype "passive"))
      (node (ref "R914") (pin "P$2") (pinfunction "2_P$2") (pintype "passive"))
    )
    (net (code "107") (name "Net-(J901C-S)") (class "Default")
      (node (ref "J901") (pin "13") (pinfunction "S_13") (pintype "passive"))
      (node (ref "R906") (pin "P$2") (pinfunction "2_P$2") (pintype "passive"))
    )
    (net (code "108") (name "Net-(J901D-S)") (class "Default")
      (node (ref "J901") (pin "16") (pinfunction "S_16") (pintype "passive"))
      (node (ref "R915") (pin "P$2") (pinfunction "2_P$2") (pintype "passive"))
    )
    (net (code "109") (name "Net-(J901E-S)") (class "Default")
      (node (ref "J901") (pin "19") (pinfunction "S_19") (pintype "passive"))
      (node (ref "R907") (pin "P$2") (pinfunction "2_P$2") (pintype "passive"))
    )
    (net (code "110") (name "Net-(J901G-S)") (class "Default")
      (node (ref "J901") (pin "22") (pinfunction "S_22") (pintype "passive"))
      (node (ref "R916") (pin "P$2") (pinfunction "2_P$2") (pintype "passive"))
    )
    (net (code "111") (name "Net-(J901H-S)") (class "Default")
      (node (ref "J901") (pin "25") (pinfunction "S_25") (pintype "passive"))
      (node (ref "R908") (pin "P$2") (pinfunction "2_P$2") (pintype "passive"))
    )
    (net (code "112") (name "Net-(J901I-S)") (class "Default")
      (node (ref "J901") (pin "28") (pinfunction "S_28") (pintype "passive"))
      (node (ref "R917") (pin "P$2") (pinfunction "2_P$2") (pintype "passive"))
    )
    (net (code "113") (name "Net-(J901J-S)") (class "Default")
      (node (ref "J901") (pin "31") (pinfunction "S_31") (pintype "passive"))
      (node (ref "R902") (pin "P$2") (pinfunction "2_P$2") (pintype "passive"))
    )
    (net (code "114") (name "Net-(J901K-S)") (class "Default")
      (node (ref "J901") (pin "34") (pinfunction "S_34") (pintype "passive"))
      (node (ref "R911") (pin "P$2") (pinfunction "2_P$2") (pintype "passive"))
    )
    (net (code "115") (name "Net-(J901L-S)") (class "Default")
      (node (ref "J901") (pin "37") (pinfunction "S_37") (pintype "passive"))
      (node (ref "R903") (pin "P$2") (pinfunction "2_P$2") (pintype "passive"))
    )
    (net (code "116") (name "Net-(J901M-S)") (class "Default")
      (node (ref "J901") (pin "4") (pinfunction "S_4") (pintype "passive"))
      (node (ref "R910") (pin "P$2") (pinfunction "2_P$2") (pintype "passive"))
    )
    (net (code "117") (name "Net-(J901N-S)") (class "Default")
      (node (ref "J901") (pin "40") (pinfunction "S_40") (pintype "passive"))
      (node (ref "R912") (pin "P$2") (pinfunction "2_P$2") (pintype "passive"))
    )
    (net (code "118") (name "Net-(J901O-S)") (class "Default")
      (node (ref "J901") (pin "43") (pinfunction "S_43") (pintype "passive"))
      (node (ref "R904") (pin "P$2") (pinfunction "2_P$2") (pintype "passive"))
    )
    (net (code "119") (name "Net-(J901P-S)") (class "Default")
      (node (ref "J901") (pin "46") (pinfunction "S_46") (pintype "passive"))
      (node (ref "R913") (pin "P$2") (pinfunction "2_P$2") (pintype "passive"))
    )
    (net (code "120") (name "Net-(J901Q-S)") (class "Default")
      (node (ref "J901") (pin "7") (pinfunction "S_7") (pintype "passive"))
      (node (ref "R905") (pin "P$2") (pinfunction "2_P$2") (pintype "passive"))
    )
    (net (code "121") (name "Net-(L701-2)") (class "Default")
      (node (ref "L701") (pin "P$2") (pinfunction "2_P$2") (pintype "passive"))
      (node (ref "U702") (pin "5") (pinfunction "SW_5") (pintype "passive"))
    )
    (net (code "122") (name "Net-(R101-1)") (class "Default")
      (node (ref "R101") (pin "P$1") (pinfunction "1_P$1") (pintype "passive"))
      (node (ref "U101") (pin "69") (pinfunction "PA10_69") (pintype "bidirectional"))
    )
    (net (code "123") (name "Net-(R102-1)") (class "Default")
      (node (ref "R102") (pin "P$1") (pinfunction "1_P$1") (pintype "passive"))
      (node (ref "U101") (pin "37") (pinfunction "PB2_37") (pintype "bidirectional"))
    )
    (net (code "124") (name "Net-(R201-1)") (class "Default")
      (node (ref "R201") (pin "P$1") (pinfunction "1_P$1") (pintype "passive"))
      (node (ref "U201") (pin "20") (pinfunction "B1_20") (pintype "bidirectional"))
    )
    (net (code "125") (name "Net-(R202-1)") (class "Default")
      (node (ref "R202") (pin "P$1") (pinfunction "1_P$1") (pintype "passive"))
      (node (ref "U201") (pin "17") (pinfunction "B3_17") (pintype "bidirectional"))
    )
    (net (code "126") (name "Net-(R203-1)") (class "Default")
      (node (ref "R203") (pin "P$1") (pinfunction "1_P$1") (pintype "passive"))
      (node (ref "U201") (pin "15") (pinfunction "B5_15") (pintype "bidirectional"))
    )
    (net (code "127") (name "Net-(R204-1)") (class "Default")
      (node (ref "R204") (pin "P$1") (pinfunction "1_P$1") (pintype "passive"))
      (node (ref "U201") (pin "13") (pinfunction "B7_13") (pintype "bidirectional"))
    )
    (net (code "128") (name "Net-(R205-1)") (class "Default")
      (node (ref "R205") (pin "P$1") (pinfunction "1_P$1") (pintype "passive"))
      (node (ref "U202") (pin "17") (pinfunction "B3_17") (pintype "bidirectional"))
    )
    (net (code "129") (name "Net-(R206-1)") (class "Default")
      (node (ref "R206") (pin "P$1") (pinfunction "1_P$1") (pintype "passive"))
      (node (ref "U202") (pin "15") (pinfunction "B5_15") (pintype "bidirectional"))
    )
    (net (code "130") (name "Net-(R207-1)") (class "Default")
      (node (ref "R207") (pin "P$1") (pinfunction "1_P$1") (pintype "passive"))
      (node (ref "U202") (pin "13") (pinfunction "B7_13") (pintype "bidirectional"))
    )
    (net (code "131") (name "Net-(R208-1)") (class "Default")
      (node (ref "R208") (pin "P$1") (pinfunction "1_P$1") (pintype "passive"))
      (node (ref "U201") (pin "18") (pinfunction "B2_18") (pintype "bidirectional"))
    )
    (net (code "132") (name "Net-(R209-1)") (class "Default")
      (node (ref "R209") (pin "P$1") (pinfunction "1_P$1") (pintype "passive"))
      (node (ref "U201") (pin "16") (pinfunction "B4_16") (pintype "bidirectional"))
    )
    (net (code "133") (name "Net-(R210-1)") (class "Default")
      (node (ref "R210") (pin "P$1") (pinfunction "1_P$1") (pintype "passive"))
      (node (ref "U201") (pin "14") (pinfunction "B6_14") (pintype "bidirectional"))
    )
    (net (code "134") (name "Net-(R211-1)") (class "Default")
      (node (ref "R211") (pin "P$1") (pinfunction "1_P$1") (pintype "passive"))
      (node (ref "U201") (pin "12") (pinfunction "B8_12") (pintype "bidirectional"))
    )
    (net (code "135") (name "Net-(R212-1)") (class "Default")
      (node (ref "R212") (pin "P$1") (pinfunction "1_P$1") (pintype "passive"))
      (node (ref "U202") (pin "16") (pinfunction "B4_16") (pintype "bidirectional"))
    )
    (net (code "136") (name "Net-(R213-1)") (class "Default")
      (node (ref "R213") (pin "P$1") (pinfunction "1_P$1") (pintype "passive"))
      (node (ref "U202") (pin "14") (pinfunction "B6_14") (pintype "bidirectional"))
    )
    (net (code "137") (name "Net-(R214-1)") (class "Default")
      (node (ref "R214") (pin "P$1") (pinfunction "1_P$1") (pintype "passive"))
      (node (ref "U202") (pin "12") (pinfunction "B8_12") (pintype "bidirectional"))
    )
    (net (code "138") (name "Net-(R215-2)") (class "Default")
      (node (ref "J203") (pin "4") (pinfunction "4_4") (pintype "passive"))
      (node (ref "R215") (pin "P$2") (pinfunction "2_P$2") (pintype "passive"))
    )
    (net (code "139") (name "Net-(R216-2)") (class "Default")
      (node (ref "J203") (pin "5") (pinfunction "5_5") (pintype "passive"))
      (node (ref "R216") (pin "P$2") (pinfunction "2_P$2") (pintype "passive"))
    )
    (net (code "140") (name "Net-(R404-2)") (class "Default")
      (node (ref "J401") (pin "2") (pinfunction "2_2") (pintype "passive"))
      (node (ref "R404") (pin "P$2") (pinfunction "2_P$2") (pintype "passive"))
    )
    (net (code "141") (name "Net-(R405-2)") (class "Default")
      (node (ref "J401") (pin "3") (pinfunction "3_3") (pintype "passive"))
      (node (ref "R405") (pin "P$2") (pinfunction "2_P$2") (pintype "passive"))
    )
    (net (code "142") (name "Net-(R407-2)") (class "Default")
      (node (ref "J404") (pin "2") (pinfunction "2_2") (pintype "passive"))
      (node (ref "R407") (pin "P$2") (pinfunction "2_P$2") (pintype "passive"))
    )
    (net (code "143") (name "Net-(R408-2)") (class "Default")
      (node (ref "J404") (pin "4") (pinfunction "4_4") (pintype "passive"))
      (node (ref "R408") (pin "P$2") (pinfunction "2_P$2") (pintype "passive"))
    )
    (net (code "144") (name "Net-(R608-2)") (class "Default")
      (node (ref "D602") (pin "C") (pinfunction "C_C") (pintype "passive"))
      (node (ref "R608") (pin "P$2") (pinfunction "2_P$2") (pintype "passive"))
    )
    (net (code "145") (name "Net-(R616-1)") (class "Default")
      (node (ref "R616") (pin "P$1") (pinfunction "1_P$1") (pintype "passive"))
      (node (ref "U602") (pin "7") (pinfunction "ILIM_7") (pintype "bidirectional"))
    )
    (net (code "146") (name "Net-(R617-1)") (class "Default")
      (node (ref "R617") (pin "P$1") (pinfunction "1_P$1") (pintype "passive"))
      (node (ref "U601") (pin "7") (pinfunction "ILIM_7") (pintype "bidirectional"))
    )
    (net (code "147") (name "Net-(R701-1)") (class "Default")
      (node (ref "R701") (pin "P$1") (pinfunction "1_P$1") (pintype "passive"))
      (node (ref "U702") (pin "7") (pinfunction "+IN_7") (pintype "input"))
    )
    (net (code "148") (name "Net-(R702-1)") (class "Default")
      (node (ref "R702") (pin "P$1") (pinfunction "1_P$1") (pintype "passive"))
      (node (ref "R703") (pin "P$2") (pinfunction "2_P$2") (pintype "passive"))
      (node (ref "U702") (pin "8") (pinfunction "-IN_8") (pintype "input"))
    )
    (net (code "149") (name "Net-(R704-2)") (class "Default")
      (node (ref "R704") (pin "P$2") (pinfunction "2_P$2") (pintype "passive"))
      (node (ref "U701") (pin "6") (pinfunction "REXT_6") (pintype "bidirectional"))
    )
    (net (code "150") (name "Net-(R705-2)") (class "Default")
      (node (ref "R705") (pin "P$2") (pinfunction "2_P$2") (pintype "passive"))
      (node (ref "R706") (pin "P$1") (pinfunction "1_P$1") (pintype "passive"))
      (node (ref "U702") (pin "2") (pinfunction "FB_2") (pintype "bidirectional"))
    )
    (net (code "151") (name "Net-(R707-2)") (class "Default")
      (node (ref "R707") (pin "P$2") (pinfunction "2_P$2") (pintype "passive"))
      (node (ref "R735") (pin "P$1") (pinfunction "1_P$1") (pintype "passive"))
    )
    (net (code "152") (name "Net-(R708-2)") (class "Default")
      (node (ref "LED702") (pin "C") (pinfunction "C_C") (pintype "passive"))
      (node (ref "R708") (pin "P$2") (pinfunction "2_P$2") (pintype "passive"))
    )
    (net (code "153") (name "Net-(R709-2)") (class "Default")
      (node (ref "R709") (pin "P$2") (pinfunction "2_P$2") (pintype "passive"))
      (node (ref "R736") (pin "P$1") (pinfunction "1_P$1") (pintype "passive"))
    )
    (net (code "154") (name "Net-(R710-1)") (class "Default")
      (node (ref "J702") (pin "2") (pinfunction "2_2") (pintype "passive"))
      (node (ref "R710") (pin "P$1") (pinfunction "1_P$1") (pintype "passive"))
    )
    (net (code "155") (name "Net-(R711-2)") (class "Default")
      (node (ref "LED704") (pin "C") (pinfunction "C_C") (pintype "passive"))
      (node (ref "R711") (pin "P$2") (pinfunction "2_P$2") (pintype "passive"))
    )
    (net (code "156") (name "Net-(R712-2)") (class "Default")
      (node (ref "LED705") (pin "C") (pinfunction "C_C") (pintype "passive"))
      (node (ref "R712") (pin "P$2") (pinfunction "2_P$2") (pintype "passive"))
    )
    (net (code "157") (name "Net-(R735-2)") (class "Default")
      (node (ref "LED701") (pin "C") (pinfunction "C_C") (pintype "passive"))
      (node (ref "R735") (pin "P$2") (pinfunction "2_P$2") (pintype "passive"))
    )
    (net (code "158") (name "Net-(R736-2)") (class "Default")
      (node (ref "LED703") (pin "C") (pinfunction "C_C") (pintype "passive"))
      (node (ref "R736") (pin "P$2") (pinfunction "2_P$2") (pintype "passive"))
    )
    (net (code "159") (name "Net-(R802-1)") (class "Default")
      (node (ref "R802") (pin "P$1") (pinfunction "1_P$1") (pintype "passive"))
      (node (ref "U801") (pin "20") (pinfunction "PB2_20") (pintype "bidirectional"))
    )
    (net (code "160") (name "Net-(R803-1)") (class "Default")
      (node (ref "R803") (pin "P$1") (pinfunction "1_P$1") (pintype "passive"))
      (node (ref "U801") (pin "12") (pinfunction "PA2_12") (pintype "bidirectional"))
    )
    (net (code "161") (name "Net-(R804-1)") (class "Default")
      (node (ref "R804") (pin "P$1") (pinfunction "1_P$1") (pintype "passive"))
      (node (ref "U801") (pin "13") (pinfunction "PA3_13") (pintype "bidirectional"))
    )
    (net (code "162") (name "Net-(R901-2)") (class "Default")
      (node (ref "D902") (pin "C") (pinfunction "C_C") (pintype "passive"))
      (node (ref "R901") (pin "P$2") (pinfunction "2_P$2") (pintype "passive"))
      (node (ref "R910") (pin "P$1") (pinfunction "1_P$1") (pintype "passive"))
      (node (ref "U903") (pin "3") (pinfunction "2Y_3") (pintype "bidirectional"))
    )
    (net (code "163") (name "Net-(R902-1)") (class "Default")
      (node (ref "R902") (pin "P$1") (pinfunction "1_P$1") (pintype "passive"))
      (node (ref "U901") (pin "20") (pinfunction "B1_20") (pintype "bidirectional"))
    )
    (net (code "164") (name "Net-(R903-1)") (class "Default")
      (node (ref "R903") (pin "P$1") (pinfunction "1_P$1") (pintype "passive"))
      (node (ref "U901") (pin "17") (pinfunction "B3_17") (pintype "bidirectional"))
    )
    (net (code "165") (name "Net-(R904-1)") (class "Default")
      (node (ref "R904") (pin "P$1") (pinfunction "1_P$1") (pintype "passive"))
      (node (ref "U901") (pin "15") (pinfunction "B5_15") (pintype "bidirectional"))
    )
    (net (code "166") (name "Net-(R905-1)") (class "Default")
      (node (ref "R905") (pin "P$1") (pinfunction "1_P$1") (pintype "passive"))
      (node (ref "U902") (pin "20") (pinfunction "B1_20") (pintype "bidirectional"))
    )
    (net (code "167") (name "Net-(R906-1)") (class "Default")
      (node (ref "R906") (pin "P$1") (pinfunction "1_P$1") (pintype "passive"))
      (node (ref "U902") (pin "17") (pinfunction "B3_17") (pintype "bidirectional"))
    )
    (net (code "168") (name "Net-(R907-1)") (class "Default")
      (node (ref "R907") (pin "P$1") (pinfunction "1_P$1") (pintype "passive"))
      (node (ref "U902") (pin "15") (pinfunction "B5_15") (pintype "bidirectional"))
    )
    (net (code "169") (name "Net-(R908-1)") (class "Default")
      (node (ref "R908") (pin "P$1") (pinfunction "1_P$1") (pintype "passive"))
      (node (ref "U902") (pin "13") (pinfunction "B7_13") (pintype "bidirectional"))
    )
    (net (code "170") (name "Net-(R911-1)") (class "Default")
      (node (ref "R911") (pin "P$1") (pinfunction "1_P$1") (pintype "passive"))
      (node (ref "U901") (pin "18") (pinfunction "B2_18") (pintype "bidirectional"))
    )
    (net (code "171") (name "Net-(R912-1)") (class "Default")
      (node (ref "R912") (pin "P$1") (pinfunction "1_P$1") (pintype "passive"))
      (node (ref "U901") (pin "16") (pinfunction "B4_16") (pintype "bidirectional"))
    )
    (net (code "172") (name "Net-(R913-1)") (class "Default")
      (node (ref "R913") (pin "P$1") (pinfunction "1_P$1") (pintype "passive"))
      (node (ref "U901") (pin "14") (pinfunction "B6_14") (pintype "bidirectional"))
    )
    (net (code "173") (name "Net-(R914-1)") (class "Default")
      (node (ref "R914") (pin "P$1") (pinfunction "1_P$1") (pintype "passive"))
      (node (ref "U902") (pin "18") (pinfunction "B2_18") (pintype "bidirectional"))
    )
    (net (code "174") (name "Net-(R915-1)") (class "Default")
      (node (ref "R915") (pin "P$1") (pinfunction "1_P$1") (pintype "passive"))
      (node (ref "U902") (pin "16") (pinfunction "B4_16") (pintype "bidirectional"))
    )
    (net (code "175") (name "Net-(R916-1)") (class "Default")
      (node (ref "R916") (pin "P$1") (pinfunction "1_P$1") (pintype "passive"))
      (node (ref "U902") (pin "14") (pinfunction "B6_14") (pintype "bidirectional"))
    )
    (net (code "176") (name "Net-(R917-1)") (class "Default")
      (node (ref "R917") (pin "P$1") (pinfunction "1_P$1") (pintype "passive"))
      (node (ref "U902") (pin "12") (pinfunction "B8_12") (pintype "bidirectional"))
    )
    (net (code "177") (name "Net-(R918-2)") (class "Default")
      (node (ref "R918") (pin "P$2") (pinfunction "2_P$2") (pintype "passive"))
      (node (ref "R922") (pin "P$1") (pinfunction "1_P$1") (pintype "passive"))
    )
    (net (code "178") (name "Net-(R1001-2)") (class "Default")
      (node (ref "R1001") (pin "P$2") (pinfunction "2_P$2") (pintype "passive"))
      (node (ref "U1001") (pin "7") (pinfunction "ILIM_7") (pintype "bidirectional"))
    )
    (net (code "179") (name "Net-(R1101-2)") (class "Default")
      (node (ref "L1101") (pin "P$2") (pinfunction "P$2_P$2") (pintype "bidirectional"))
      (node (ref "R1101") (pin "P$2") (pinfunction "2_P$2") (pintype "passive"))
    )
    (net (code "180") (name "Net-(R1102-2)") (class "Default")
      (node (ref "L1102") (pin "P$2") (pinfunction "P$2_P$2") (pintype "bidirectional"))
      (node (ref "R1102") (pin "P$2") (pinfunction "2_P$2") (pintype "passive"))
    )
    (net (code "181") (name "Net-(R1103-1)") (class "Default")
      (node (ref "J601") (pin "4") (pinfunction "4_4") (pintype "passive"))
      (node (ref "L1102") (pin "P$1") (pinfunction "P$1_P$1") (pintype "bidirectional"))
      (node (ref "R1103") (pin "P$1") (pinfunction "1_P$1") (pintype "passive"))
    )
    (net (code "182") (name "Net-(R1104-1)") (class "Default")
      (node (ref "J601") (pin "3") (pinfunction "3_3") (pintype "passive"))
      (node (ref "L1101") (pin "P$1") (pinfunction "P$1_P$1") (pintype "bidirectional"))
      (node (ref "R1104") (pin "P$1") (pinfunction "1_P$1") (pintype "passive"))
    )
    (net (code "183") (name "Net-(R1106-2)") (class "Default")
      (node (ref "R1106") (pin "P$2") (pinfunction "2_P$2") (pintype "passive"))
      (node (ref "R1107") (pin "P$1") (pinfunction "1_P$1") (pintype "passive"))
      (node (ref "U1101") (pin "P$2") (pinfunction "OV1_P$2") (pintype "bidirectional"))
    )
    (net (code "184") (name "Net-(R1110-2)") (class "Default")
      (node (ref "R1110") (pin "P$2") (pinfunction "2_P$2") (pintype "passive"))
      (node (ref "R1111") (pin "P$1") (pinfunction "1_P$1") (pintype "passive"))
      (node (ref "U1101") (pin "P$4") (pinfunction "OV2_P$4") (pintype "bidirectional"))
    )
    (net (code "185") (name "Net-(R1113-2)") (class "Default")
      (node (ref "R1113") (pin "P$2") (pinfunction "2_P$2") (pintype "passive"))
      (node (ref "R1114") (pin "P$1") (pinfunction "1_P$1") (pintype "passive"))
      (node (ref "U1101") (pin "P$6") (pinfunction "OV3_P$6") (pintype "bidirectional"))
    )
    (net (code "186") (name "Net-(R1115-2)") (class "Default")
      (node (ref "R1115") (pin "P$2") (pinfunction "2_P$2") (pintype "passive"))
      (node (ref "U1101") (pin "P$24") (pinfunction "HYS_P$24") (pintype "bidirectional"))
    )
    (net (code "187") (name "Net-(U701-OUT0)") (class "Default")
      (node (ref "U701") (pin "9") (pinfunction "OUT0_9") (pintype "open_collector"))
      (node (ref "U703") (pin "C1") (pinfunction "C_C1") (pintype "passive"))
    )
    (net (code "188") (name "Net-(U701-OUT1)") (class "Default")
      (node (ref "U701") (pin "8") (pinfunction "OUT1_8") (pintype "open_collector"))
      (node (ref "U703") (pin "C2") (pinfunction "C_C2") (pintype "passive"))
    )
    (net (code "189") (name "Net-(U701-OUT2)") (class "Default")
      (node (ref "U701") (pin "7") (pinfunction "OUT2_7") (pintype "open_collector"))
      (node (ref "U703") (pin "C3") (pinfunction "C_C3") (pintype "passive"))
    )
    (net (code "190") (name "Net-(U1101-G1)") (class "Default")
      (node (ref "U1101") (pin "P$17") (pinfunction "G1_P$17") (pintype "bidirectional"))
      (node (ref "U1102") (pin "P$2") (pinfunction "G_P$2") (pintype "passive"))
      (node (ref "U1102") (pin "P$4") (pinfunction "G_P$4") (pintype "passive"))
    )
    (net (code "191") (name "Net-(U1101-G2)") (class "Default")
      (node (ref "U1101") (pin "P$15") (pinfunction "G2_P$15") (pintype "bidirectional"))
      (node (ref "U1103") (pin "P$2") (pinfunction "G_P$2") (pintype "passive"))
      (node (ref "U1103") (pin "P$4") (pinfunction "G_P$4") (pintype "passive"))
    )
    (net (code "192") (name "Net-(U1101-G3)") (class "Default")
      (node (ref "U1101") (pin "P$13") (pinfunction "G3_P$13") (pintype "bidirectional"))
      (node (ref "U1104") (pin "P$2") (pinfunction "G_P$2") (pintype "passive"))
      (node (ref "U1104") (pin "P$4") (pinfunction "G_P$4") (pintype "passive"))
    )
    (net (code "193") (name "OTG_FS_DM") (class "Default")
      (node (ref "U101") (pin "70") (pinfunction "PA11_70") (pintype "bidirectional"))
      (node (ref "U302") (pin "6") (pinfunction "D1O_6") (pintype "bidirectional"))
    )
    (net (code "194") (name "OTG_FS_DP") (class "Default")
      (node (ref "U101") (pin "71") (pinfunction "PA12_71") (pintype "bidirectional"))
      (node (ref "U302") (pin "4") (pinfunction "D2O_4") (pintype "bidirectional"))
    )
    (net (code "195") (name "PPM_INPUT") (class "Default")
      (node (ref "D901") (pin "C") (pinfunction "C_C") (pintype "passive"))
      (node (ref "R909") (pin "P$1") (pinfunction "1_P$1") (pintype "passive"))
      (node (ref "U801") (pin "29") (pinfunction "PA8_29") (pintype "bidirectional"))
      (node (ref "U903") (pin "2") (pinfunction "1A_2") (pintype "bidirectional"))
    )
    (net (code "196") (name "PRESSURE_SENS") (class "Default")
      (node (ref "C401") (pin "P$1") (pinfunction "1_P$1") (pintype "passive"))
      (node (ref "R403") (pin "P$2") (pinfunction "2_P$2") (pintype "passive"))
      (node (ref "R406") (pin "P$1") (pinfunction "1_P$1") (pintype "passive"))
      (node (ref "U101") (pin "34") (pinfunction "PC5_34") (pintype "bidirectional"))
    )
    (net (code "197") (name "PRESSURE_SENS_IN") (class "Default")
      (node (ref "ADC_PR") (pin "P$1") (pinfunction "P$1_P$1") (pintype "passive"))
      (node (ref "J402") (pin "2") (pinfunction "2_2") (pintype "passive"))
      (node (ref "R406") (pin "P$2") (pinfunction "2_P$2") (pintype "passive"))
    )
    (net (code "198") (name "RSSI_IN") (class "Default")
      (node (ref "R901") (pin "P$1") (pinfunction "1_P$1") (pintype "passive"))
      (node (ref "U801") (pin "15") (pinfunction "PA5_15") (pintype "bidirectional"))
      (node (ref "U801") (pin "33") (pinfunction "PA12_33") (pintype "bidirectional"))
    )
    (net (code "199") (name "SAFETY") (class "Default")
      (node (ref "J702") (pin "3") (pinfunction "3_3") (pintype "passive"))
      (node (ref "R713") (pin "P$1") (pinfunction "1_P$1") (pintype "passive"))
      (node (ref "U801") (pin "41") (pinfunction "PB5_41") (pintype "bidirectional"))
    )
    (net (code "200") (name "SBUS_INPUT") (class "Default")
      (node (ref "U801") (pin "22") (pinfunction "PB11_22") (pintype "bidirectional"))
      (node (ref "U903") (pin "6") (pinfunction "1Y_6") (pintype "bidirectional"))
    )
    (net (code "201") (name "SBUS_OUTPUT") (class "Default")
      (node (ref "U801") (pin "21") (pinfunction "PB10_21") (pintype "bidirectional"))
      (node (ref "U903") (pin "5") (pinfunction "2A_5") (pintype "bidirectional"))
    )
    (net (code "202") (name "SDIO_CK") (class "Default")
      (node (ref "U101") (pin "80") (pinfunction "PC12_80") (pintype "bidirectional"))
      (node (ref "U301") (pin "5") (pinfunction "CLK_5") (pintype "bidirectional"))
    )
    (net (code "203") (name "SDIO_CMD") (class "Default")
      (node (ref "R303") (pin "P$1") (pinfunction "1_P$1") (pintype "passive"))
      (node (ref "U101") (pin "83") (pinfunction "PD2_83") (pintype "bidirectional"))
      (node (ref "U301") (pin "3") (pinfunction "CMD_3") (pintype "bidirectional"))
    )
    (net (code "204") (name "SDIO_D0") (class "Default")
      (node (ref "R304") (pin "P$1") (pinfunction "1_P$1") (pintype "passive"))
      (node (ref "U101") (pin "65") (pinfunction "PC8_65") (pintype "bidirectional"))
      (node (ref "U301") (pin "7") (pinfunction "D0_7") (pintype "bidirectional"))
    )
    (net (code "205") (name "SDIO_D1") (class "Default")
      (node (ref "R305") (pin "P$1") (pinfunction "1_P$1") (pintype "passive"))
      (node (ref "U101") (pin "66") (pinfunction "PC9_66") (pintype "bidirectional"))
      (node (ref "U301") (pin "8") (pinfunction "D1_8") (pintype "bidirectional"))
    )
    (net (code "206") (name "SDIO_D2") (class "Default")
      (node (ref "R301") (pin "P$1") (pinfunction "1_P$1") (pintype "passive"))
      (node (ref "U101") (pin "78") (pinfunction "PC10_78") (pintype "bidirectional"))
      (node (ref "U301") (pin "1") (pinfunction "D2_1") (pintype "bidirectional"))
    )
    (net (code "207") (name "SDIO_D3") (class "Default")
      (node (ref "R302") (pin "P$1") (pinfunction "1_P$1") (pintype "passive"))
      (node (ref "U101") (pin "79") (pinfunction "PC11_79") (pintype "bidirectional"))
      (node (ref "U301") (pin "2") (pinfunction "D3_2") (pintype "bidirectional"))
    )
    (net (code "208") (name "SERIAL1_CTS") (class "Default")
      (node (ref "J201") (pin "4") (pinfunction "4_4") (pintype "passive"))
      (node (ref "R211") (pin "P$2") (pinfunction "2_P$2") (pintype "passive"))
    )
    (net (code "209") (name "SERIAL1_RTS") (class "Default")
      (node (ref "J201") (pin "5") (pinfunction "5_5") (pintype "passive"))
      (node (ref "R204") (pin "P$2") (pinfunction "2_P$2") (pintype "passive"))
    )
    (net (code "210") (name "SERIAL1_RX") (class "Default")
      (node (ref "J201") (pin "3") (pinfunction "3_3") (pintype "passive"))
      (node (ref "R203") (pin "P$2") (pinfunction "2_P$2") (pintype "passive"))
      (node (ref "S1RX") (pin "P$1") (pinfunction "P$1_P$1") (pintype "passive"))
    )
    (net (code "211") (name "SERIAL1_TX") (class "Default")
      (node (ref "J201") (pin "2") (pinfunction "2_2") (pintype "passive"))
      (node (ref "R210") (pin "P$2") (pinfunction "2_P$2") (pintype "passive"))
      (node (ref "S1TX") (pin "P$1") (pinfunction "P$1_P$1") (pintype "passive"))
    )
    (net (code "212") (name "SERIAL2_CTS") (class "Default")
      (node (ref "J202") (pin "4") (pinfunction "4_4") (pintype "passive"))
      (node (ref "R208") (pin "P$2") (pinfunction "2_P$2") (pintype "passive"))
    )
    (net (code "213") (name "SERIAL2_RTS") (class "Default")
      (node (ref "J202") (pin "5") (pinfunction "5_5") (pintype "passive"))
      (node (ref "R201") (pin "P$2") (pinfunction "2_P$2") (pintype "passive"))
    )
    (net (code "214") (name "SERIAL2_RX") (class "Default")
      (node (ref "J202") (pin "3") (pinfunction "3_3") (pintype "passive"))
      (node (ref "R202") (pin "P$2") (pinfunction "2_P$2") (pintype "passive"))
      (node (ref "S2RX") (pin "P$1") (pinfunction "P$1_P$1") (pintype "passive"))
    )
    (net (code "215") (name "SERIAL2_TX") (class "Default")
      (node (ref "J202") (pin "2") (pinfunction "2_2") (pintype "passive"))
      (node (ref "R209") (pin "P$2") (pinfunction "2_P$2") (pintype "passive"))
      (node (ref "S2TX") (pin "P$1") (pinfunction "P$1_P$1") (pintype "passive"))
    )
    (net (code "216") (name "SERIAL3_RX") (class "Default")
      (node (ref "J203") (pin "3") (pinfunction "3_3") (pintype "passive"))
      (node (ref "R207") (pin "P$2") (pinfunction "2_P$2") (pintype "passive"))
      (node (ref "S3RX") (pin "P$1") (pinfunction "P$1_P$1") (pintype "passive"))
    )
    (net (code "217") (name "SERIAL3_TX") (class "Default")
      (node (ref "J203") (pin "2") (pinfunction "2_2") (pintype "passive"))
      (node (ref "R214") (pin "P$2") (pinfunction "2_P$2") (pintype "passive"))
      (node (ref "S3TX") (pin "P$1") (pinfunction "P$1_P$1") (pintype "passive"))
    )
    (net (code "218") (name "SERIAL4_RX") (class "Default")
      (node (ref "J204") (pin "3") (pinfunction "3_3") (pintype "passive"))
      (node (ref "R206") (pin "P$2") (pinfunction "2_P$2") (pintype "passive"))
      (node (ref "S4RX") (pin "P$1") (pinfunction "P$1_P$1") (pintype "passive"))
    )
    (net (code "219") (name "SERIAL4_TX") (class "Default")
      (node (ref "J204") (pin "2") (pinfunction "2_2") (pintype "passive"))
      (node (ref "R213") (pin "P$2") (pinfunction "2_P$2") (pintype "passive"))
      (node (ref "S4TX") (pin "P$1") (pinfunction "P$1_P$1") (pintype "passive"))
    )
    (net (code "220") (name "SERIAL5_RX") (class "Default")
      (node (ref "J204") (pin "5") (pinfunction "5_5") (pintype "passive"))
      (node (ref "R205") (pin "P$2") (pinfunction "2_P$2") (pintype "passive"))
      (node (ref "S5_RX") (pin "P$1") (pinfunction "P$1_P$1") (pintype "passive"))
    )
    (net (code "221") (name "SERIAL5_TX") (class "Default")
      (node (ref "J204") (pin "4") (pinfunction "4_4") (pintype "passive"))
      (node (ref "R212") (pin "P$2") (pinfunction "2_P$2") (pintype "passive"))
      (node (ref "S5_TX") (pin "P$1") (pinfunction "P$1_P$1") (pintype "passive"))
    )
    (net (code "222") (name "SERIAL_FMU_TO_IO") (class "Default")
      (node (ref "R804") (pin "P$2") (pinfunction "2_P$2") (pintype "passive"))
      (node (ref "U101") (pin "63") (pinfunction "PC6_63") (pintype "bidirectional"))
    )
    (net (code "223") (name "SERIAL_IO_TO_FMU") (class "Default")
      (node (ref "R803") (pin "P$2") (pinfunction "2_P$2") (pintype "passive"))
      (node (ref "U101") (pin "64") (pinfunction "PC7_64") (pintype "bidirectional"))
    )
    (net (code "224") (name "SPI_EXT_MISO") (class "Default")
      (node (ref "J403") (pin "3") (pinfunction "3_3") (pintype "passive"))
      (node (ref "U101") (pin "4") (pinfunction "PE5_4") (pintype "bidirectional"))
    )
    (net (code "225") (name "SPI_EXT_MOSI") (class "Default")
      (node (ref "J403") (pin "4") (pinfunction "4_4") (pintype "passive"))
      (node (ref "U101") (pin "5") (pinfunction "PE6_5") (pintype "bidirectional"))
    )
    (net (code "226") (name "SPI_EXT_SCK") (class "Default")
      (node (ref "J403") (pin "2") (pinfunction "2_2") (pintype "passive"))
      (node (ref "U101") (pin "1") (pinfunction "PE2_1") (pintype "bidirectional"))
    )
    (net (code "227") (name "SPI_INT_MISO") (class "Default")
      (node (ref "U101") (pin "31") (pinfunction "PA6_31") (pintype "bidirectional"))
      (node (ref "U501") (pin "4") (pinfunction "SDO/SA0_4") (pintype "bidirectional"))
      (node (ref "U502") (pin "4") (pinfunction "SDO/SA0_4") (pintype "bidirectional"))
      (node (ref "U504") (pin "7") (pinfunction "SDO/SA0_7") (pintype "bidirectional"))
      (node (ref "U505") (pin "9") (pinfunction "AD0/SDO_9") (pintype "bidirectional"))
      (node (ref "U506") (pin "6") (pinfunction "SDO_6") (pintype "bidirectional"))
      (node (ref "X503") (pin "9") (pinfunction "S_9") (pintype "passive"))
    )
    (net (code "228") (name "SPI_INT_MOSI") (class "Default")
      (node (ref "U101") (pin "32") (pinfunction "PA7_32") (pintype "bidirectional"))
      (node (ref "U501") (pin "3") (pinfunction "SDA/SDI/SDO_3") (pintype "bidirectional"))
      (node (ref "U502") (pin "3") (pinfunction "SDA/SDI/SDO_3") (pintype "bidirectional"))
      (node (ref "U504") (pin "6") (pinfunction "SDA/SDI/SDO_6") (pintype "bidirectional"))
      (node (ref "U505") (pin "24") (pinfunction "SDA/SDI_24") (pintype "bidirectional"))
      (node (ref "U506") (pin "7") (pinfunction "SDI/SDA_7") (pintype "bidirectional"))
      (node (ref "X503") (pin "8") (pinfunction "S_8") (pintype "passive"))
    )
    (net (code "229") (name "SPI_INT_SCK") (class "Default")
      (node (ref "U101") (pin "30") (pinfunction "PA5_30") (pintype "bidirectional"))
      (node (ref "U501") (pin "2") (pinfunction "SCL/SPC_2") (pintype "input"))
      (node (ref "U502") (pin "2") (pinfunction "SCL/SPC_2") (pintype "bidirectional"))
      (node (ref "U504") (pin "4") (pinfunction "SCL/SPC_4") (pintype "bidirectional"))
      (node (ref "U505") (pin "23") (pinfunction "SCL/SCLK_23") (pintype "bidirectional"))
      (node (ref "U506") (pin "8") (pinfunction "SCLK_8") (pintype "bidirectional"))
      (node (ref "X503") (pin "10") (pinfunction "S_10") (pintype "passive"))
    )
    (net (code "230") (name "VBAT") (class "Default")
      (node (ref "B601") (pin "1") (pinfunction "POS_1") (pintype "bidirectional"))
      (node (ref "R608") (pin "P$1") (pinfunction "1_P$1") (pintype "passive"))
      (node (ref "U101") (pin "6") (pinfunction "VBAT_6") (pintype "power_in"))
      (node (ref "U801") (pin "1") (pinfunction "VBAT_1") (pintype "power_in"))
    )
    (net (code "231") (name "VBUS") (class "Default")
      (node (ref "C1103") (pin "P$1") (pinfunction "1_P$1") (pintype "passive"))
      (node (ref "J301") (pin "VBUS") (pinfunction "1_VBUS") (pintype "power_in"))
      (node (ref "J302") (pin "1") (pinfunction "1_1") (pintype "passive"))
      (node (ref "R1112") (pin "P$1") (pinfunction "1_P$1") (pintype "passive"))
      (node (ref "U101") (pin "68") (pinfunction "PA9_68") (pintype "bidirectional"))
      (node (ref "U1101") (pin "P$19") (pinfunction "V3_P$19") (pintype "bidirectional"))
      (node (ref "U1104") (pin "P$7") (pinfunction "D_P$7") (pintype "passive"))
      (node (ref "U1104") (pin "P$8") (pinfunction "D_P$8") (pintype "passive"))
      (node (ref "U302") (pin "5") (pinfunction "VBUS_5") (pintype "bidirectional"))
      (node (ref "VBUS") (pin "P$1") (pinfunction "P$1_P$1") (pintype "passive"))
    )
    (net (code "232") (name "VDD_3V3_SENSORS") (class "Default")
      (node (ref "C501") (pin "P$1") (pinfunction "1_P$1") (pintype "passive"))
      (node (ref "C502") (pin "P$1") (pinfunction "1_P$1") (pintype "passive"))
      (node (ref "C503") (pin "P$1") (pinfunction "1_P$1") (pintype "passive"))
      (node (ref "C506") (pin "P$1") (pinfunction "1_P$1") (pintype "passive"))
      (node (ref "C507") (pin "P$1") (pinfunction "1_P$1") (pintype "passive"))
      (node (ref "C508") (pin "P$1") (pinfunction "1_P$1") (pintype "passive"))
      (node (ref "C511") (pin "P$1") (pinfunction "1_P$1") (pintype "passive"))
      (node (ref "C513") (pin "P$1") (pinfunction "1_P$1") (pintype "passive"))
      (node (ref "C514") (pin "P$1") (pinfunction "1_P$1") (pintype "passive"))
      (node (ref "C605") (pin "P$1") (pinfunction "1_P$1") (pintype "passive"))
      (node (ref "C617") (pin "P$1") (pinfunction "1_P$1") (pintype "passive"))
      (node (ref "R621") (pin "2") (pinfunction "2_2") (pintype "passive"))
      (node (ref "U501") (pin "1") (pinfunction "VDD_IO_1") (pintype "bidirectional"))
      (node (ref "U501") (pin "15") (pinfunction "RES_P15_VDD_15") (pintype "bidirectional"))
      (node (ref "U501") (pin "16") (pinfunction "VDD_16") (pintype "bidirectional"))
      (node (ref "U502") (pin "1") (pinfunction "VDD_IO_1") (pintype "bidirectional"))
      (node (ref "U502") (pin "15") (pinfunction "VDD_15") (pintype "bidirectional"))
      (node (ref "U502") (pin "16") (pinfunction "VDD_16") (pintype "bidirectional"))
      (node (ref "U504") (pin "1") (pinfunction "VDD_IO_1") (pintype "bidirectional"))
      (node (ref "U504") (pin "14") (pinfunction "VDD_14") (pintype "bidirectional"))
      (node (ref "U505") (pin "13") (pinfunction "VDD_13") (pintype "bidirectional"))
      (node (ref "U506") (pin "1") (pinfunction "VDD_1") (pintype "bidirectional"))
      (node (ref "U603") (pin "8") (pinfunction "VOUT1_8") (pintype "bidirectional"))
      (node (ref "VDDA_3V1101") (pin "P$1") (pinfunction "P$1_P$1") (pintype "passive"))
      (node (ref "X503") (pin "1") (pinfunction "S_1") (pintype "passive"))
    )
    (net (code "233") (name "VDD_3V3_SENSORS_EN") (class "Default")
      (node (ref "R603") (pin "P$2") (pinfunction "2_P$2") (pintype "passive"))
      (node (ref "R635") (pin "P$2") (pinfunction "2_P$2") (pintype "passive"))
      (node (ref "U101") (pin "2") (pinfunction "PE3_2") (pintype "bidirectional"))
      (node (ref "U603") (pin "5") (pinfunction "EN1_5") (pintype "bidirectional"))
    )
    (net (code "234") (name "VDD_3V3_SPEKTRUM") (class "Default")
      (node (ref "C1008") (pin "P$1") (pinfunction "1_P$1") (pintype "passive"))
      (node (ref "D801") (pin "C") (pinfunction "C_C") (pintype "passive"))
      (node (ref "J801") (pin "P$1") (pinfunction "P$1_P$1") (pintype "bidirectional"))
      (node (ref "U1002") (pin "8") (pinfunction "VOUT1_8") (pintype "bidirectional"))
    )
    (net (code "235") (name "VDD_3V3_SPEKTRUM_EN") (class "Default")
      (node (ref "R1002") (pin "P$2") (pinfunction "2_P$2") (pintype "passive"))
      (node (ref "U1002") (pin "5") (pinfunction "EN1_5") (pintype "bidirectional"))
      (node (ref "U801") (pin "2") (pinfunction "PC13_2") (pintype "bidirectional"))
    )
    (net (code "236") (name "VDD_5V_BRICK") (class "Default")
      (node (ref "C1101") (pin "P$1") (pinfunction "1_P$1") (pintype "passive"))
      (node (ref "J601") (pin "1") (pinfunction "1_1") (pintype "passive"))
      (node (ref "J601") (pin "2") (pinfunction "2_2") (pintype "passive"))
      (node (ref "R1105") (pin "P$1") (pinfunction "1_P$1") (pintype "passive"))
      (node (ref "U1101") (pin "P$21") (pinfunction "V1_P$21") (pintype "bidirectional"))
      (node (ref "U1102") (pin "P$7") (pinfunction "D_P$7") (pintype "passive"))
      (node (ref "U1102") (pin "P$8") (pinfunction "D_P$8") (pintype "passive"))
      (node (ref "VDD_5V_BRICK") (pin "P$1") (pinfunction "P$1_P$1") (pintype "passive"))
    )
    (net (code "237") (name "VDD_5V_HIPOWER") (class "Default")
      (node (ref "C614") (pin "P$1") (pinfunction "1_P$1") (pintype "passive"))
      (node (ref "L201") (pin "P$1") (pinfunction "P$1_P$1") (pintype "bidirectional"))
      (node (ref "U601") (pin "8") (pinfunction "OUT_8") (pintype "bidirectional"))
    )
    (net (code "238") (name "VDD_5V_IN") (class "Default")
      (node (ref "C1104") (pin "P$1") (pinfunction "1_P$1") (pintype "passive"))
      (node (ref "C702") (pin "P$1") (pinfunction "1_P$1") (pintype "passive"))
      (node (ref "F1001") (pin "1") (pinfunction "1_1") (pintype "bidirectional"))
      (node (ref "L603") (pin "P$1") (pinfunction "P$1_P$1") (pintype "bidirectional"))
      (node (ref "L701") (pin "P$1") (pinfunction "1_P$1") (pintype "passive"))
      (node (ref "LED701") (pin "A") (pinfunction "A_A") (pintype "passive"))
      (node (ref "LED704") (pin "A") (pinfunction "A_A") (pintype "passive"))
      (node (ref "R609") (pin "P$2") (pinfunction "2_P$2") (pintype "passive"))
      (node (ref "RN1101") (pin "5") (pinfunction "2_5") (pintype "passive"))
      (node (ref "RN1101") (pin "6") (pinfunction "2_6") (pintype "passive"))
      (node (ref "RN1101") (pin "7") (pinfunction "2_7") (pintype "passive"))
      (node (ref "U1101") (pin "P$12") (pinfunction "VOUT_P$12") (pintype "bidirectional"))
      (node (ref "U1102") (pin "P$5") (pinfunction "D_P$5") (pintype "passive"))
      (node (ref "U1102") (pin "P$6") (pinfunction "D_P$6") (pintype "passive"))
      (node (ref "U1103") (pin "P$5") (pinfunction "D_P$5") (pintype "passive"))
      (node (ref "U1103") (pin "P$6") (pinfunction "D_P$6") (pintype "passive"))
      (node (ref "U1104") (pin "P$5") (pinfunction "D_P$5") (pintype "passive"))
      (node (ref "U1104") (pin "P$6") (pinfunction "D_P$6") (pintype "passive"))
      (node (ref "U601") (pin "1") (pinfunction "IN_1") (pintype "bidirectional"))
      (node (ref "U602") (pin "1") (pinfunction "IN_1") (pintype "bidirectional"))
      (node (ref "U702") (pin "3") (pinfunction "VIN_3") (pintype "power_in"))
      (node (ref "U703") (pin "A1") (pinfunction "A_A1") (pintype "passive"))
      (node (ref "U703") (pin "A2") (pinfunction "A_A2") (pintype "passive"))
      (node (ref "U703") (pin "A3") (pinfunction "A_A3") (pintype "passive"))
      (node (ref "VDD_5V_IN") (pin "P$1") (pinfunction "P$1_P$1") (pintype "passive"))
    )
    (net (code "239") (name "VDD_5V_PERIPH") (class "Default")
      (node (ref "C618") (pin "P$1") (pinfunction "1_P$1") (pintype "passive"))
      (node (ref "L202") (pin "P$1") (pinfunction "P$1_P$1") (pintype "bidirectional"))
      (node (ref "L203") (pin "P$1") (pinfunction "P$1_P$1") (pintype "bidirectional"))
      (node (ref "L401") (pin "P$1") (pinfunction "P$1_P$1") (pintype "bidirectional"))
      (node (ref "L402") (pin "P$1") (pinfunction "P$1_P$1") (pintype "bidirectional"))
      (node (ref "L403") (pin "P$1") (pinfunction "P$1_P$1") (pintype "bidirectional"))
      (node (ref "L404") (pin "P$1") (pinfunction "P$1_P$1") (pintype "bidirectional"))
      (node (ref "U602") (pin "8") (pinfunction "OUT_8") (pintype "bidirectional"))
    )
    (net (code "240") (name "VDD_5V_SENS") (class "Default")
      (node (ref "R609") (pin "P$1") (pinfunction "1_P$1") (pintype "passive"))
      (node (ref "R610") (pin "P$1") (pinfunction "1_P$1") (pintype "passive"))
      (node (ref "U101") (pin "29") (pinfunction "PA4_29") (pintype "bidirectional"))
    )
    (net (code "241") (name "VDD_SERVO") (class "Default")
      (node (ref "C1102") (pin "P$1") (pinfunction "1_P$1") (pintype "passive"))
      (node (ref "D904") (pin "ANODE") (pinfunction "A_ANODE") (pintype "passive"))
      (node (ref "J901") (pin "11") (pinfunction "S_11") (pintype "passive"))
      (node (ref "J901") (pin "14") (pinfunction "S_14") (pintype "passive"))
      (node (ref "J901") (pin "17") (pinfunction "S_17") (pintype "passive"))
      (node (ref "J901") (pin "20") (pinfunction "S_20") (pintype "passive"))
      (node (ref "J901") (pin "23") (pinfunction "S_23") (pintype "passive"))
      (node (ref "J901") (pin "26") (pinfunction "S_26") (pintype "passive"))
      (node (ref "J901") (pin "29") (pinfunction "S_29") (pintype "passive"))
      (node (ref "J901") (pin "32") (pinfunction "S_32") (pintype "passive"))
      (node (ref "J901") (pin "35") (pinfunction "S_35") (pintype "passive"))
      (node (ref "J901") (pin "38") (pinfunction "S_38") (pintype "passive"))
      (node (ref "J901") (pin "41") (pinfunction "S_41") (pintype "passive"))
      (node (ref "J901") (pin "44") (pinfunction "S_44") (pintype "passive"))
      (node (ref "J901") (pin "47") (pinfunction "S_47") (pintype "passive"))
      (node (ref "J901") (pin "5") (pinfunction "S_5") (pintype "passive"))
      (node (ref "J901") (pin "8") (pinfunction "S_8") (pintype "passive"))
      (node (ref "R1109") (pin "P$1") (pinfunction "1_P$1") (pintype "passive"))
      (node (ref "R922") (pin "P$2") (pinfunction "2_P$2") (pintype "passive"))
      (node (ref "U1101") (pin "P$20") (pinfunction "V2_P$20") (pintype "bidirectional"))
      (node (ref "U1103") (pin "P$7") (pinfunction "D_P$7") (pintype "passive"))
      (node (ref "U1103") (pin "P$8") (pinfunction "D_P$8") (pintype "passive"))
      (node (ref "VDD_SERVO") (pin "P$1") (pinfunction "P$1_P$1") (pintype "passive"))
    )
    (net (code "242") (name "VDD_SERVO_IN") (class "Default")
      (node (ref "L901") (pin "P$2") (pinfunction "P$2_P$2") (pintype "bidirectional"))
      (node (ref "U1001") (pin "1") (pinfunction "IN_1") (pintype "bidirectional"))
    )
    (net (code "243") (name "VDD_SERVO_SENS") (class "Default")
      (node (ref "R918") (pin "P$1") (pinfunction "1_P$1") (pintype "passive"))
      (node (ref "R919") (pin "P$2") (pinfunction "2_P$2") (pintype "passive"))
      (node (ref "U801") (pin "14") (pinfunction "PA4_14") (pintype "bidirectional"))
    )
    (net (code "244") (name "unconnected-(J301-4-PadID)") (class "Default")
      (node (ref "J301") (pin "ID") (pinfunction "4_ID") (pintype "passive"))
    )
    (net (code "245") (name "unconnected-(JX301A-S-Pad10)") (class "Default")
      (node (ref "JX301") (pin "10") (pinfunction "S_10") (pintype "passive"))
    )
    (net (code "246") (name "unconnected-(JX301F-S-Pad8)") (class "Default")
      (node (ref "JX301") (pin "8") (pinfunction "S_8") (pintype "passive"))
    )
    (net (code "247") (name "unconnected-(JX802A-S-Pad10)") (class "Default")
      (node (ref "JX802") (pin "10") (pinfunction "S_10") (pintype "passive"))
    )
    (net (code "248") (name "unconnected-(JX802F-S-Pad8)") (class "Default")
      (node (ref "JX802") (pin "8") (pinfunction "S_8") (pintype "passive"))
    )
    (net (code "249") (name "unconnected-(U101I-PC1-Pad16)") (class "Default")
      (node (ref "U101") (pin "16") (pinfunction "PC1_16") (pintype "bidirectional"))
    )
    (net (code "250") (name "unconnected-(U202-A1-Pad1)") (class "Default")
      (node (ref "U202") (pin "1") (pinfunction "A1_1") (pintype "bidirectional"))
    )
    (net (code "251") (name "unconnected-(U202-A2-Pad3)") (class "Default")
      (node (ref "U202") (pin "3") (pinfunction "A2_3") (pintype "bidirectional"))
    )
    (net (code "252") (name "unconnected-(U202-B1-Pad20)") (class "Default")
      (node (ref "U202") (pin "20") (pinfunction "B1_20") (pintype "bidirectional"))
    )
    (net (code "253") (name "unconnected-(U202-B2-Pad18)") (class "Default")
      (node (ref "U202") (pin "18") (pinfunction "B2_18") (pintype "bidirectional"))
    )
    (net (code "254") (name "unconnected-(U501-INT1-Pad7)") (class "Default")
      (node (ref "U501") (pin "7") (pinfunction "INT1_7") (pintype "output"))
    )
    (net (code "255") (name "unconnected-(U502-DEN-Pad8)") (class "Default")
      (node (ref "U502") (pin "8") (pinfunction "DEN_8") (pintype "bidirectional"))
    )
    (net (code "256") (name "unconnected-(U502-INT1-Pad7)") (class "Default")
      (node (ref "U502") (pin "7") (pinfunction "INT1_7") (pintype "bidirectional"))
    )
    (net (code "257") (name "unconnected-(U505-AUX_CL-Pad7)") (class "Default")
      (node (ref "U505") (pin "7") (pinfunction "AUX_CL_7") (pintype "bidirectional"))
    )
    (net (code "258") (name "unconnected-(U505-AUX_DA-Pad6)") (class "Default")
      (node (ref "U505") (pin "6") (pinfunction "AUX_DA_6") (pintype "bidirectional"))
    )
    (net (code "259") (name "unconnected-(U505-CLKOUT-Pad22)") (class "Default")
      (node (ref "U505") (pin "22") (pinfunction "CLKOUT_22") (pintype "bidirectional"))
    )
    (net (code "260") (name "unconnected-(U505-FSYNC-Pad11)") (class "Default")
      (node (ref "U505") (pin "11") (pinfunction "FSYNC_11") (pintype "bidirectional"))
    )
    (net (code "261") (name "unconnected-(U505-NC1-Pad2)") (class "Default")
      (node (ref "U505") (pin "2") (pinfunction "NC1_2") (pintype "bidirectional"))
    )
    (net (code "262") (name "unconnected-(U505-NC2-Pad3)") (class "Default")
      (node (ref "U505") (pin "3") (pinfunction "NC2_3") (pintype "bidirectional"))
    )
    (net (code "263") (name "unconnected-(U505-NC3-Pad4)") (class "Default")
      (node (ref "U505") (pin "4") (pinfunction "NC3_4") (pintype "bidirectional"))
    )
    (net (code "264") (name "unconnected-(U505-NC4-Pad5)") (class "Default")
      (node (ref "U505") (pin "5") (pinfunction "NC4_5") (pintype "bidirectional"))
    )
    (net (code "265") (name "unconnected-(U505-NC5-Pad14)") (class "Default")
      (node (ref "U505") (pin "14") (pinfunction "NC5_14") (pintype "bidirectional"))
    )
    (net (code "266") (name "unconnected-(U505-NC6-Pad15)") (class "Default")
      (node (ref "U505") (pin "15") (pinfunction "NC6_15") (pintype "bidirectional"))
    )
    (net (code "267") (name "unconnected-(U505-NC7-Pad16)") (class "Default")
      (node (ref "U505") (pin "16") (pinfunction "NC7_16") (pintype "bidirectional"))
    )
    (net (code "268") (name "unconnected-(U505-NC8-Pad17)") (class "Default")
      (node (ref "U505") (pin "17") (pinfunction "NC8_17") (pintype "bidirectional"))
    )
    (net (code "269") (name "unconnected-(U505-RESV1-Pad19)") (class "Default")
      (node (ref "U505") (pin "19") (pinfunction "RESV1_19") (pintype "bidirectional"))
    )
    (net (code "270") (name "unconnected-(U505-RESV2-Pad21)") (class "Default")
      (node (ref "U505") (pin "21") (pinfunction "RESV2_21") (pintype "bidirectional"))
    )
    (net (code "271") (name "unconnected-(U506-CSB1-Pad4)") (class "Default")
      (node (ref "U506") (pin "4") (pinfunction "CSB1_4") (pintype "bidirectional"))
    )
    (net (code "272") (name "unconnected-(U801B-PA11-Pad32)") (class "Default")
      (node (ref "U801") (pin "32") (pinfunction "PA11_32") (pintype "bidirectional"))
    )
    (net (code "273") (name "unconnected-(U801D-PB12-Pad25)") (class "Default")
      (node (ref "U801") (pin "25") (pinfunction "PB12_25") (pintype "bidirectional"))
    )
    (net (code "274") (name "unconnected-(U801E-PB6-Pad42)") (class "Default")
      (node (ref "U801") (pin "42") (pinfunction "PB6_42") (pintype "bidirectional"))
    )
    (net (code "275") (name "unconnected-(U801E-PB7-Pad43)") (class "Default")
      (node (ref "U801") (pin "43") (pinfunction "PB7_43") (pintype "bidirectional"))
    )
    (net (code "276") (name "unconnected-(U801F-PC14-Pad3)") (class "Default")
      (node (ref "U801") (pin "3") (pinfunction "PC14_3") (pintype "bidirectional"))
    )
    (net (code "277") (name "unconnected-(U801F-PC15-Pad4)") (class "Default")
      (node (ref "U801") (pin "4") (pinfunction "PC15_4") (pintype "bidirectional"))
    )
    (net (code "278") (name "unconnected-(U901-A7-Pad8)") (class "Default")
      (node (ref "U901") (pin "8") (pinfunction "A7_8") (pintype "bidirectional"))
    )
    (net (code "279") (name "unconnected-(U901-A8-Pad9)") (class "Default")
      (node (ref "U901") (pin "9") (pinfunction "A8_9") (pintype "bidirectional"))
    )
    (net (code "280") (name "unconnected-(U901-B7-Pad13)") (class "Default")
      (node (ref "U901") (pin "13") (pinfunction "B7_13") (pintype "bidirectional"))
    )
    (net (code "281") (name "unconnected-(U901-B8-Pad12)") (class "Default")
      (node (ref "U901") (pin "12") (pinfunction "B8_12") (pintype "bidirectional"))
    )
    (net (code "282") (name "unconnected-(U1101-CAS-PadP$11)") (class "Default")
      (node (ref "U1101") (pin "P$11") (pinfunction "CAS_P$11") (pintype "bidirectional"))
    )
    (net (code "283") (name "unconnected-(U1101-EN-PadP$22)") (class "Default")
      (node (ref "U1101") (pin "P$22") (pinfunction "EN_P$22") (pintype "bidirectional"))
    )
    (net (code "284") (name "unconnected-(U1101-~{SHDN}-PadP$23)") (class "Default")
      (node (ref "U1101") (pin "P$23") (pinfunction "~{SHDN}_P$23") (pintype "bidirectional"))
    )
    (net (code "285") (name "~{ACCEL_MAG_CS}") (class "Default")
      (node (ref "U101") (pin "9") (pinfunction "PC15_9") (pintype "bidirectional"))
      (node (ref "U504") (pin "8") (pinfunction "CS_8") (pintype "bidirectional"))
      (node (ref "X503") (pin "6") (pinfunction "S_6") (pintype "passive"))
    )
    (net (code "286") (name "~{BARO_CS}") (class "Default")
      (node (ref "U101") (pin "88") (pinfunction "PD7_88") (pintype "bidirectional"))
      (node (ref "U506") (pin "5") (pinfunction "CSB2_5") (pintype "bidirectional"))
    )
    (net (code "287") (name "~{FMU-LED_AMBER}") (class "Default")
      (node (ref "R707") (pin "P$1") (pinfunction "1_P$1") (pintype "passive"))
      (node (ref "U101") (pin "43") (pinfunction "PE12_43") (pintype "bidirectional"))
    )
    (net (code "288") (name "~{FRAM_CS}") (class "Default")
      (node (ref "U101") (pin "57") (pinfunction "PD10_57") (pintype "bidirectional"))
      (node (ref "U102") (pin "1") (pinfunction "~{S}_1") (pintype "bidirectional"))
    )
    (net (code "289") (name "~{GYRO_CS}") (class "Default")
      (node (ref "U101") (pin "7") (pinfunction "PC13_7") (pintype "bidirectional"))
      (node (ref "U501") (pin "5") (pinfunction "CS_5") (pintype "input"))
      (node (ref "U502") (pin "5") (pinfunction "CS_5") (pintype "bidirectional"))
      (node (ref "X503") (pin "7") (pinfunction "S_7") (pintype "passive"))
    )
    (net (code "290") (name "~{IO-LED_AMBER}") (class "Default")
      (node (ref "R709") (pin "P$1") (pinfunction "1_P$1") (pintype "passive"))
      (node (ref "U801") (pin "28") (pinfunction "PB15_28") (pintype "bidirectional"))
    )
    (net (code "291") (name "~{IO-LED_BLUE}") (class "Default")
      (node (ref "R712") (pin "P$1") (pinfunction "1_P$1") (pintype "passive"))
      (node (ref "U801") (pin "27") (pinfunction "PB14_27") (pintype "bidirectional"))
    )
    (net (code "292") (name "~{IO-LED_SAFETY}") (class "Default")
      (node (ref "R710") (pin "P$2") (pinfunction "2_P$2") (pintype "passive"))
      (node (ref "U801") (pin "26") (pinfunction "PB13_26") (pintype "bidirectional"))
    )
    (net (code "293") (name "~{MPU_CS}") (class "Default")
      (node (ref "U101") (pin "17") (pinfunction "PC2_17") (pintype "bidirectional"))
      (node (ref "U505") (pin "8") (pinfunction "/CS_8") (pintype "bidirectional"))
    )
    (net (code "294") (name "~{SBUS_OUTPUT_EN}") (class "Default")
      (node (ref "U801") (pin "40") (pinfunction "PB4_40") (pintype "bidirectional"))
      (node (ref "U903") (pin "7") (pinfunction "~{2OE}_7") (pintype "input"))
    )
    (net (code "295") (name "~{SPI_EXT_NSS}") (class "Default")
      (node (ref "J403") (pin "5") (pinfunction "5_5") (pintype "passive"))
      (node (ref "U101") (pin "3") (pinfunction "PE4_3") (pintype "bidirectional"))
    )
    (net (code "296") (name "~{VBUS_VALID}") (class "Default")
      (node (ref "!VBUS_VALID") (pin "P$1") (pinfunction "P$1_P$1") (pintype "passive"))
      (node (ref "RN1101") (pin "2") (pinfunction "1_2") (pintype "passive"))
      (node (ref "U101") (pin "15") (pinfunction "PC0_15") (pintype "bidirectional"))
      (node (ref "U1101") (pin "P$9") (pinfunction "~{VALID3}_P$9") (pintype "bidirectional"))
    )
    (net (code "297") (name "~{VDD_5V_HIPOWER_OC}") (class "Default")
      (node (ref "R602") (pin "P$1") (pinfunction "1_P$1") (pintype "passive"))
      (node (ref "U101") (pin "41") (pinfunction "PE10_41") (pintype "bidirectional"))
      (node (ref "U601") (pin "4") (pinfunction "~{FAULT}_4") (pintype "bidirectional"))
    )
    (net (code "298") (name "~{VDD_5V_PERIPH_EN}") (class "Default")
      (node (ref "R615") (pin "P$1") (pinfunction "1_P$1") (pintype "passive"))
      (node (ref "U101") (pin "67") (pinfunction "PA8_67") (pintype "bidirectional"))
      (node (ref "U601") (pin "5") (pinfunction "~{CE}_5") (pintype "bidirectional"))
      (node (ref "U602") (pin "5") (pinfunction "~{CE}_5") (pintype "bidirectional"))
    )
    (net (code "299") (name "~{VDD_5V_PERIPH_OC}") (class "Default")
      (node (ref "R604") (pin "P$1") (pinfunction "1_P$1") (pintype "passive"))
      (node (ref "U101") (pin "46") (pinfunction "PE15_46") (pintype "bidirectional"))
      (node (ref "U602") (pin "4") (pinfunction "~{FAULT}_4") (pintype "bidirectional"))
    )
    (net (code "300") (name "~{VDD_BRICK_VALID}") (class "Default")
      (node (ref "!VDD_BRICK_VALID") (pin "P$1") (pinfunction "P$1_P$1") (pintype "passive"))
      (node (ref "RN1101") (pin "4") (pinfunction "1_4") (pintype "passive"))
      (node (ref "U101") (pin "91") (pinfunction "PB5_91") (pintype "bidirectional"))
      (node (ref "U1101") (pin "P$7") (pinfunction "~{VALID1}_P$7") (pintype "bidirectional"))
    )
    (net (code "301") (name "~{VDD_SERVO_VALID}") (class "Default")
      (node (ref "!VDD_SERVO_VALID") (pin "P$1") (pinfunction "P$1_P$1") (pintype "passive"))
      (node (ref "RN1101") (pin "3") (pinfunction "1_3") (pintype "passive"))
      (node (ref "U101") (pin "93") (pinfunction "PB7_93") (pintype "bidirectional"))
      (node (ref "U1101") (pin "P$8") (pinfunction "~{VALID2}_P$8") (pintype "bidirectional"))
    )
  )
)
